# soundcard_v2_1.net
KiCad netlist of a schematic drawn in EAGLE
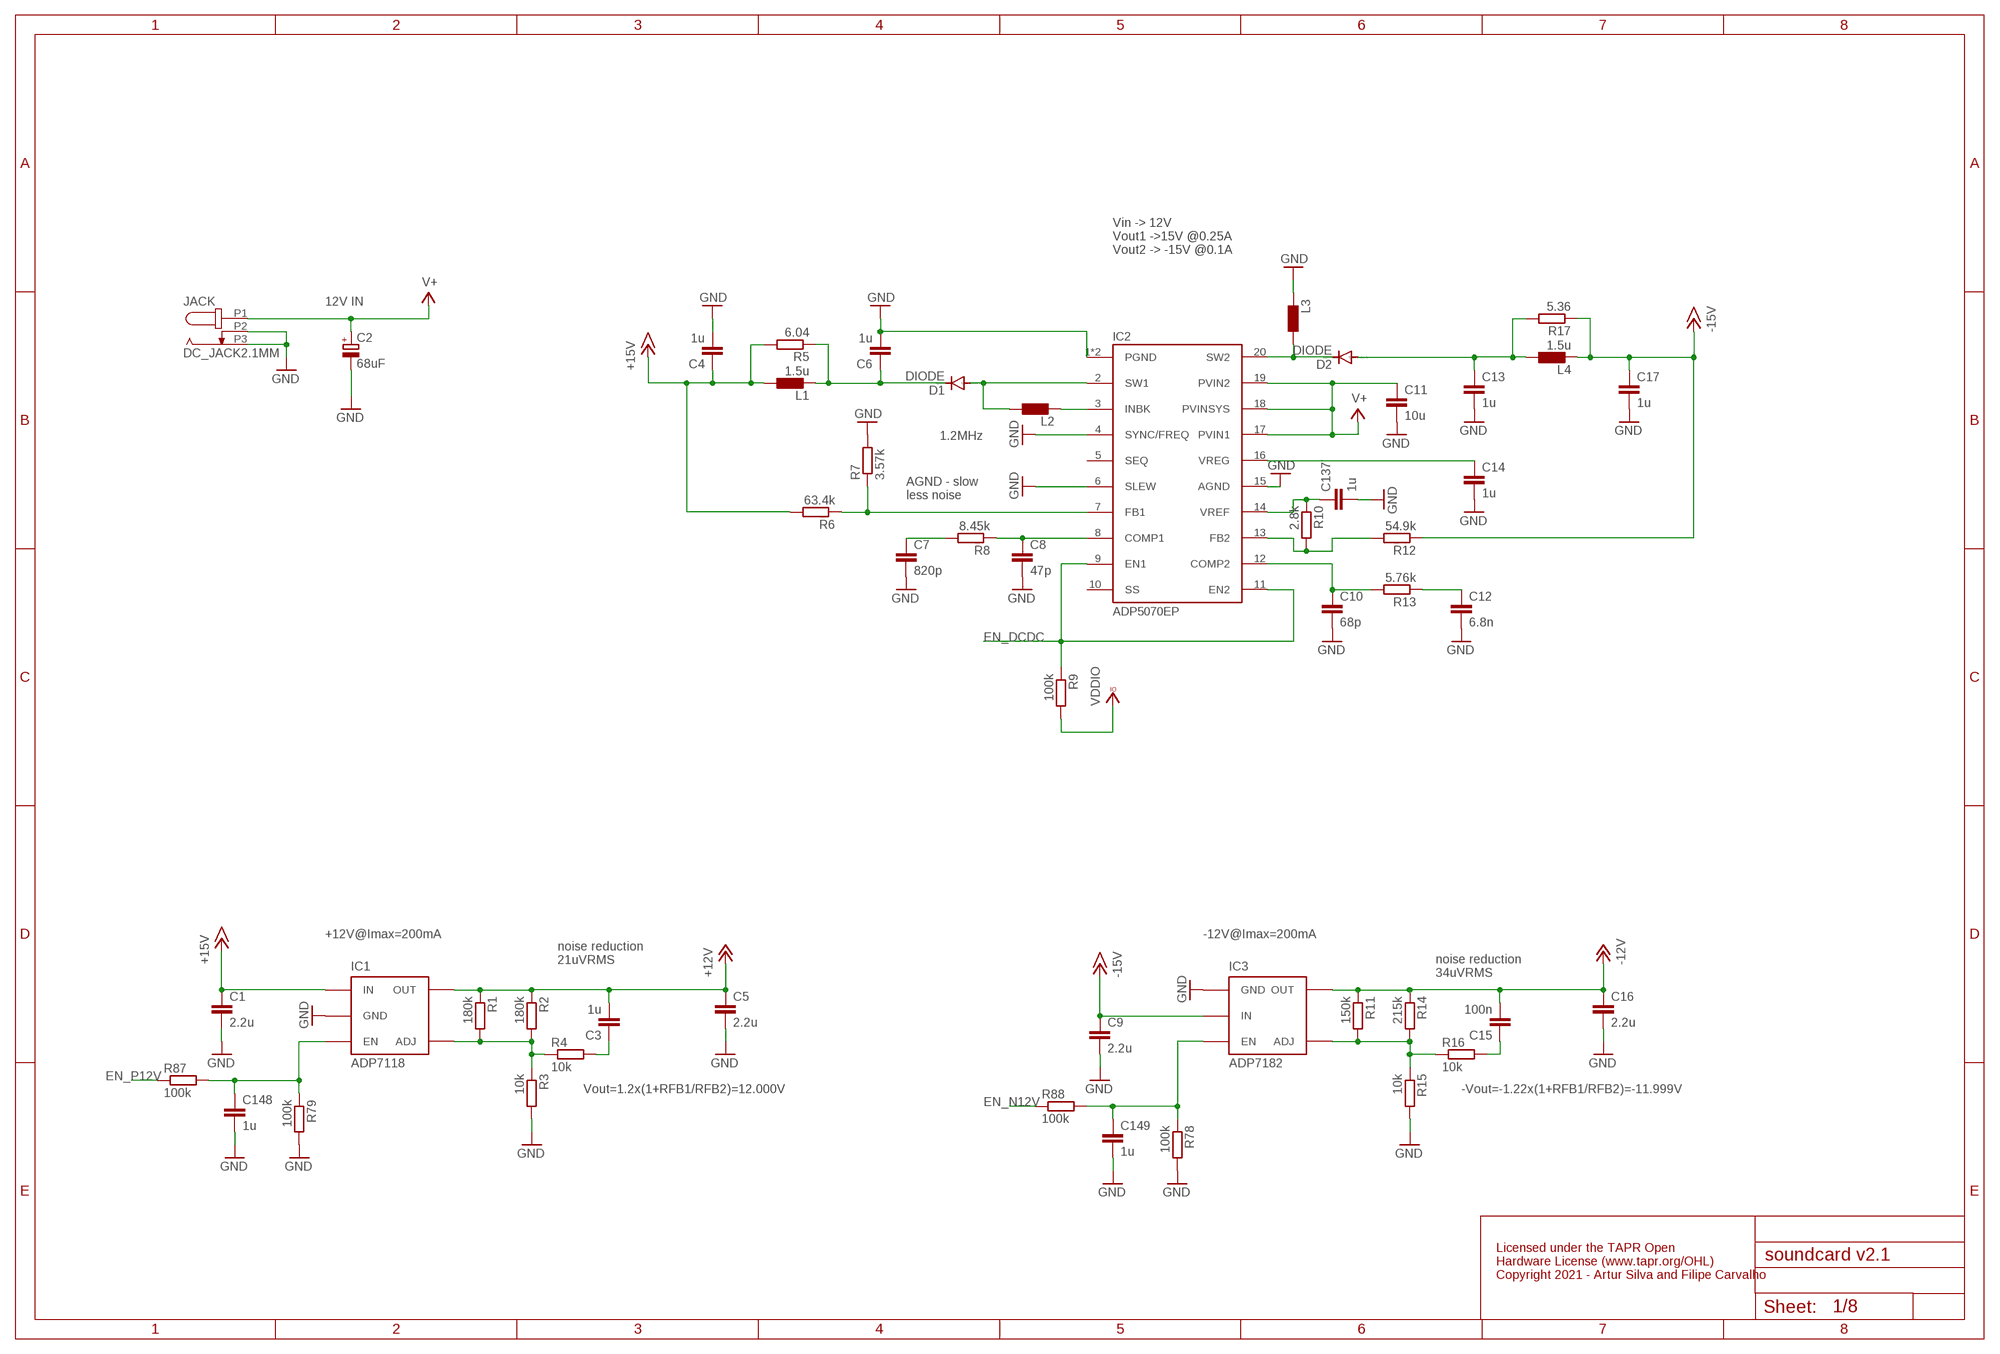
[diagram p0: schematic, sheet 1]
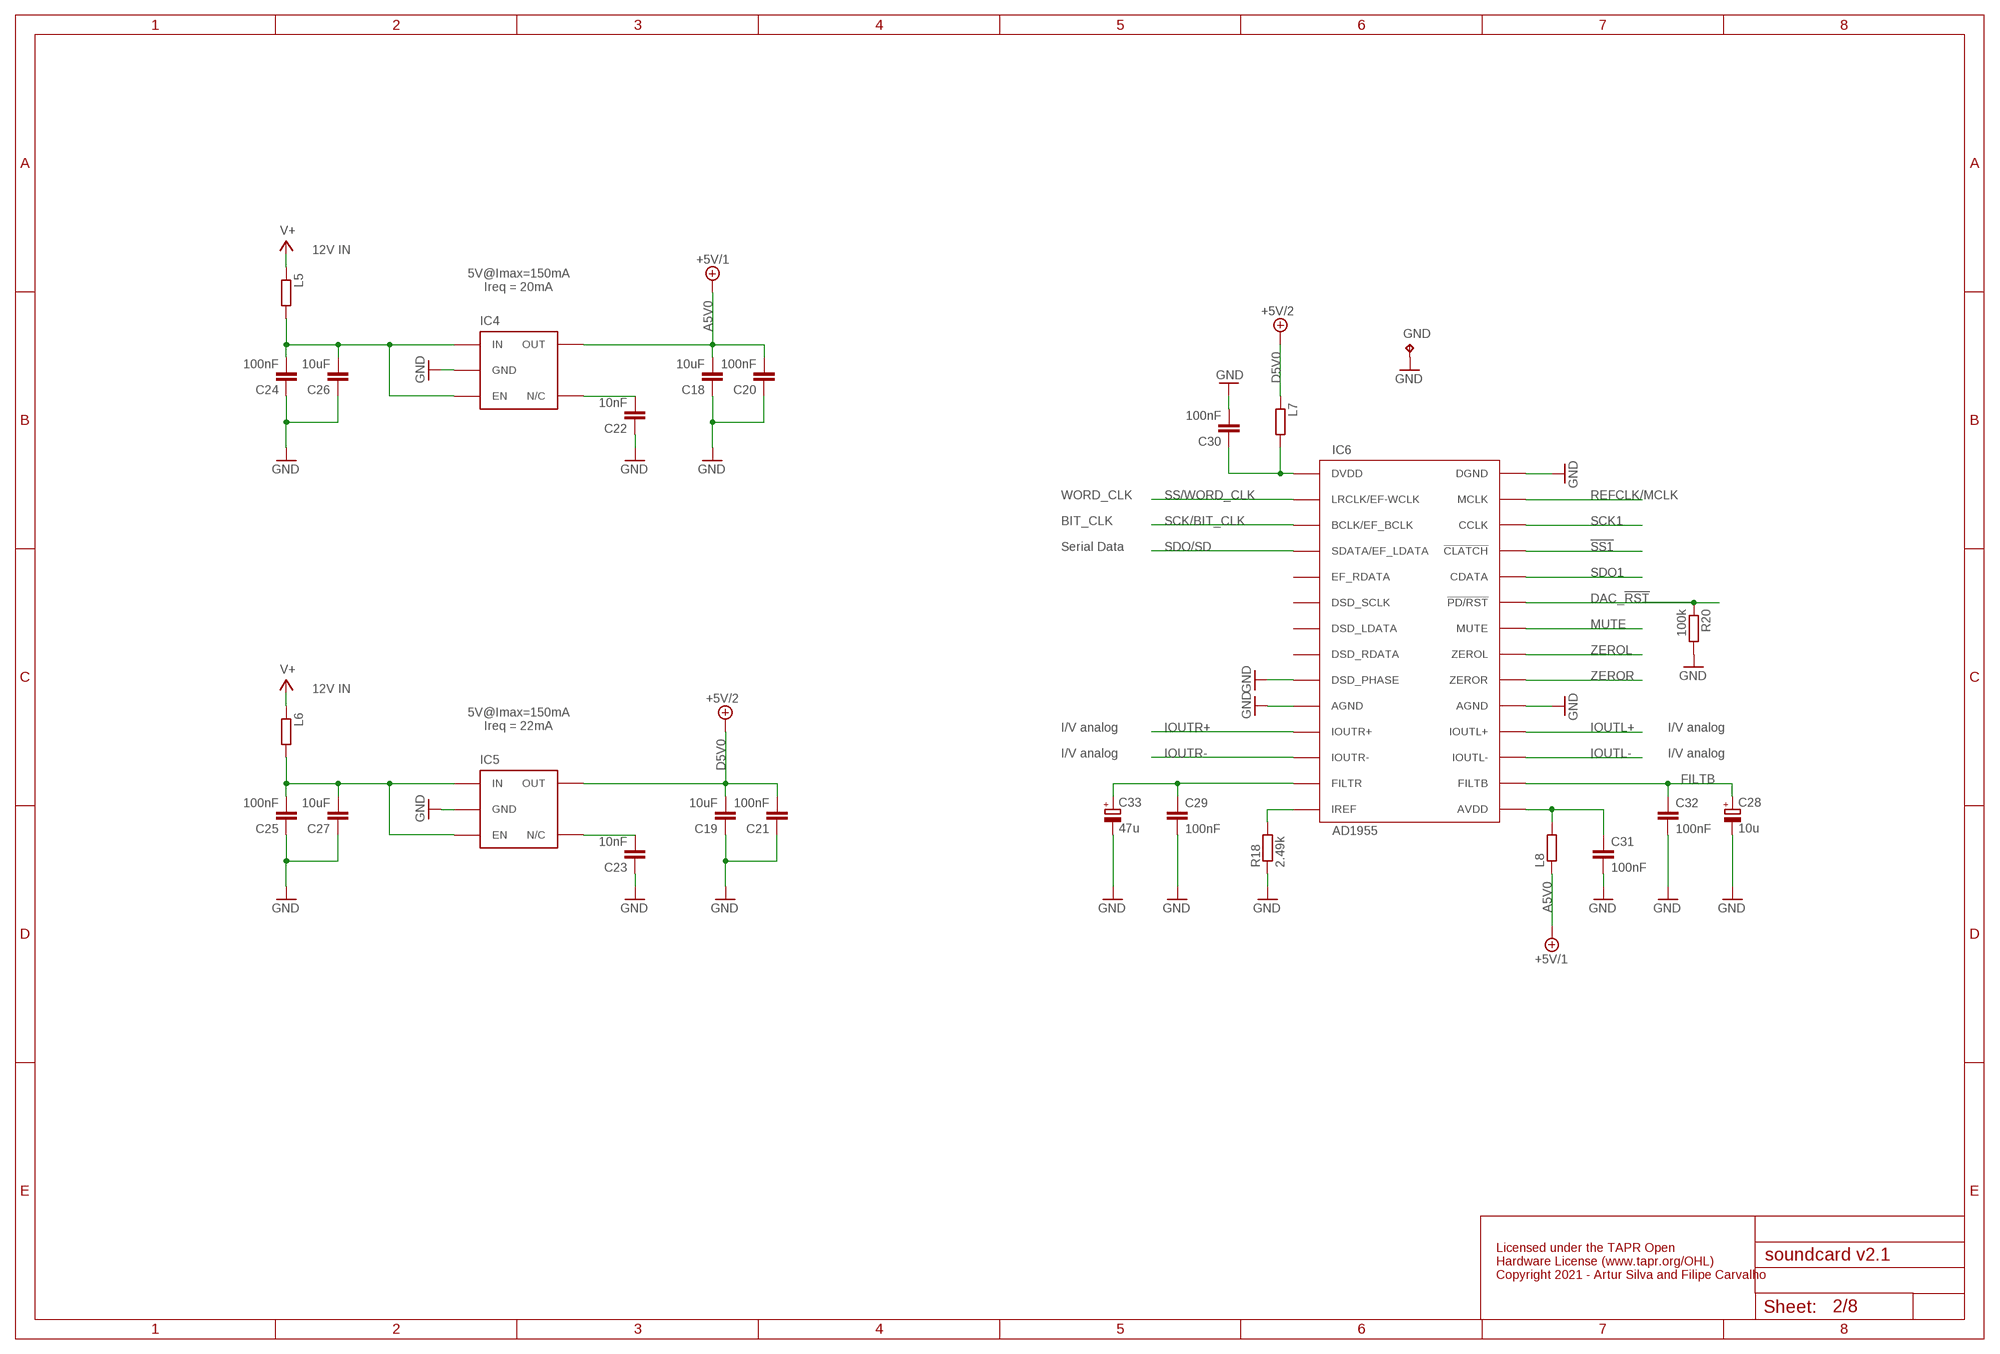
[diagram p1: schematic, sheet 2]
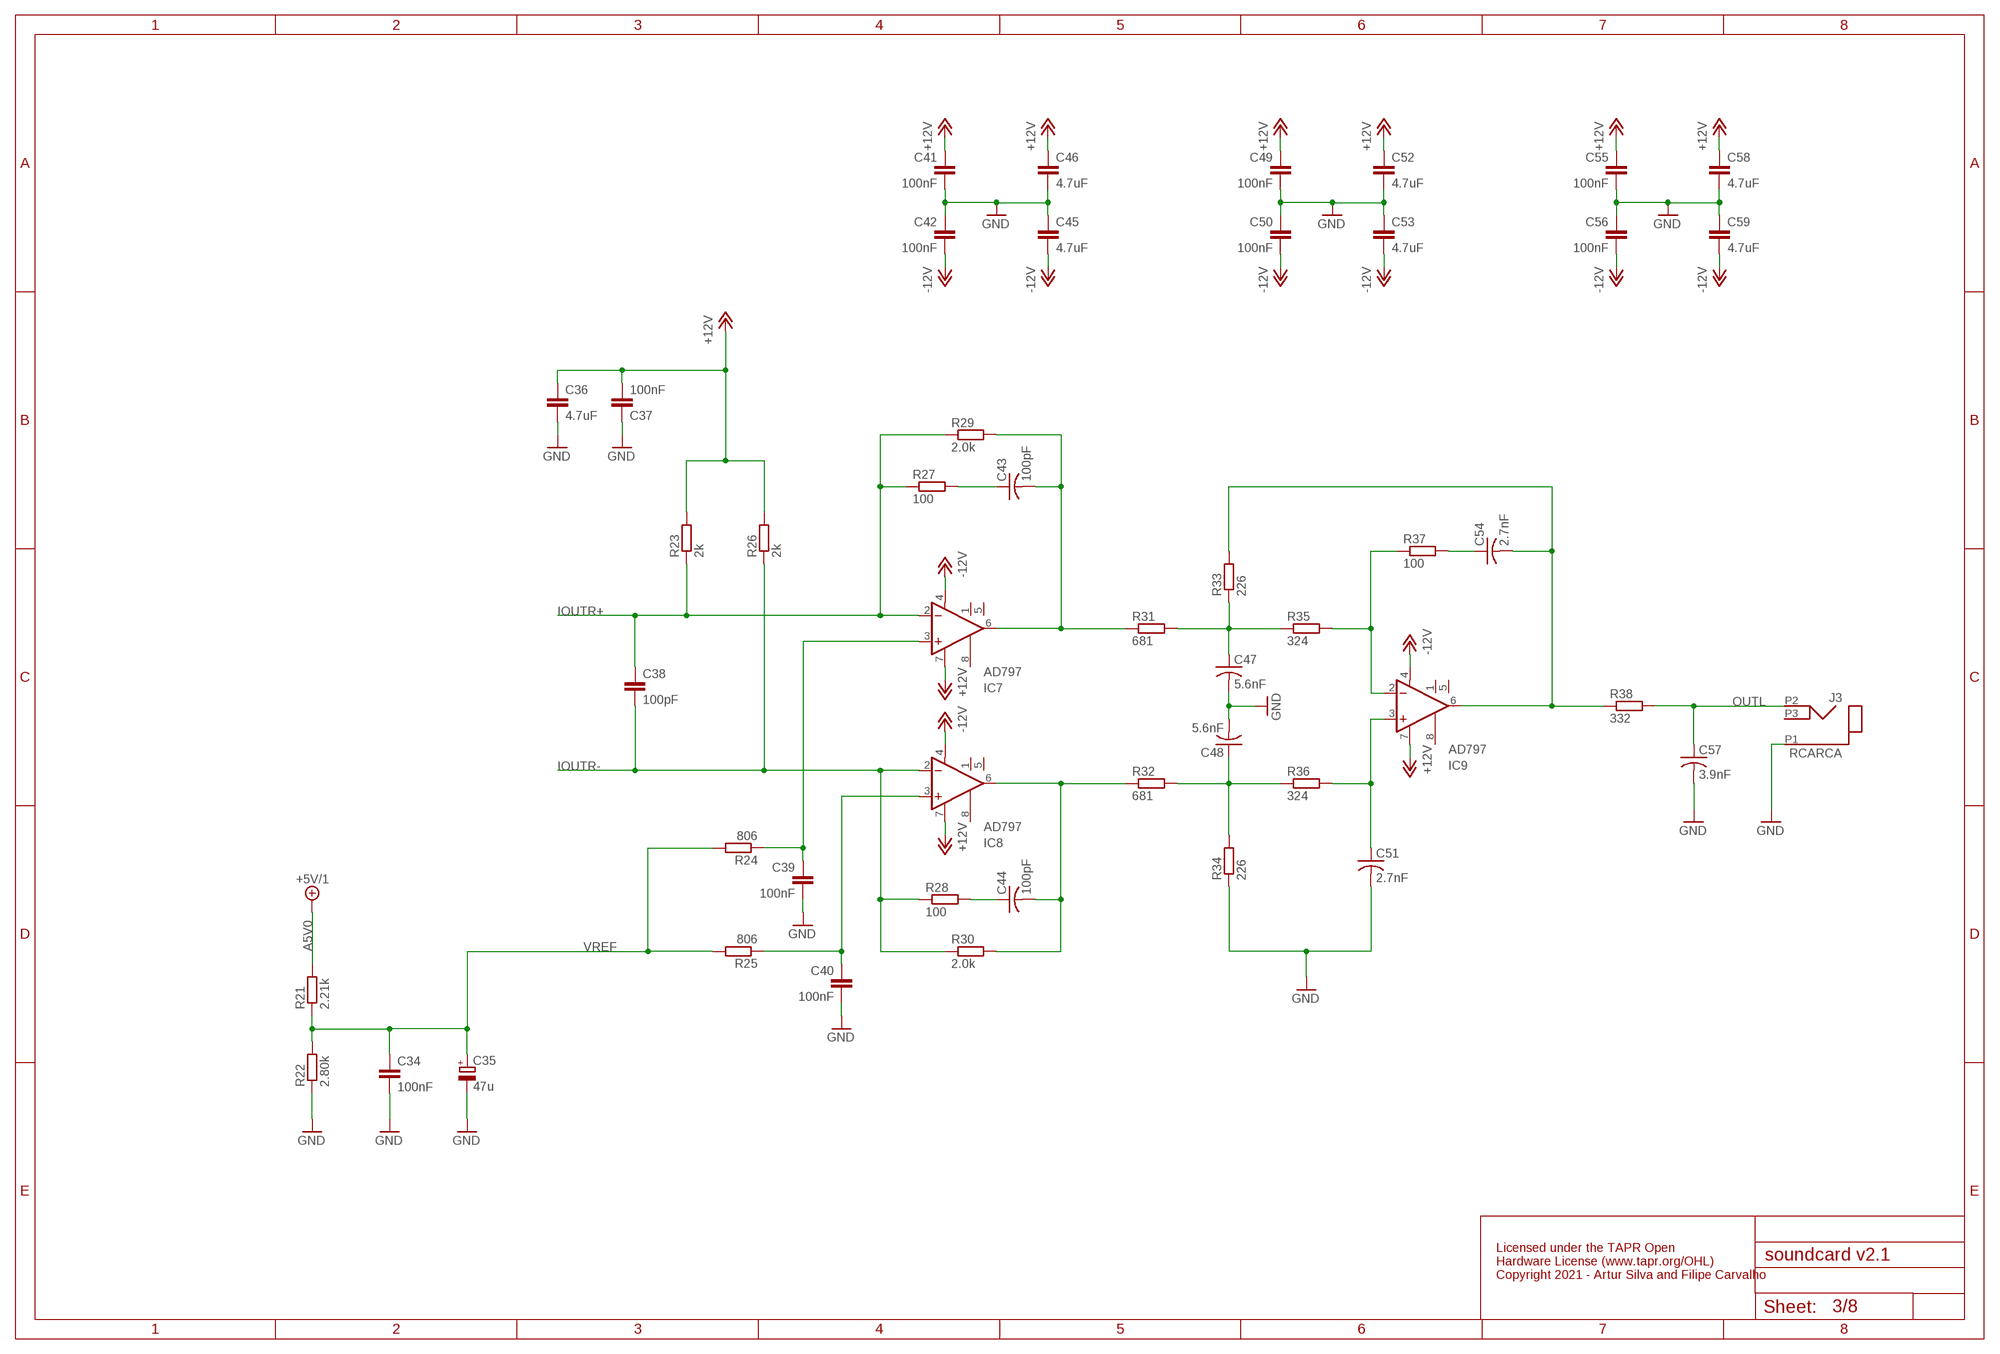
[diagram p2: schematic, sheet 3]
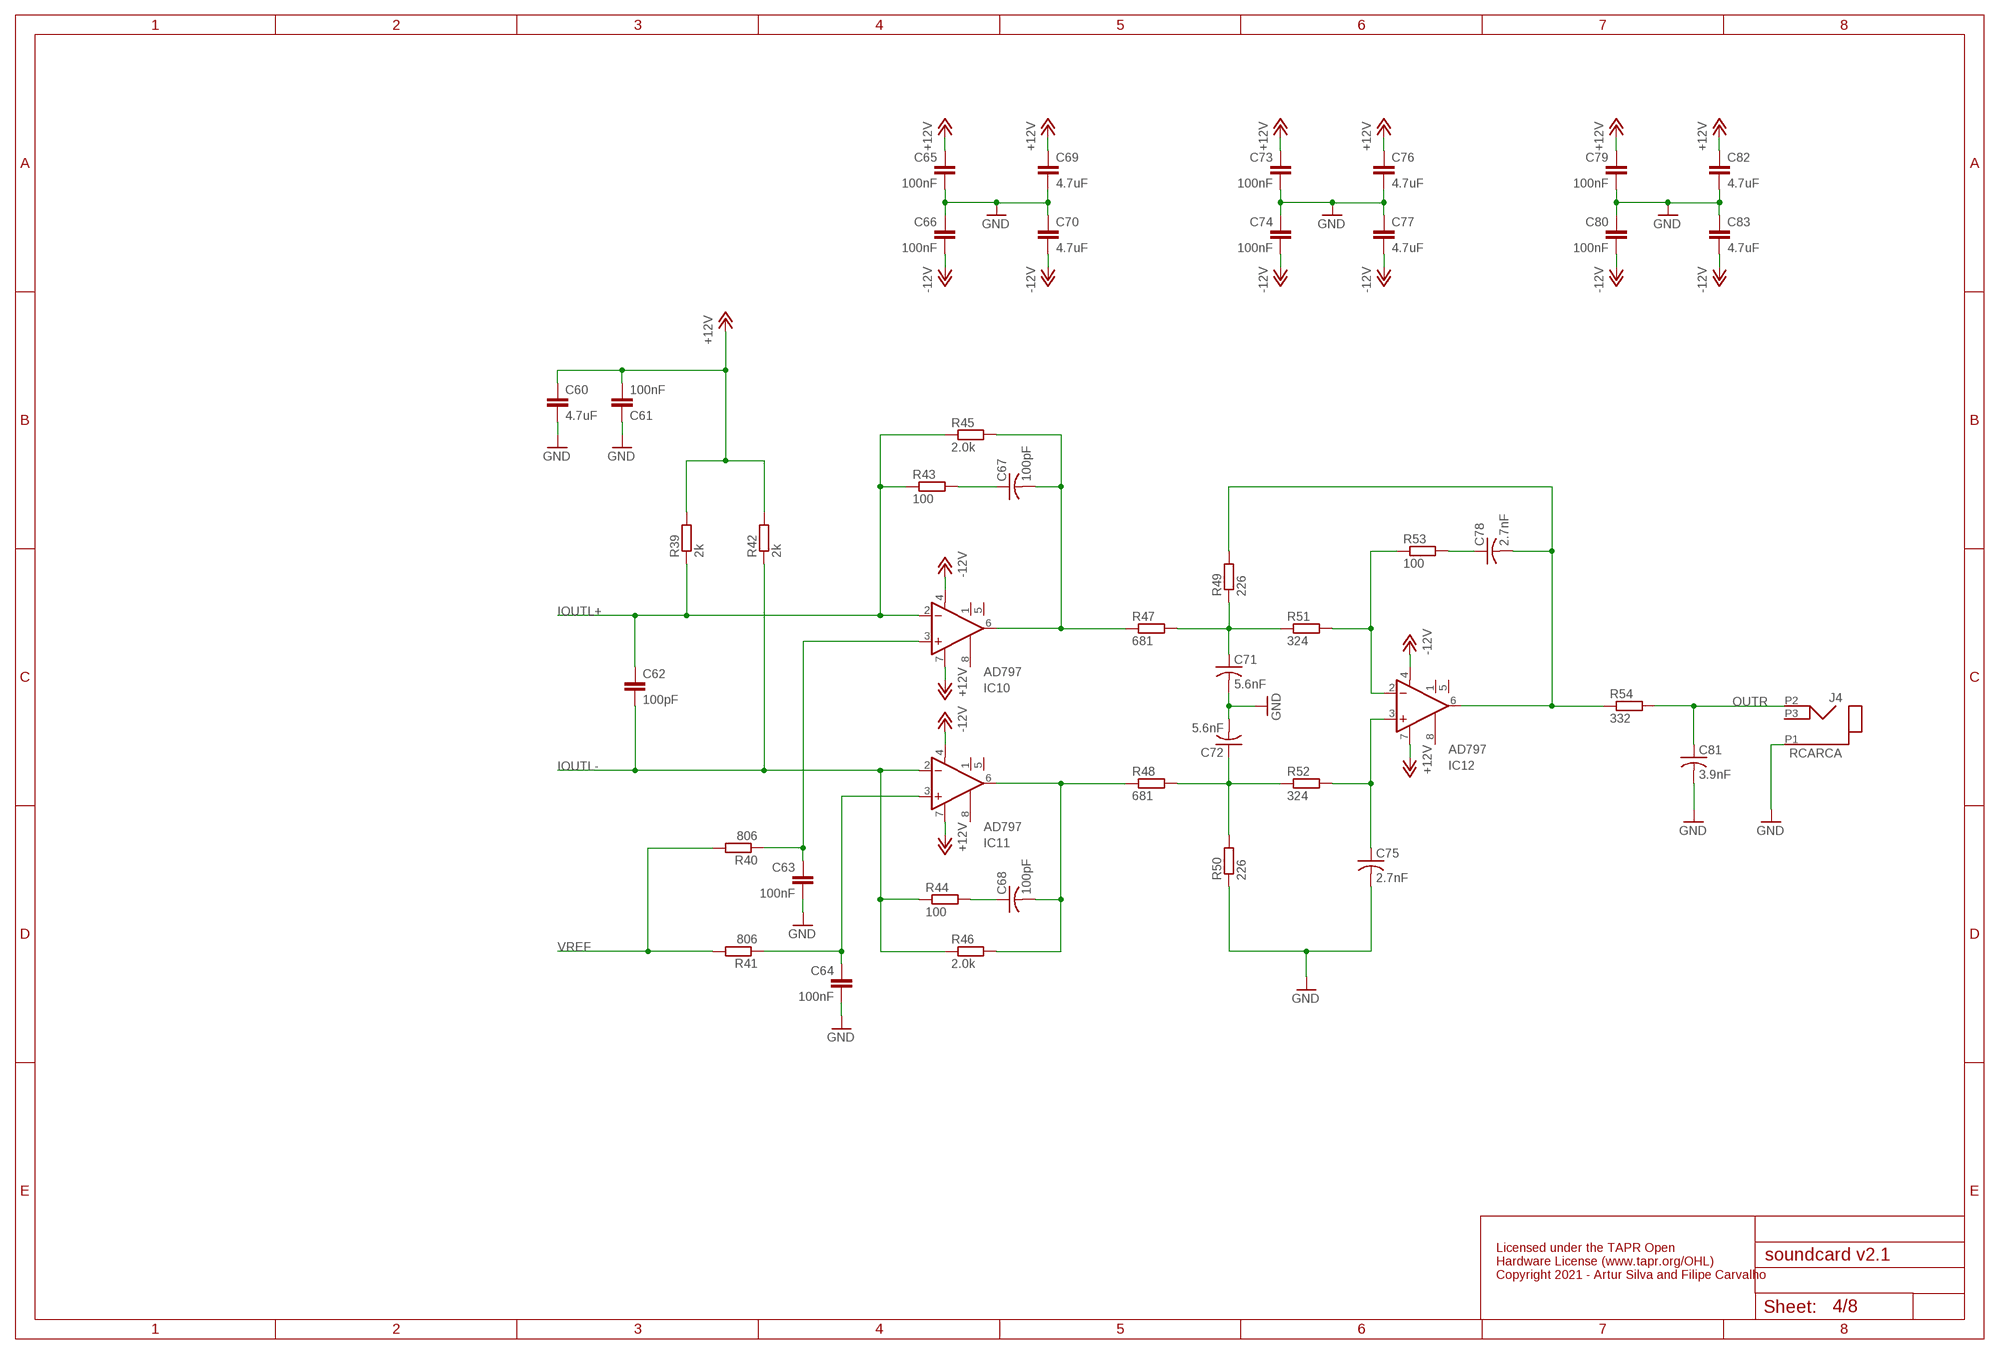
[diagram p3: schematic, sheet 4]
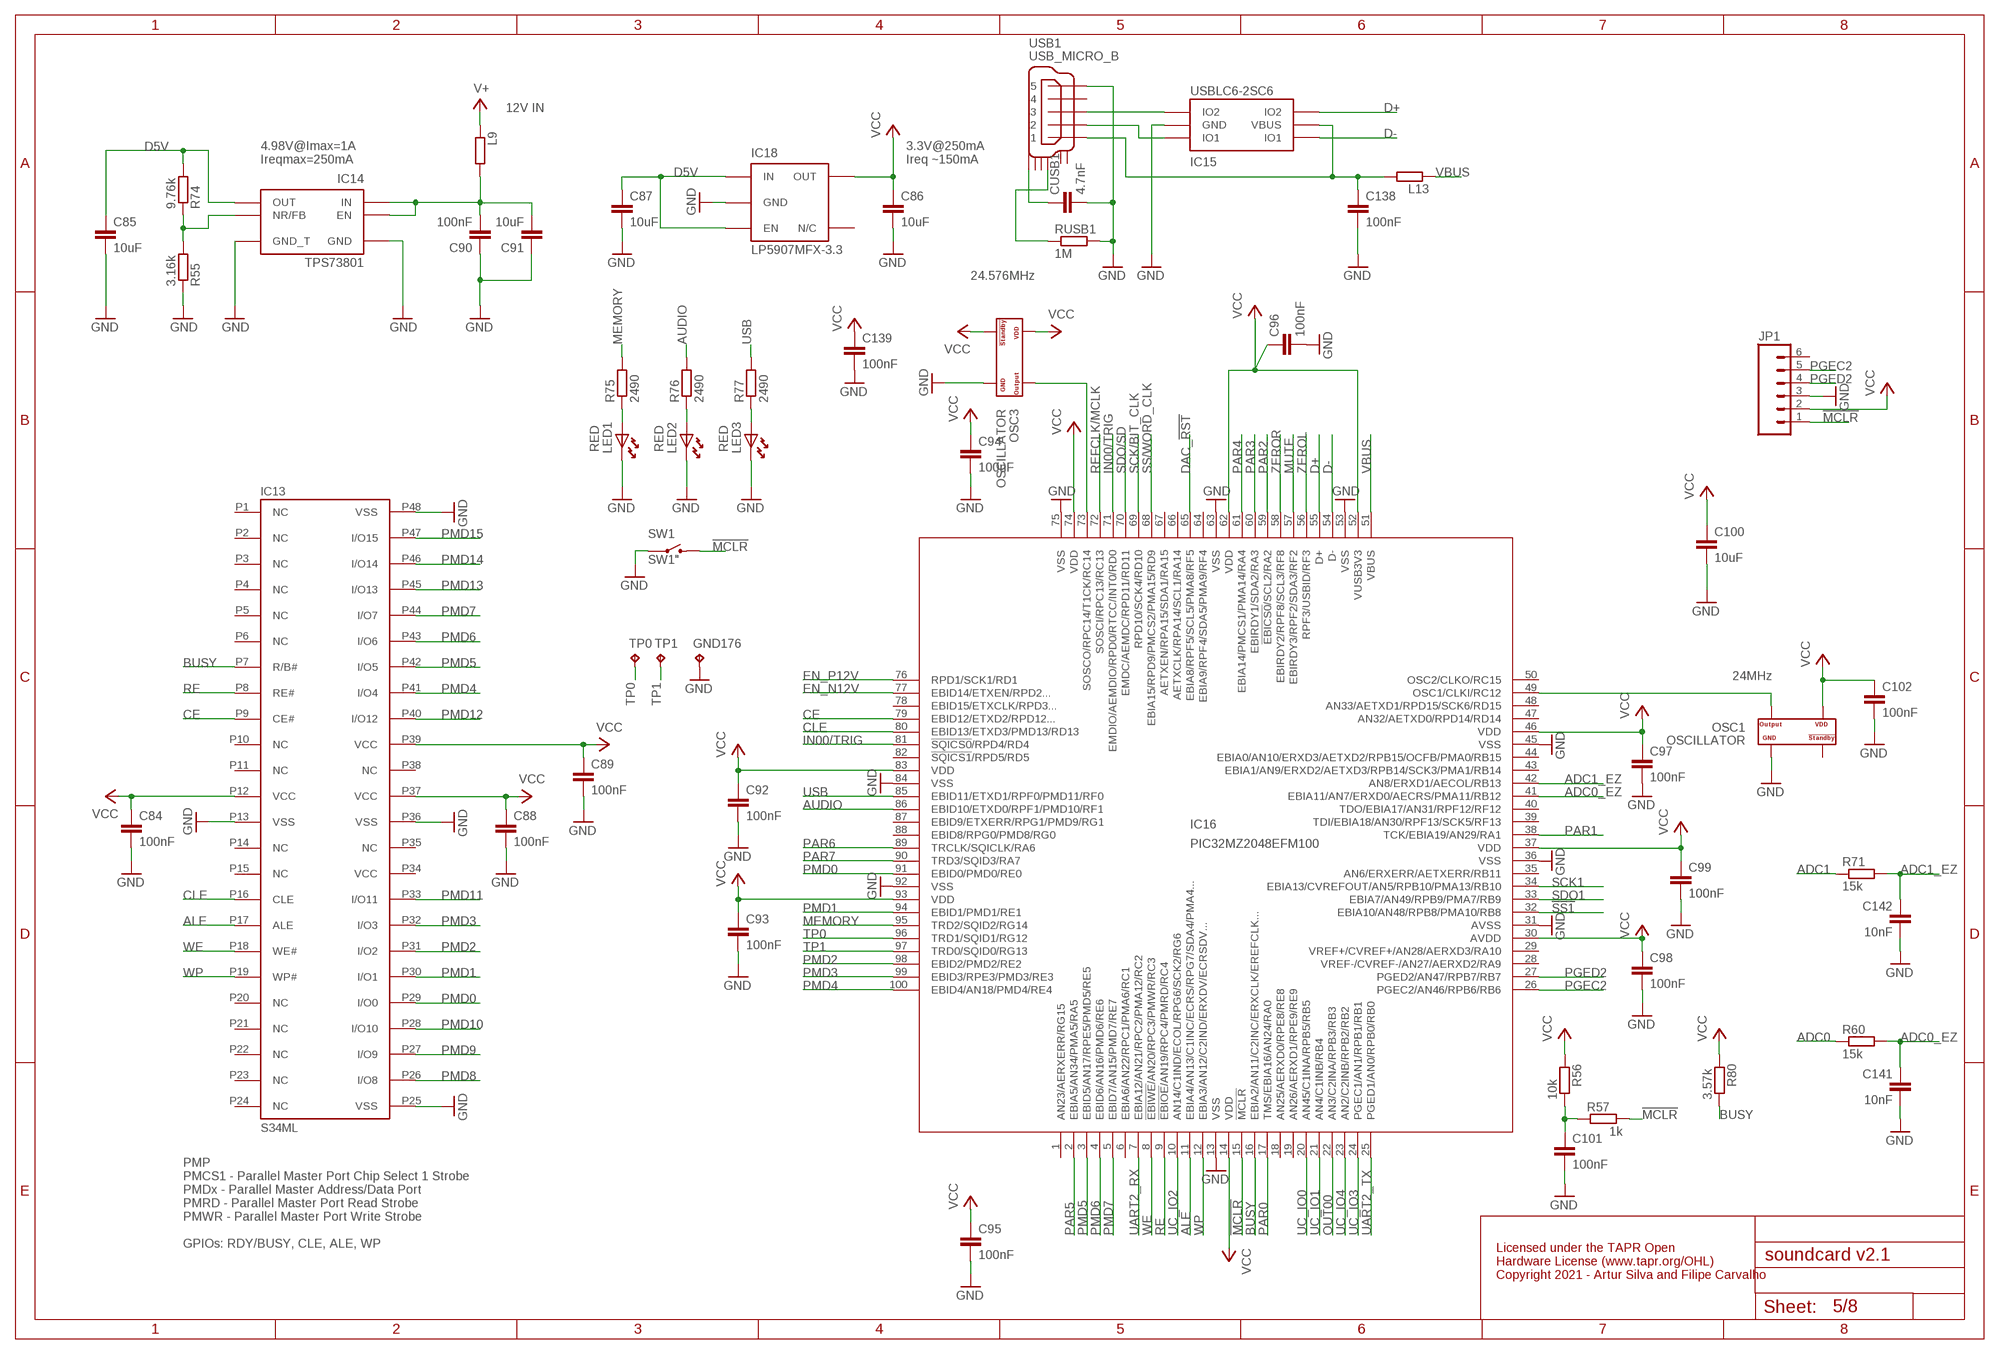
[diagram p4: schematic, sheet 5]
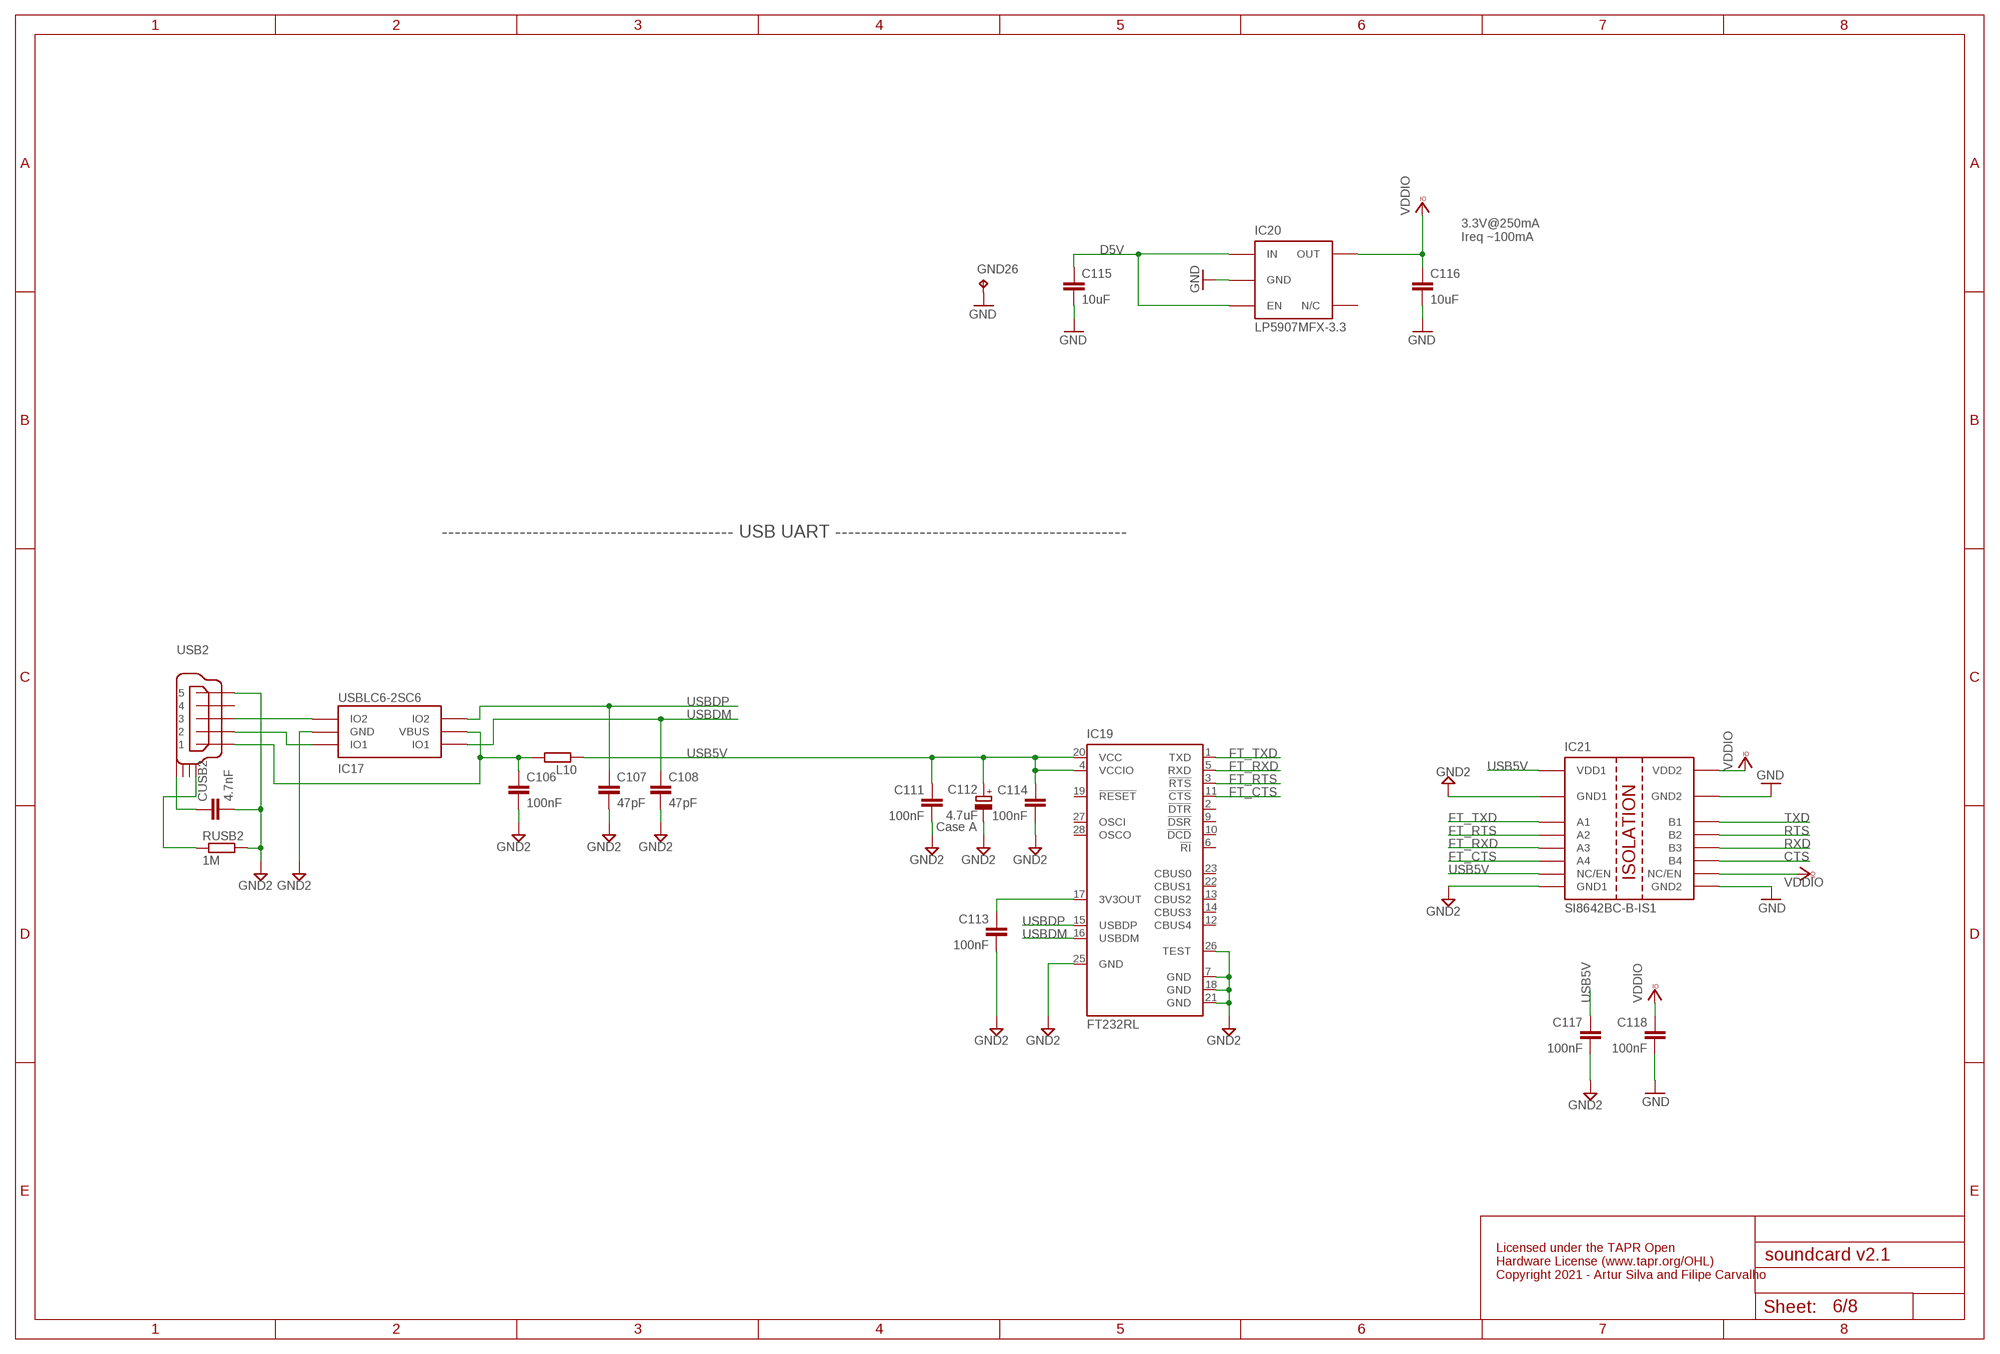
[diagram p5: schematic, sheet 6]
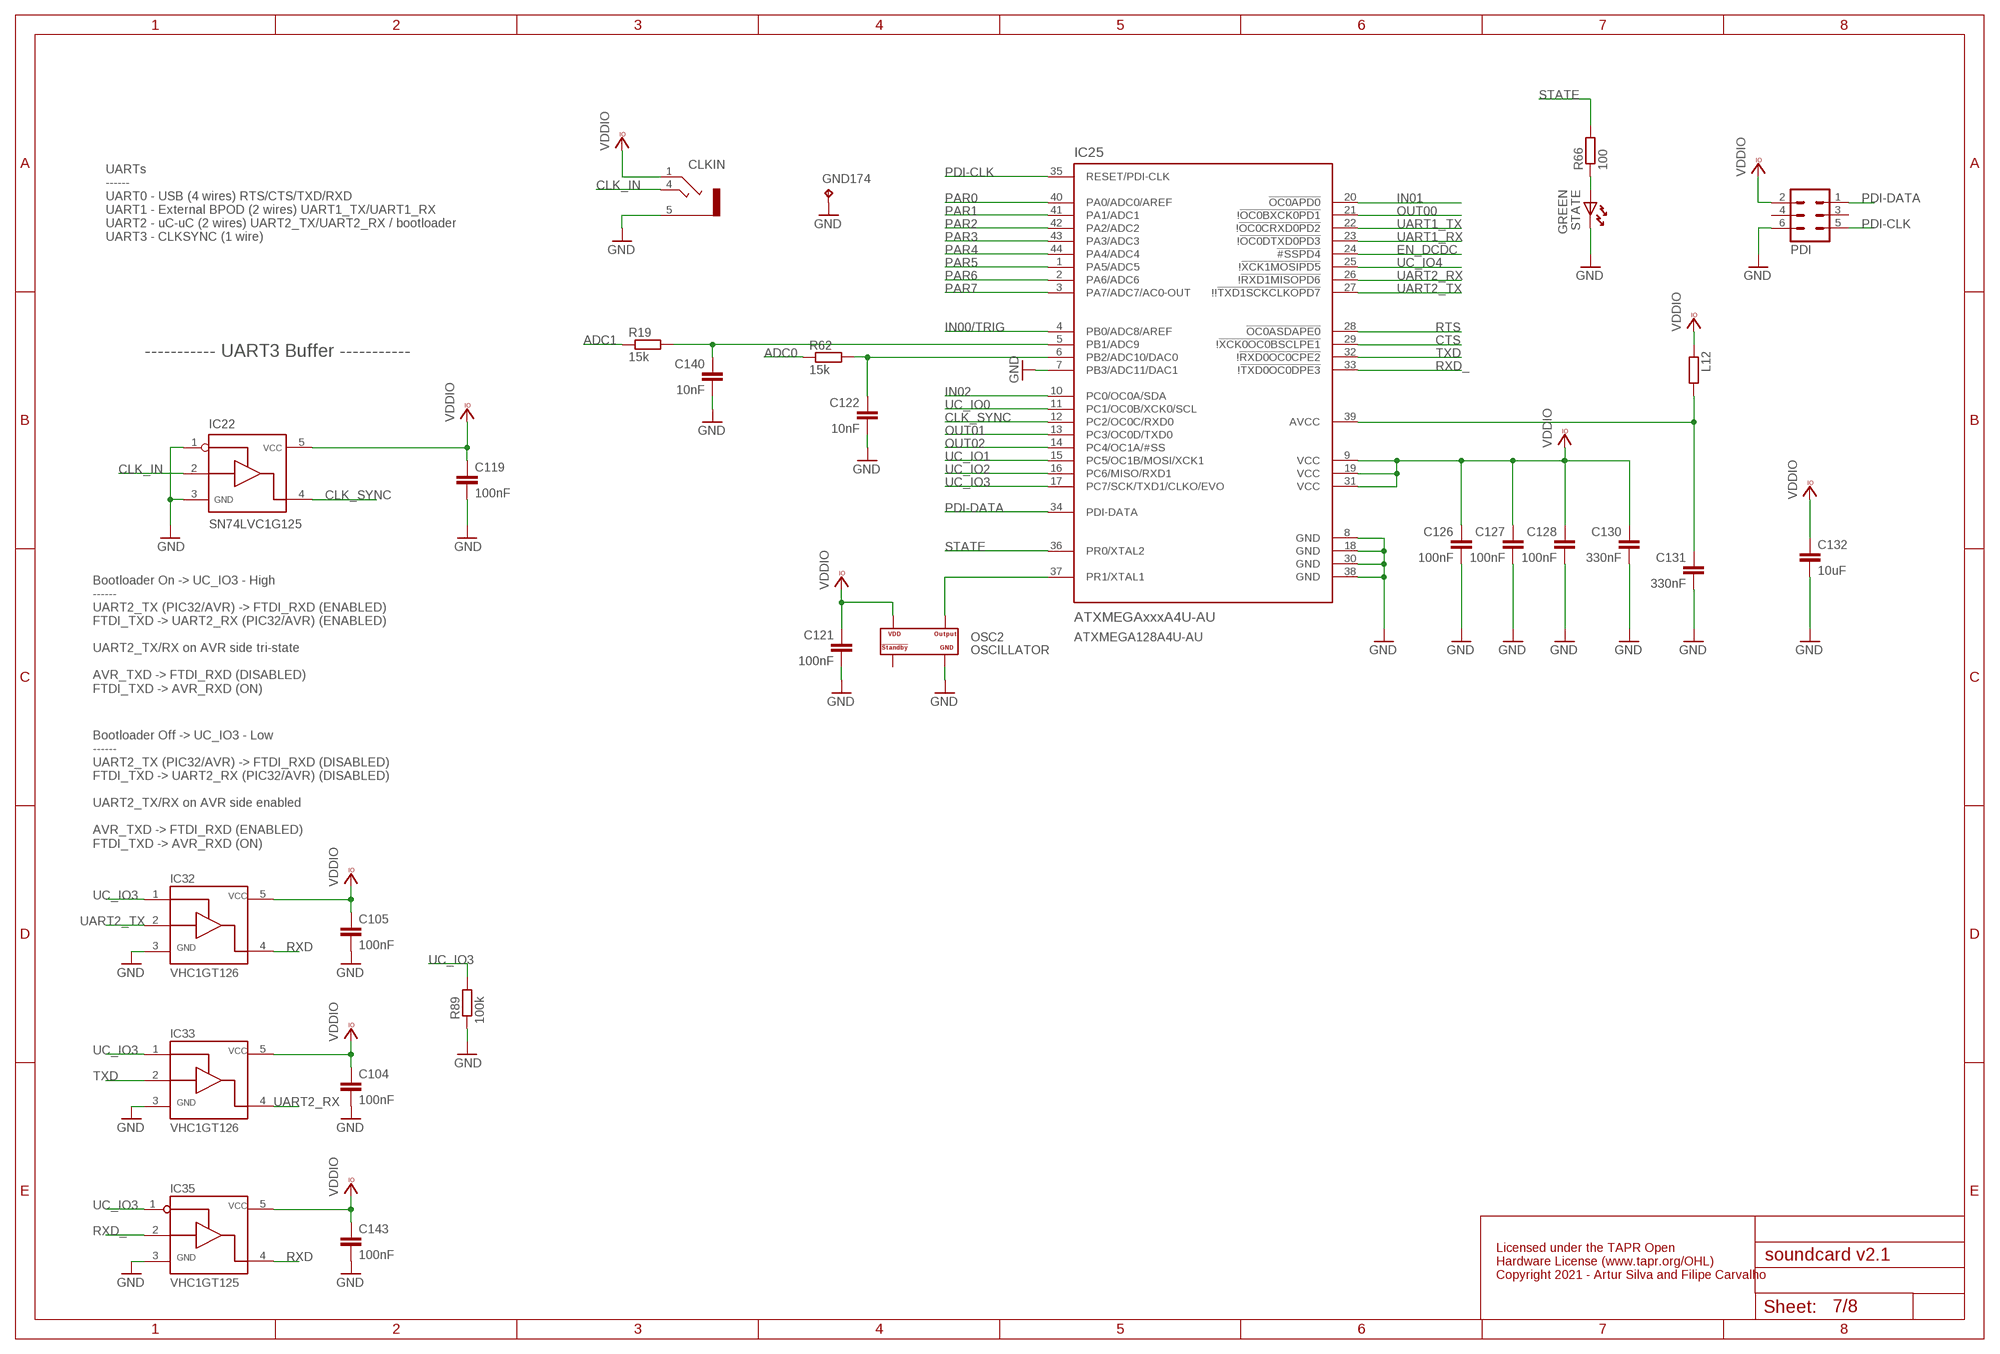
[diagram p6: schematic, sheet 7]
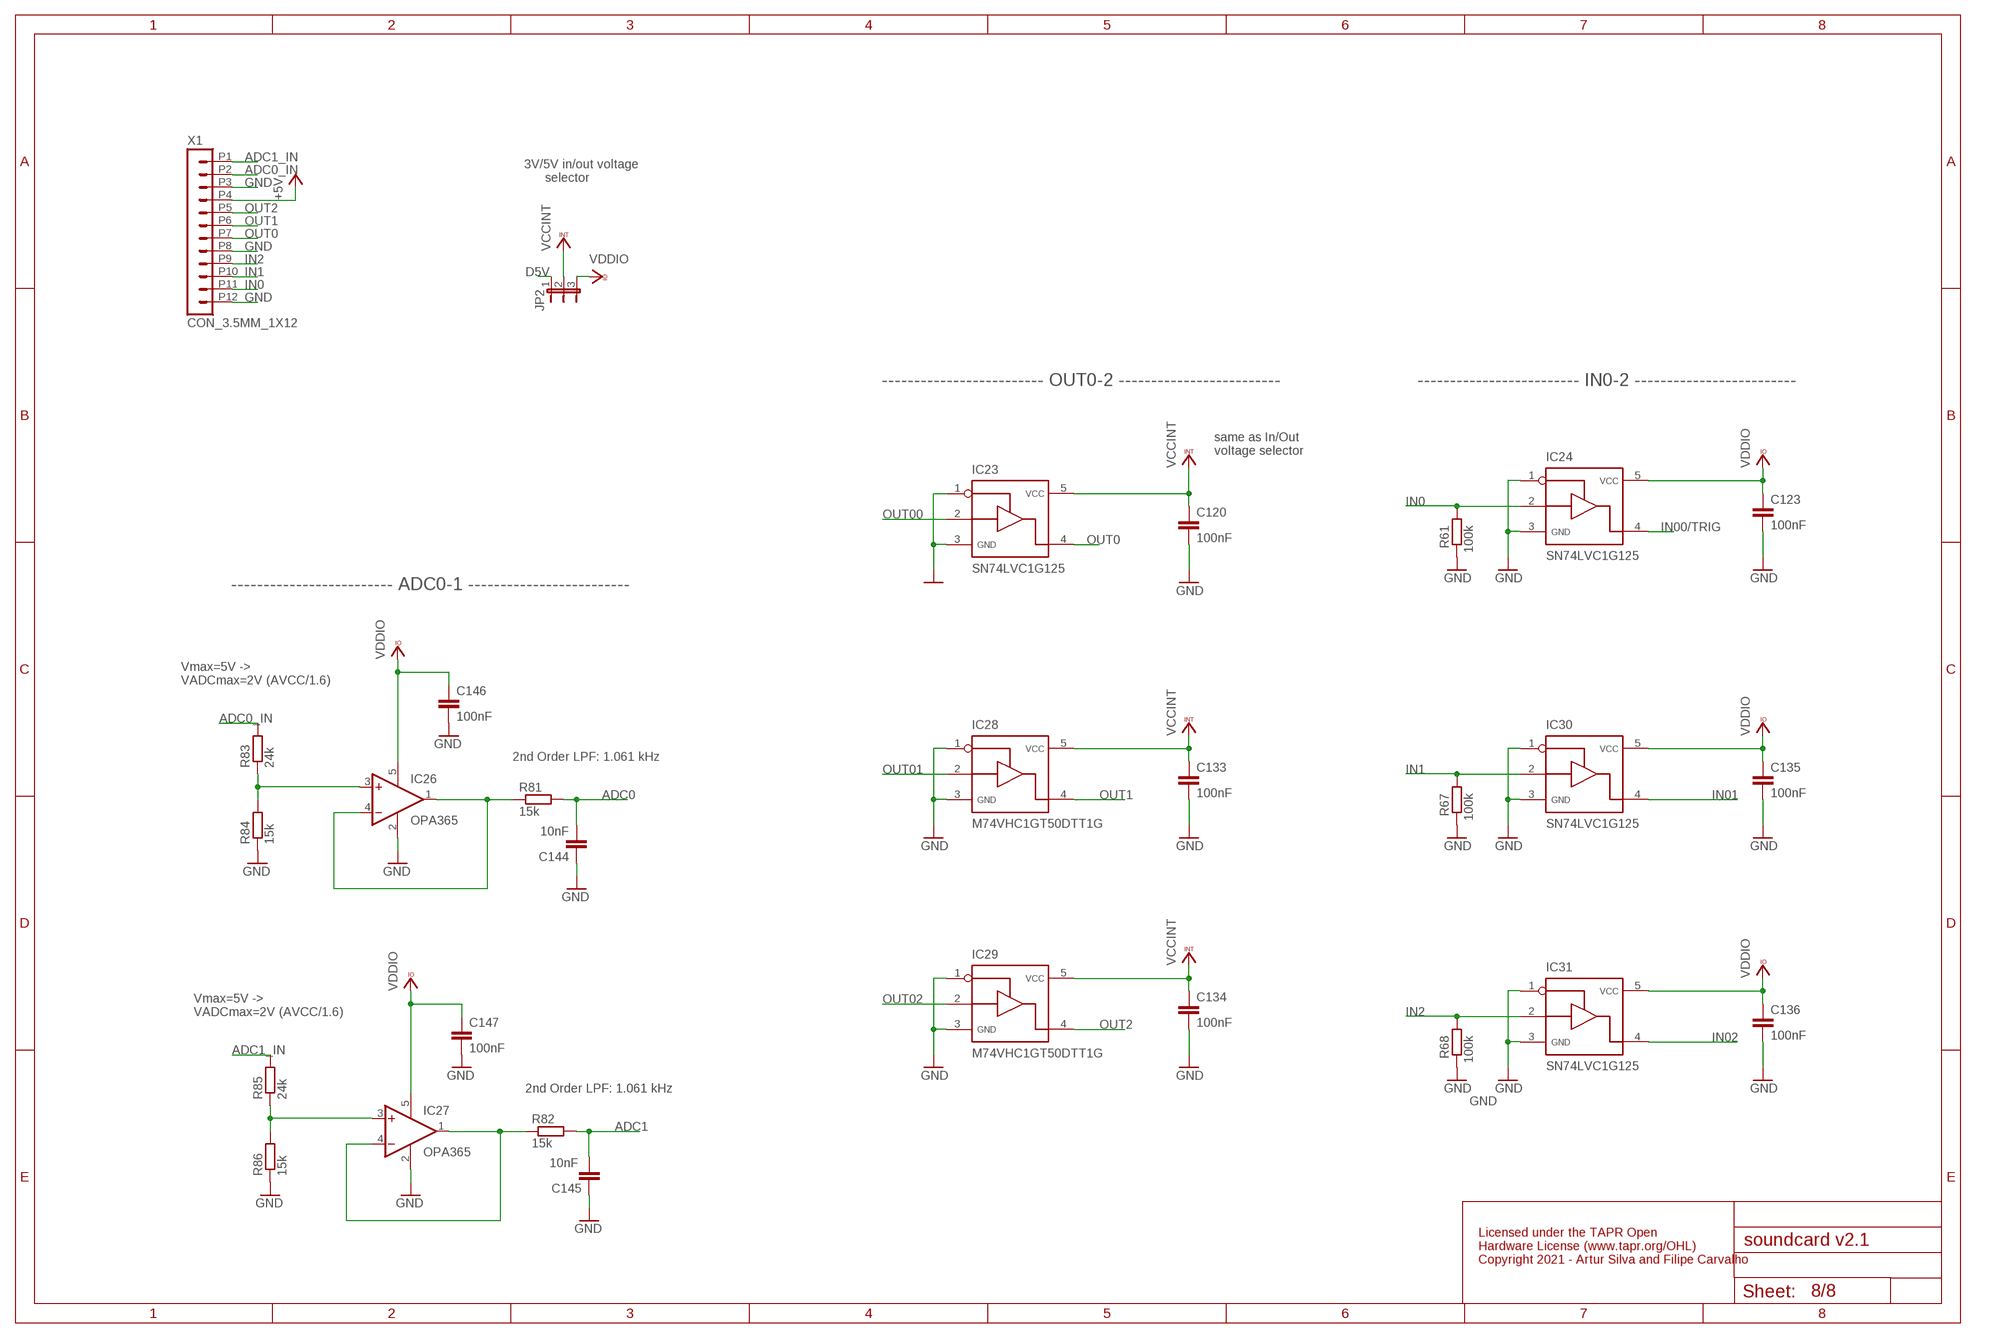
[diagram p7: schematic, sheet 8]

(export (version "E")
  (design (tool "Eeschema 10.0.6"))
  (components
    (comp (ref "C84")
      (value "100nF")
      (footprint "eagle-import:C0402")
      (libsource (lib "eagle-import") (part "rcl_334_C-EUC0402"))
    )
    (comp (ref "C85")
      (value "10uF")
      (footprint "eagle-import:C0603")
      (libsource (lib "eagle-import") (part "rcl_334_C-EUC0603"))
    )
    (comp (ref "C86")
      (value "10uF")
      (footprint "eagle-import:C0603")
      (libsource (lib "eagle-import") (part "rcl_334_C-EUC0603"))
    )
    (comp (ref "C87")
      (value "10uF")
      (footprint "eagle-import:C0603")
      (libsource (lib "eagle-import") (part "rcl_334_C-EUC0603"))
    )
    (comp (ref "C88")
      (value "100nF")
      (footprint "eagle-import:C0402")
      (libsource (lib "eagle-import") (part "rcl_334_C-EUC0402"))
    )
    (comp (ref "C89")
      (value "100nF")
      (footprint "eagle-import:C0402")
      (libsource (lib "eagle-import") (part "rcl_334_C-EUC0402"))
    )
    (comp (ref "C90")
      (value "100nF")
      (footprint "eagle-import:C0402")
      (libsource (lib "eagle-import") (part "rcl_334_C-EUC0402"))
    )
    (comp (ref "C91")
      (value "10uF")
      (footprint "eagle-import:C0603")
      (libsource (lib "eagle-import") (part "rcl_334_C-EUC0603"))
    )
    (comp (ref "C92")
      (value "100nF")
      (footprint "eagle-import:C0402")
      (libsource (lib "eagle-import") (part "rcl_334_C-EUC0402"))
    )
    (comp (ref "C93")
      (value "100nF")
      (footprint "eagle-import:C0402")
      (libsource (lib "eagle-import") (part "rcl_334_C-EUC0402"))
    )
    (comp (ref "C94")
      (value "100nF")
      (footprint "eagle-import:C0402")
      (libsource (lib "eagle-import") (part "rcl_334_C-EUC0402"))
    )
    (comp (ref "C95")
      (value "100nF")
      (footprint "eagle-import:C0402")
      (libsource (lib "eagle-import") (part "rcl_334_C-EUC0402"))
    )
    (comp (ref "C96")
      (value "100nF")
      (footprint "eagle-import:C0402")
      (libsource (lib "eagle-import") (part "rcl_334_C-EUC0402"))
    )
    (comp (ref "C97")
      (value "100nF")
      (footprint "eagle-import:C0402")
      (libsource (lib "eagle-import") (part "rcl_334_C-EUC0402"))
    )
    (comp (ref "C98")
      (value "100nF")
      (footprint "eagle-import:C0402")
      (libsource (lib "eagle-import") (part "rcl_334_C-EUC0402"))
    )
    (comp (ref "C99")
      (value "100nF")
      (footprint "eagle-import:C0402")
      (libsource (lib "eagle-import") (part "rcl_334_C-EUC0402"))
    )
    (comp (ref "C100")
      (value "10uF")
      (footprint "eagle-import:C0603")
      (libsource (lib "eagle-import") (part "rcl_334_C-EUC0603"))
    )
    (comp (ref "C101")
      (value "100nF")
      (footprint "eagle-import:C0402")
      (libsource (lib "eagle-import") (part "rcl_334_C-EUC0402"))
    )
    (comp (ref "C102")
      (value "100nF")
      (footprint "eagle-import:C0402")
      (libsource (lib "eagle-import") (part "rcl_334_C-EUC0402"))
    )
    (comp (ref "C138")
      (value "100nF")
      (footprint "eagle-import:C0402")
      (libsource (lib "eagle-import") (part "rcl_334_C-EUC0402"))
    )
    (comp (ref "C139")
      (value "100nF")
      (footprint "eagle-import:C0402")
      (libsource (lib "eagle-import") (part "rcl_334_C-EUC0402"))
    )
    (comp (ref "C141")
      (value "10nF")
      (footprint "eagle-import:C0402")
      (libsource (lib "eagle-import") (part "C-EUC0402"))
    )
    (comp (ref "C142")
      (value "10nF")
      (footprint "eagle-import:C0402")
      (libsource (lib "eagle-import") (part "C-EUC0402"))
    )
    (comp (ref "CUSB1")
      (value "4.7nF")
      (footprint "eagle-import:C0402")
      (libsource (lib "eagle-import") (part "rcl_334_C-EUC0402"))
    )
    (comp (ref "GND176")
      (value "TP")
      (footprint "eagle-import:TP_1")
      (libsource (lib "eagle-import") (part "TP"))
    )
    (comp (ref "IC13")
      (value "S34ML")
      (footprint "eagle-import:TSOP-48")
      (libsource (lib "eagle-import") (part "S34ML"))
    )
    (comp (ref "IC14")
      (value "TPS73801")
      (footprint "eagle-import:SOT223-6")
      (libsource (lib "eagle-import") (part "TPS73801"))
    )
    (comp (ref "IC15")
      (value "USBLC6-2SC6")
      (footprint "eagle-import:SOT23-6L")
      (libsource (lib "eagle-import") (part "USBLC6-2"))
    )
    (comp (ref "IC16")
      (value "PIC32MZ2048EFM100")
      (footprint "eagle-import:TQFP-100")
      (libsource (lib "eagle-import") (part "PIC32MZ2048EFM100"))
    )
    (comp (ref "IC18")
      (value "LP5907MFX-3.3")
      (footprint "eagle-import:TSOT23-5")
      (libsource (lib "eagle-import") (part "TLV700XX"))
    )
    (comp (ref "JP1")
      (value "M06NO_SILK")
      (footprint "eagle-import:1X06_NO_SILK")
      (libsource (lib "eagle-import") (part "M06NO_SILK"))
    )
    (comp (ref "L9")
      (value "600@100M")
      (footprint "eagle-import:R0805")
      (libsource (lib "eagle-import") (part "rcl_334_R-EU_R0805"))
    )
    (comp (ref "L13")
      (value "???")
      (footprint "eagle-import:R0805")
      (libsource (lib "eagle-import") (part "rcl_334_R-EU_R0805"))
    )
    (comp (ref "LED1")
      (value "RED")
      (footprint "eagle-import:LED_HAND")
      (libsource (lib "eagle-import") (part "LEDHAND"))
    )
    (comp (ref "LED2")
      (value "RED")
      (footprint "eagle-import:LED_HAND")
      (libsource (lib "eagle-import") (part "LEDHAND"))
    )
    (comp (ref "LED3")
      (value "RED")
      (footprint "eagle-import:LED_HAND")
      (libsource (lib "eagle-import") (part "LEDHAND"))
    )
    (comp (ref "OSC1")
      (value "OSCILLATOR")
      (footprint "eagle-import:OSCILLATOR_3.2X2.5")
      (libsource (lib "eagle-import") (part "OSCILLATOR"))
    )
    (comp (ref "OSC3")
      (value "OSCILLATOR")
      (footprint "eagle-import:OSCILLATOR_3.2X2.5")
      (libsource (lib "eagle-import") (part "OSCILLATOR"))
    )
    (comp (ref "R55")
      (value "3.16k")
      (footprint "eagle-import:R0402")
      (libsource (lib "eagle-import") (part "rcl_334_R-EU_R0402"))
    )
    (comp (ref "R56")
      (value "10k")
      (footprint "eagle-import:R0402")
      (libsource (lib "eagle-import") (part "rcl_334_R-EU_R0402"))
    )
    (comp (ref "R57")
      (value "1k")
      (footprint "eagle-import:R0402")
      (libsource (lib "eagle-import") (part "rcl_334_R-EU_R0402"))
    )
    (comp (ref "R60")
      (value "15k")
      (footprint "eagle-import:R0402")
      (libsource (lib "eagle-import") (part "R-EU_R0402"))
    )
    (comp (ref "R71")
      (value "15k")
      (footprint "eagle-import:R0402")
      (libsource (lib "eagle-import") (part "R-EU_R0402"))
    )
    (comp (ref "R74")
      (value "9.76k")
      (footprint "eagle-import:R0402")
      (libsource (lib "eagle-import") (part "rcl_334_R-EU_R0402"))
    )
    (comp (ref "R75")
      (value "2490")
      (footprint "eagle-import:R0402")
      (libsource (lib "eagle-import") (part "rcl_334_R-EU_R0402"))
    )
    (comp (ref "R76")
      (value "2490")
      (footprint "eagle-import:R0402")
      (libsource (lib "eagle-import") (part "rcl_334_R-EU_R0402"))
    )
    (comp (ref "R77")
      (value "2490")
      (footprint "eagle-import:R0402")
      (libsource (lib "eagle-import") (part "rcl_334_R-EU_R0402"))
    )
    (comp (ref "R80")
      (value "3.57k")
      (footprint "eagle-import:R0402")
      (libsource (lib "eagle-import") (part "rcl_334_R-EU_R0402"))
    )
    (comp (ref "RUSB1")
      (value "1M")
      (footprint "eagle-import:R0402")
      (libsource (lib "eagle-import") (part "rcl_334_R-EU_R0402"))
    )
    (comp (ref "SW1")
      (value "SW1\"")
      (footprint "eagle-import:SWITCH_KSS")
      (libsource (lib "eagle-import") (part "SW1{dblquote}"))
    )
    (comp (ref "TP0")
      (value "TP")
      (footprint "eagle-import:TP_1")
      (libsource (lib "eagle-import") (part "TP"))
    )
    (comp (ref "TP1")
      (value "TP")
      (footprint "eagle-import:TP_1")
      (libsource (lib "eagle-import") (part "TP"))
    )
    (comp (ref "USB1")
      (value "USB_MICRO_B")
      (footprint "eagle-import:ZX62D-B-5P8")
      (libsource (lib "eagle-import") (part "USB_MICRO_B"))
    )
    (comp (ref "C1")
      (value "2.2u")
      (footprint "eagle-import:C0603")
      (libsource (lib "eagle-import") (part "rcl_334_C-EUC0603"))
    )
    (comp (ref "C2")
      (value "68uF")
      (footprint "eagle-import:E2-5")
      (libsource (lib "eagle-import") (part "rcl_334_CPOL-EUE2-5"))
    )
    (comp (ref "C3")
      (value "1u")
      (footprint "eagle-import:C0402")
      (libsource (lib "eagle-import") (part "rcl_334_C-EUC0402"))
    )
    (comp (ref "C4")
      (value "1u")
      (footprint "eagle-import:C0603")
      (libsource (lib "eagle-import") (part "rcl_334_C-EUC0603"))
    )
    (comp (ref "C5")
      (value "2.2u")
      (footprint "eagle-import:C0603")
      (libsource (lib "eagle-import") (part "rcl_334_C-EUC0603"))
    )
    (comp (ref "C6")
      (value "1u")
      (footprint "eagle-import:C0603")
      (libsource (lib "eagle-import") (part "rcl_334_C-EUC0603"))
    )
    (comp (ref "C7")
      (value "820p")
      (footprint "eagle-import:C0402")
      (libsource (lib "eagle-import") (part "rcl_334_C-EUC0402"))
    )
    (comp (ref "C8")
      (value "47p")
      (footprint "eagle-import:C0402")
      (libsource (lib "eagle-import") (part "rcl_334_C-EUC0402"))
    )
    (comp (ref "C9")
      (value "2.2u")
      (footprint "eagle-import:C0603")
      (libsource (lib "eagle-import") (part "rcl_334_C-EUC0603"))
    )
    (comp (ref "C10")
      (value "68p")
      (footprint "eagle-import:C0402")
      (libsource (lib "eagle-import") (part "rcl_334_C-EUC0402"))
    )
    (comp (ref "C11")
      (value "10u")
      (footprint "eagle-import:C1206")
      (libsource (lib "eagle-import") (part "rcl_334_C-EUC1206"))
    )
    (comp (ref "C12")
      (value "6.8n")
      (footprint "eagle-import:C0402")
      (libsource (lib "eagle-import") (part "rcl_334_C-EUC0402"))
    )
    (comp (ref "C13")
      (value "1u")
      (footprint "eagle-import:C0603")
      (libsource (lib "eagle-import") (part "rcl_334_C-EUC0603"))
    )
    (comp (ref "C14")
      (value "1u")
      (footprint "eagle-import:C0402")
      (libsource (lib "eagle-import") (part "rcl_334_C-EUC0402"))
    )
    (comp (ref "C15")
      (value "100n")
      (footprint "eagle-import:C0402")
      (libsource (lib "eagle-import") (part "rcl_334_C-EUC0402"))
    )
    (comp (ref "C16")
      (value "2.2u")
      (footprint "eagle-import:C0603")
      (libsource (lib "eagle-import") (part "rcl_334_C-EUC0603"))
    )
    (comp (ref "C17")
      (value "1u")
      (footprint "eagle-import:C0603")
      (libsource (lib "eagle-import") (part "rcl_334_C-EUC0603"))
    )
    (comp (ref "C137")
      (value "1u")
      (footprint "eagle-import:C0402")
      (libsource (lib "eagle-import") (part "rcl_334_C-EUC0402"))
    )
    (comp (ref "C148")
      (value "1u")
      (footprint "eagle-import:C0603")
      (libsource (lib "eagle-import") (part "rcl_334_C-EUC0603"))
    )
    (comp (ref "C149")
      (value "1u")
      (footprint "eagle-import:C0603")
      (libsource (lib "eagle-import") (part "rcl_334_C-EUC0603"))
    )
    (comp (ref "D1")
      (value "DIODE")
      (footprint "eagle-import:SOD-323-DIODE")
      (libsource (lib "eagle-import") (part "DIODE"))
    )
    (comp (ref "D2")
      (value "DIODE")
      (footprint "eagle-import:SOD-323-DIODE")
      (libsource (lib "eagle-import") (part "DIODE"))
    )
    (comp (ref "IC1")
      (value "ADP7118")
      (footprint "eagle-import:TSOT23-5")
      (libsource (lib "eagle-import") (part "ADP7118"))
    )
    (comp (ref "IC2")
      (value "ADP5070EP")
      (footprint "eagle-import:TSSOP-EP-20")
      (libsource (lib "eagle-import") (part "ADP5070EP"))
    )
    (comp (ref "IC3")
      (value "ADP7182")
      (footprint "eagle-import:TSOT23-5")
      (libsource (lib "eagle-import") (part "ADP7182"))
    )
    (comp (ref "JACK")
      (value "DC_JACK2.1MM")
      (footprint "eagle-import:DC_POWER_INPUT_2.1MM")
      (libsource (lib "eagle-import") (part "DC_JACK2.1MM"))
    )
    (comp (ref "L1")
      (value "1.5u")
      (footprint "eagle-import:IND_LPS4012_V2")
      (libsource (lib "eagle-import") (part "INDLPS4012_L"))
    )
    (comp (ref "L2")
      (value "INDLPS6225_L")
      (footprint "eagle-import:IND_LPS6225_V2")
      (libsource (lib "eagle-import") (part "INDLPS6225_L"))
    )
    (comp (ref "L3")
      (value "INDLPS6225_L")
      (footprint "eagle-import:IND_LPS6225_V2")
      (libsource (lib "eagle-import") (part "INDLPS6225_L"))
    )
    (comp (ref "L4")
      (value "1.5u")
      (footprint "eagle-import:IND_LPS4012_V2")
      (libsource (lib "eagle-import") (part "INDLPS4012_L"))
    )
    (comp (ref "R1")
      (value "180k")
      (footprint "eagle-import:R0402")
      (libsource (lib "eagle-import") (part "rcl_334_R-EU_R0402"))
    )
    (comp (ref "R2")
      (value "180k")
      (footprint "eagle-import:R0402")
      (libsource (lib "eagle-import") (part "rcl_334_R-EU_R0402"))
    )
    (comp (ref "R3")
      (value "10k")
      (footprint "eagle-import:R0402")
      (libsource (lib "eagle-import") (part "rcl_334_R-EU_R0402"))
    )
    (comp (ref "R4")
      (value "10k")
      (footprint "eagle-import:R0402")
      (libsource (lib "eagle-import") (part "rcl_334_R-EU_R0402"))
    )
    (comp (ref "R5")
      (value "6.04")
      (footprint "eagle-import:R0402")
      (libsource (lib "eagle-import") (part "rcl_334_R-EU_R0402"))
    )
    (comp (ref "R6")
      (value "63.4k")
      (footprint "eagle-import:R0402")
      (libsource (lib "eagle-import") (part "rcl_334_R-EU_R0402"))
    )
    (comp (ref "R7")
      (value "3.57k")
      (footprint "eagle-import:R0402")
      (libsource (lib "eagle-import") (part "rcl_334_R-EU_R0402"))
    )
    (comp (ref "R8")
      (value "8.45k")
      (footprint "eagle-import:R0402")
      (libsource (lib "eagle-import") (part "rcl_334_R-EU_R0402"))
    )
    (comp (ref "R9")
      (value "100k")
      (footprint "eagle-import:R0402")
      (libsource (lib "eagle-import") (part "rcl_334_R-EU_R0402"))
    )
    (comp (ref "R10")
      (value "2.8k")
      (footprint "eagle-import:R0402")
      (libsource (lib "eagle-import") (part "rcl_334_R-EU_R0402"))
    )
    (comp (ref "R11")
      (value "150k")
      (footprint "eagle-import:R0402")
      (libsource (lib "eagle-import") (part "rcl_334_R-EU_R0402"))
    )
    (comp (ref "R12")
      (value "54.9k")
      (footprint "eagle-import:R0402")
      (libsource (lib "eagle-import") (part "rcl_334_R-EU_R0402"))
    )
    (comp (ref "R13")
      (value "5.76k")
      (footprint "eagle-import:R0402")
      (libsource (lib "eagle-import") (part "rcl_334_R-EU_R0402"))
    )
    (comp (ref "R14")
      (value "215k")
      (footprint "eagle-import:R0402")
      (libsource (lib "eagle-import") (part "rcl_334_R-EU_R0402"))
    )
    (comp (ref "R15")
      (value "10k")
      (footprint "eagle-import:R0402")
      (libsource (lib "eagle-import") (part "rcl_334_R-EU_R0402"))
    )
    (comp (ref "R16")
      (value "10k")
      (footprint "eagle-import:R0402")
      (libsource (lib "eagle-import") (part "rcl_334_R-EU_R0402"))
    )
    (comp (ref "R17")
      (value "5.36")
      (footprint "eagle-import:R0402")
      (libsource (lib "eagle-import") (part "rcl_334_R-EU_R0402"))
    )
    (comp (ref "R78")
      (value "100k")
      (footprint "eagle-import:R0402")
      (libsource (lib "eagle-import") (part "rcl_334_R-EU_R0402"))
    )
    (comp (ref "R79")
      (value "100k")
      (footprint "eagle-import:R0402")
      (libsource (lib "eagle-import") (part "rcl_334_R-EU_R0402"))
    )
    (comp (ref "R87")
      (value "100k")
      (footprint "eagle-import:R0402")
      (libsource (lib "eagle-import") (part "rcl_334_R-EU_R0402"))
    )
    (comp (ref "R88")
      (value "100k")
      (footprint "eagle-import:R0402")
      (libsource (lib "eagle-import") (part "rcl_334_R-EU_R0402"))
    )
    (comp (ref "C60")
      (value "4.7uF")
      (footprint "eagle-import:C0603")
      (libsource (lib "eagle-import") (part "rcl_334_C-EUC0603"))
    )
    (comp (ref "C61")
      (value "100nF")
      (footprint "eagle-import:C0402")
      (libsource (lib "eagle-import") (part "rcl_334_C-EUC0402"))
    )
    (comp (ref "C62")
      (value "100pF")
      (footprint "eagle-import:C0603")
      (libsource (lib "eagle-import") (part "rcl_334_C-EUC0603"))
    )
    (comp (ref "C63")
      (value "100nF")
      (footprint "eagle-import:C0402")
      (libsource (lib "eagle-import") (part "rcl_334_C-EUC0402"))
    )
    (comp (ref "C64")
      (value "100nF")
      (footprint "eagle-import:C0402")
      (libsource (lib "eagle-import") (part "rcl_334_C-EUC0402"))
    )
    (comp (ref "C65")
      (value "100nF")
      (footprint "eagle-import:C0402")
      (libsource (lib "eagle-import") (part "rcl_334_C-EUC0402"))
    )
    (comp (ref "C66")
      (value "100nF")
      (footprint "eagle-import:C0402")
      (libsource (lib "eagle-import") (part "rcl_334_C-EUC0402"))
    )
    (comp (ref "C67")
      (value "100pF")
      (footprint "eagle-import:C050-025X075")
      (libsource (lib "eagle-import") (part "C-US050-025X075"))
    )
    (comp (ref "C68")
      (value "100pF")
      (footprint "eagle-import:C050-025X075")
      (libsource (lib "eagle-import") (part "C-US050-025X075"))
    )
    (comp (ref "C69")
      (value "4.7uF")
      (footprint "eagle-import:C0603")
      (libsource (lib "eagle-import") (part "rcl_334_C-EUC0603"))
    )
    (comp (ref "C70")
      (value "4.7uF")
      (footprint "eagle-import:C0603")
      (libsource (lib "eagle-import") (part "rcl_334_C-EUC0603"))
    )
    (comp (ref "C71")
      (value "5.6nF")
      (footprint "eagle-import:C050-025X075")
      (libsource (lib "eagle-import") (part "C-US050-025X075"))
    )
    (comp (ref "C72")
      (value "5.6nF")
      (footprint "eagle-import:C050-025X075")
      (libsource (lib "eagle-import") (part "C-US050-025X075"))
    )
    (comp (ref "C73")
      (value "100nF")
      (footprint "eagle-import:C0402")
      (libsource (lib "eagle-import") (part "rcl_334_C-EUC0402"))
    )
    (comp (ref "C74")
      (value "100nF")
      (footprint "eagle-import:C0402")
      (libsource (lib "eagle-import") (part "rcl_334_C-EUC0402"))
    )
    (comp (ref "C75")
      (value "2.7nF")
      (footprint "eagle-import:C050-025X075")
      (libsource (lib "eagle-import") (part "C-US050-025X075"))
    )
    (comp (ref "C76")
      (value "4.7uF")
      (footprint "eagle-import:C0603")
      (libsource (lib "eagle-import") (part "rcl_334_C-EUC0603"))
    )
    (comp (ref "C77")
      (value "4.7uF")
      (footprint "eagle-import:C0603")
      (libsource (lib "eagle-import") (part "rcl_334_C-EUC0603"))
    )
    (comp (ref "C78")
      (value "2.7nF")
      (footprint "eagle-import:C050-025X075")
      (libsource (lib "eagle-import") (part "C-US050-025X075"))
    )
    (comp (ref "C79")
      (value "100nF")
      (footprint "eagle-import:C0402")
      (libsource (lib "eagle-import") (part "rcl_334_C-EUC0402"))
    )
    (comp (ref "C80")
      (value "100nF")
      (footprint "eagle-import:C0402")
      (libsource (lib "eagle-import") (part "rcl_334_C-EUC0402"))
    )
    (comp (ref "C81")
      (value "3.9nF")
      (footprint "eagle-import:C050-025X075")
      (libsource (lib "eagle-import") (part "C-US050-025X075"))
    )
    (comp (ref "C82")
      (value "4.7uF")
      (footprint "eagle-import:C0603")
      (libsource (lib "eagle-import") (part "rcl_334_C-EUC0603"))
    )
    (comp (ref "C83")
      (value "4.7uF")
      (footprint "eagle-import:C0603")
      (libsource (lib "eagle-import") (part "rcl_334_C-EUC0603"))
    )
    (comp (ref "IC10")
      (value "AD797")
      (footprint "eagle-import:SO08")
      (libsource (lib "eagle-import") (part "AD797"))
    )
    (comp (ref "IC11")
      (value "AD797")
      (footprint "eagle-import:SO08")
      (libsource (lib "eagle-import") (part "AD797"))
    )
    (comp (ref "IC12")
      (value "AD797")
      (footprint "eagle-import:SO08")
      (libsource (lib "eagle-import") (part "AD797"))
    )
    (comp (ref "J4")
      (value "RCARCA")
      (footprint "eagle-import:RCA")
      (libsource (lib "eagle-import") (part "RCARCA"))
    )
    (comp (ref "R39")
      (value "2k")
      (footprint "eagle-import:R0402")
      (libsource (lib "eagle-import") (part "rcl_334_R-EU_R0402"))
    )
    (comp (ref "R40")
      (value "806")
      (footprint "eagle-import:R0402")
      (libsource (lib "eagle-import") (part "rcl_334_R-EU_R0402"))
    )
    (comp (ref "R41")
      (value "806")
      (footprint "eagle-import:R0402")
      (libsource (lib "eagle-import") (part "rcl_334_R-EU_R0402"))
    )
    (comp (ref "R42")
      (value "2k")
      (footprint "eagle-import:R0402")
      (libsource (lib "eagle-import") (part "rcl_334_R-EU_R0402"))
    )
    (comp (ref "R43")
      (value "100")
      (footprint "eagle-import:R0402")
      (libsource (lib "eagle-import") (part "rcl_334_R-EU_R0402"))
    )
    (comp (ref "R44")
      (value "100")
      (footprint "eagle-import:R0402")
      (libsource (lib "eagle-import") (part "rcl_334_R-EU_R0402"))
    )
    (comp (ref "R45")
      (value "2.0k")
      (footprint "eagle-import:R0402")
      (libsource (lib "eagle-import") (part "rcl_334_R-EU_R0402"))
    )
    (comp (ref "R46")
      (value "2.0k")
      (footprint "eagle-import:R0402")
      (libsource (lib "eagle-import") (part "rcl_334_R-EU_R0402"))
    )
    (comp (ref "R47")
      (value "681")
      (footprint "eagle-import:R0402")
      (libsource (lib "eagle-import") (part "rcl_334_R-EU_R0402"))
    )
    (comp (ref "R48")
      (value "681")
      (footprint "eagle-import:R0402")
      (libsource (lib "eagle-import") (part "rcl_334_R-EU_R0402"))
    )
    (comp (ref "R49")
      (value "226")
      (footprint "eagle-import:R0402")
      (libsource (lib "eagle-import") (part "rcl_334_R-EU_R0402"))
    )
    (comp (ref "R50")
      (value "226")
      (footprint "eagle-import:R0402")
      (libsource (lib "eagle-import") (part "rcl_334_R-EU_R0402"))
    )
    (comp (ref "R51")
      (value "324")
      (footprint "eagle-import:R0402")
      (libsource (lib "eagle-import") (part "rcl_334_R-EU_R0402"))
    )
    (comp (ref "R52")
      (value "324")
      (footprint "eagle-import:R0402")
      (libsource (lib "eagle-import") (part "rcl_334_R-EU_R0402"))
    )
    (comp (ref "R53")
      (value "100")
      (footprint "eagle-import:R0402")
      (libsource (lib "eagle-import") (part "rcl_334_R-EU_R0402"))
    )
    (comp (ref "R54")
      (value "332")
      (footprint "eagle-import:R0402")
      (libsource (lib "eagle-import") (part "rcl_334_R-EU_R0402"))
    )
    (comp (ref "C104")
      (value "100nF")
      (footprint "eagle-import:C0402")
      (libsource (lib "eagle-import") (part "rcl_334_C-EUC0402"))
    )
    (comp (ref "C105")
      (value "100nF")
      (footprint "eagle-import:C0402")
      (libsource (lib "eagle-import") (part "rcl_334_C-EUC0402"))
    )
    (comp (ref "C119")
      (value "100nF")
      (footprint "eagle-import:C0402")
      (libsource (lib "eagle-import") (part "rcl_334_C-EUC0402"))
    )
    (comp (ref "C121")
      (value "100nF")
      (footprint "eagle-import:C0402")
      (libsource (lib "eagle-import") (part "rcl_334_C-EUC0402"))
    )
    (comp (ref "C122")
      (value "10nF")
      (footprint "eagle-import:C0402")
      (libsource (lib "eagle-import") (part "C-EUC0402"))
    )
    (comp (ref "C126")
      (value "100nF")
      (footprint "eagle-import:C0402")
      (libsource (lib "eagle-import") (part "rcl_334_C-EUC0402"))
    )
    (comp (ref "C127")
      (value "100nF")
      (footprint "eagle-import:C0402")
      (libsource (lib "eagle-import") (part "rcl_334_C-EUC0402"))
    )
    (comp (ref "C128")
      (value "100nF")
      (footprint "eagle-import:C0402")
      (libsource (lib "eagle-import") (part "rcl_334_C-EUC0402"))
    )
    (comp (ref "C130")
      (value "330nF")
      (footprint "eagle-import:C0402")
      (libsource (lib "eagle-import") (part "rcl_334_C-EUC0402"))
    )
    (comp (ref "C131")
      (value "330nF")
      (footprint "eagle-import:C0402")
      (libsource (lib "eagle-import") (part "rcl_334_C-EUC0402"))
    )
    (comp (ref "C132")
      (value "10uF")
      (footprint "eagle-import:C0603")
      (libsource (lib "eagle-import") (part "rcl_334_C-EUC0603"))
    )
    (comp (ref "C140")
      (value "10nF")
      (footprint "eagle-import:C0402")
      (libsource (lib "eagle-import") (part "C-EUC0402"))
    )
    (comp (ref "C143")
      (value "100nF")
      (footprint "eagle-import:C0402")
      (libsource (lib "eagle-import") (part "rcl_334_C-EUC0402"))
    )
    (comp (ref "CLKIN")
      (value "STEREO_JACK")
      (footprint "eagle-import:35RASMT2BHNTRX")
      (libsource (lib "eagle-import") (part "STEREO_JACK"))
    )
    (comp (ref "GND174")
      (value "TP")
      (footprint "eagle-import:TP_1")
      (libsource (lib "eagle-import") (part "TP"))
    )
    (comp (ref "IC22")
      (value "SN74LVC1G125")
      (footprint "eagle-import:SOT23-5")
      (libsource (lib "eagle-import") (part "SN74LVC1G125"))
    )
    (comp (ref "IC25")
      (value "ATXMEGAxxxA4U-AU")
      (footprint "eagle-import:QFP80P1200X1200X120-44N")
      (libsource (lib "eagle-import") (part "AT-XMEGA-XXA4-AU"))
    )
    (comp (ref "IC32")
      (value "VHC1GT126")
      (footprint "eagle-import:SC-70-5")
      (libsource (lib "eagle-import") (part "VHC1GT126"))
    )
    (comp (ref "IC33")
      (value "VHC1GT126")
      (footprint "eagle-import:SC-70-5")
      (libsource (lib "eagle-import") (part "VHC1GT126"))
    )
    (comp (ref "IC35")
      (value "VHC1GT125")
      (footprint "eagle-import:SC-70-5")
      (libsource (lib "eagle-import") (part "VHC1GT125"))
    )
    (comp (ref "L12")
      (value "???")
      (footprint "eagle-import:R0805")
      (libsource (lib "eagle-import") (part "rcl_334_R-EU_R0805"))
    )
    (comp (ref "OSC2")
      (value "OSCILLATOR")
      (footprint "eagle-import:OSCILLATOR_3.2X2.5")
      (libsource (lib "eagle-import") (part "OSCILLATOR"))
    )
    (comp (ref "PDI")
      (value "MA03-2")
      (footprint "eagle-import:MA03-2")
      (libsource (lib "eagle-import") (part "MA03-2"))
    )
    (comp (ref "R19")
      (value "15k")
      (footprint "eagle-import:R0402")
      (libsource (lib "eagle-import") (part "R-EU_R0402"))
    )
    (comp (ref "R62")
      (value "15k")
      (footprint "eagle-import:R0402")
      (libsource (lib "eagle-import") (part "R-EU_R0402"))
    )
    (comp (ref "R66")
      (value "100")
      (footprint "eagle-import:R0402")
      (libsource (lib "eagle-import") (part "rcl_334_R-EU_R0402"))
    )
    (comp (ref "R89")
      (value "100k")
      (footprint "eagle-import:R0402")
      (libsource (lib "eagle-import") (part "rcl_334_R-EU_R0402"))
    )
    (comp (ref "STATE")
      (value "GREEN")
      (footprint "eagle-import:LED_HAND")
      (libsource (lib "eagle-import") (part "LEDHAND"))
    )
    (comp (ref "C106")
      (value "100nF")
      (footprint "eagle-import:C0402")
      (libsource (lib "eagle-import") (part "rcl_334_C-EUC0402"))
    )
    (comp (ref "C107")
      (value "47pF")
      (footprint "eagle-import:C0402")
      (libsource (lib "eagle-import") (part "rcl_334_C-EUC0402"))
    )
    (comp (ref "C108")
      (value "47pF")
      (footprint "eagle-import:C0402")
      (libsource (lib "eagle-import") (part "rcl_334_C-EUC0402"))
    )
    (comp (ref "C111")
      (value "100nF")
      (footprint "eagle-import:C0402")
      (libsource (lib "eagle-import") (part "rcl_334_C-EUC0402"))
    )
    (comp (ref "C112")
      (value "4.7uF")
      (footprint "eagle-import:A_3216-18W")
      (libsource (lib "eagle-import") (part "CPOL-EUA/3216-18W"))
    )
    (comp (ref "C113")
      (value "100nF")
      (footprint "eagle-import:C0402")
      (libsource (lib "eagle-import") (part "rcl_334_C-EUC0402"))
    )
    (comp (ref "C114")
      (value "100nF")
      (footprint "eagle-import:C0402")
      (libsource (lib "eagle-import") (part "rcl_334_C-EUC0402"))
    )
    (comp (ref "C115")
      (value "10uF")
      (footprint "eagle-import:C0603")
      (libsource (lib "eagle-import") (part "rcl_334_C-EUC0603"))
    )
    (comp (ref "C116")
      (value "10uF")
      (footprint "eagle-import:C0603")
      (libsource (lib "eagle-import") (part "rcl_334_C-EUC0603"))
    )
    (comp (ref "C117")
      (value "100nF")
      (footprint "eagle-import:C0402")
      (libsource (lib "eagle-import") (part "rcl_334_C-EUC0402"))
    )
    (comp (ref "C118")
      (value "100nF")
      (footprint "eagle-import:C0402")
      (libsource (lib "eagle-import") (part "rcl_334_C-EUC0402"))
    )
    (comp (ref "CUSB2")
      (value "4.7nF")
      (footprint "eagle-import:C0402")
      (libsource (lib "eagle-import") (part "rcl_334_C-EUC0402"))
    )
    (comp (ref "GND26")
      (value "TP")
      (footprint "eagle-import:TP_1")
      (libsource (lib "eagle-import") (part "TP"))
    )
    (comp (ref "IC17")
      (value "USBLC6-2SC6")
      (footprint "eagle-import:SOT23-6L")
      (libsource (lib "eagle-import") (part "USBLC6-2"))
    )
    (comp (ref "IC19")
      (value "FT232RL")
      (footprint "eagle-import:SSOP28")
      (libsource (lib "eagle-import") (part "FT232RL"))
    )
    (comp (ref "IC20")
      (value "LP5907MFX-3.3")
      (footprint "eagle-import:TSOT23-5")
      (libsource (lib "eagle-import") (part "TLV700XX"))
    )
    (comp (ref "IC21")
      (value "SI8642BC-B-IS1")
      (footprint "eagle-import:NSOIC-16")
      (libsource (lib "eagle-import") (part "SI8645"))
    )
    (comp (ref "L10")
      (value "???")
      (footprint "eagle-import:R0805")
      (libsource (lib "eagle-import") (part "rcl_334_R-EU_R0805"))
    )
    (comp (ref "RUSB2")
      (value "1M")
      (footprint "eagle-import:R0402")
      (libsource (lib "eagle-import") (part "rcl_334_R-EU_R0402"))
    )
    (comp (ref "USB2")
      (value "USB_MINI_B")
      (footprint "eagle-import:240-0002-1")
      (libsource (lib "eagle-import") (part "USB_MINI_B"))
    )
    (comp (ref "C34")
      (value "100nF")
      (footprint "eagle-import:C0402")
      (libsource (lib "eagle-import") (part "rcl_334_C-EUC0402"))
    )
    (comp (ref "C35")
      (value "47u")
      (footprint "eagle-import:C_6032-28W")
      (libsource (lib "eagle-import") (part "CPOL-EUC/6032-28W"))
    )
    (comp (ref "C36")
      (value "4.7uF")
      (footprint "eagle-import:C0603")
      (libsource (lib "eagle-import") (part "rcl_334_C-EUC0603"))
    )
    (comp (ref "C37")
      (value "100nF")
      (footprint "eagle-import:C0402")
      (libsource (lib "eagle-import") (part "rcl_334_C-EUC0402"))
    )
    (comp (ref "C38")
      (value "100pF")
      (footprint "eagle-import:C0603")
      (libsource (lib "eagle-import") (part "rcl_334_C-EUC0603"))
    )
    (comp (ref "C39")
      (value "100nF")
      (footprint "eagle-import:C0402")
      (libsource (lib "eagle-import") (part "rcl_334_C-EUC0402"))
    )
    (comp (ref "C40")
      (value "100nF")
      (footprint "eagle-import:C0402")
      (libsource (lib "eagle-import") (part "rcl_334_C-EUC0402"))
    )
    (comp (ref "C41")
      (value "100nF")
      (footprint "eagle-import:C0402")
      (libsource (lib "eagle-import") (part "rcl_334_C-EUC0402"))
    )
    (comp (ref "C42")
      (value "100nF")
      (footprint "eagle-import:C0402")
      (libsource (lib "eagle-import") (part "rcl_334_C-EUC0402"))
    )
    (comp (ref "C43")
      (value "100pF")
      (footprint "eagle-import:C050-025X075")
      (libsource (lib "eagle-import") (part "C-US050-025X075"))
    )
    (comp (ref "C44")
      (value "100pF")
      (footprint "eagle-import:C050-025X075")
      (libsource (lib "eagle-import") (part "C-US050-025X075"))
    )
    (comp (ref "C45")
      (value "4.7uF")
      (footprint "eagle-import:C0603")
      (libsource (lib "eagle-import") (part "rcl_334_C-EUC0603"))
    )
    (comp (ref "C46")
      (value "4.7uF")
      (footprint "eagle-import:C0603")
      (libsource (lib "eagle-import") (part "rcl_334_C-EUC0603"))
    )
    (comp (ref "C47")
      (value "5.6nF")
      (footprint "eagle-import:C050-025X075")
      (libsource (lib "eagle-import") (part "C-US050-025X075"))
    )
    (comp (ref "C48")
      (value "5.6nF")
      (footprint "eagle-import:C050-025X075")
      (libsource (lib "eagle-import") (part "C-US050-025X075"))
    )
    (comp (ref "C49")
      (value "100nF")
      (footprint "eagle-import:C0402")
      (libsource (lib "eagle-import") (part "rcl_334_C-EUC0402"))
    )
    (comp (ref "C50")
      (value "100nF")
      (footprint "eagle-import:C0402")
      (libsource (lib "eagle-import") (part "rcl_334_C-EUC0402"))
    )
    (comp (ref "C51")
      (value "2.7nF")
      (footprint "eagle-import:C050-025X075")
      (libsource (lib "eagle-import") (part "C-US050-025X075"))
    )
    (comp (ref "C52")
      (value "4.7uF")
      (footprint "eagle-import:C0603")
      (libsource (lib "eagle-import") (part "rcl_334_C-EUC0603"))
    )
    (comp (ref "C53")
      (value "4.7uF")
      (footprint "eagle-import:C0603")
      (libsource (lib "eagle-import") (part "rcl_334_C-EUC0603"))
    )
    (comp (ref "C54")
      (value "2.7nF")
      (footprint "eagle-import:C050-025X075")
      (libsource (lib "eagle-import") (part "C-US050-025X075"))
    )
    (comp (ref "C55")
      (value "100nF")
      (footprint "eagle-import:C0402")
      (libsource (lib "eagle-import") (part "rcl_334_C-EUC0402"))
    )
    (comp (ref "C56")
      (value "100nF")
      (footprint "eagle-import:C0402")
      (libsource (lib "eagle-import") (part "rcl_334_C-EUC0402"))
    )
    (comp (ref "C57")
      (value "3.9nF")
      (footprint "eagle-import:C050-025X075")
      (libsource (lib "eagle-import") (part "C-US050-025X075"))
    )
    (comp (ref "C58")
      (value "4.7uF")
      (footprint "eagle-import:C0603")
      (libsource (lib "eagle-import") (part "rcl_334_C-EUC0603"))
    )
    (comp (ref "C59")
      (value "4.7uF")
      (footprint "eagle-import:C0603")
      (libsource (lib "eagle-import") (part "rcl_334_C-EUC0603"))
    )
    (comp (ref "IC7")
      (value "AD797")
      (footprint "eagle-import:SO08")
      (libsource (lib "eagle-import") (part "AD797"))
    )
    (comp (ref "IC8")
      (value "AD797")
      (footprint "eagle-import:SO08")
      (libsource (lib "eagle-import") (part "AD797"))
    )
    (comp (ref "IC9")
      (value "AD797")
      (footprint "eagle-import:SO08")
      (libsource (lib "eagle-import") (part "AD797"))
    )
    (comp (ref "J3")
      (value "RCARCA")
      (footprint "eagle-import:RCA")
      (libsource (lib "eagle-import") (part "RCARCA"))
    )
    (comp (ref "R21")
      (value "2.21k")
      (footprint "eagle-import:R0402")
      (libsource (lib "eagle-import") (part "rcl_334_R-EU_R0402"))
    )
    (comp (ref "R22")
      (value "2.80k")
      (footprint "eagle-import:R0402")
      (libsource (lib "eagle-import") (part "rcl_334_R-EU_R0402"))
    )
    (comp (ref "R23")
      (value "2k")
      (footprint "eagle-import:R0402")
      (libsource (lib "eagle-import") (part "rcl_334_R-EU_R0402"))
    )
    (comp (ref "R24")
      (value "806")
      (footprint "eagle-import:R0402")
      (libsource (lib "eagle-import") (part "rcl_334_R-EU_R0402"))
    )
    (comp (ref "R25")
      (value "806")
      (footprint "eagle-import:R0402")
      (libsource (lib "eagle-import") (part "rcl_334_R-EU_R0402"))
    )
    (comp (ref "R26")
      (value "2k")
      (footprint "eagle-import:R0402")
      (libsource (lib "eagle-import") (part "rcl_334_R-EU_R0402"))
    )
    (comp (ref "R27")
      (value "100")
      (footprint "eagle-import:R0402")
      (libsource (lib "eagle-import") (part "rcl_334_R-EU_R0402"))
    )
    (comp (ref "R28")
      (value "100")
      (footprint "eagle-import:R0402")
      (libsource (lib "eagle-import") (part "rcl_334_R-EU_R0402"))
    )
    (comp (ref "R29")
      (value "2.0k")
      (footprint "eagle-import:R0402")
      (libsource (lib "eagle-import") (part "rcl_334_R-EU_R0402"))
    )
    (comp (ref "R30")
      (value "2.0k")
      (footprint "eagle-import:R0402")
      (libsource (lib "eagle-import") (part "rcl_334_R-EU_R0402"))
    )
    (comp (ref "R31")
      (value "681")
      (footprint "eagle-import:R0402")
      (libsource (lib "eagle-import") (part "rcl_334_R-EU_R0402"))
    )
    (comp (ref "R32")
      (value "681")
      (footprint "eagle-import:R0402")
      (libsource (lib "eagle-import") (part "rcl_334_R-EU_R0402"))
    )
    (comp (ref "R33")
      (value "226")
      (footprint "eagle-import:R0402")
      (libsource (lib "eagle-import") (part "rcl_334_R-EU_R0402"))
    )
    (comp (ref "R34")
      (value "226")
      (footprint "eagle-import:R0402")
      (libsource (lib "eagle-import") (part "rcl_334_R-EU_R0402"))
    )
    (comp (ref "R35")
      (value "324")
      (footprint "eagle-import:R0402")
      (libsource (lib "eagle-import") (part "rcl_334_R-EU_R0402"))
    )
    (comp (ref "R36")
      (value "324")
      (footprint "eagle-import:R0402")
      (libsource (lib "eagle-import") (part "rcl_334_R-EU_R0402"))
    )
    (comp (ref "R37")
      (value "100")
      (footprint "eagle-import:R0402")
      (libsource (lib "eagle-import") (part "rcl_334_R-EU_R0402"))
    )
    (comp (ref "R38")
      (value "332")
      (footprint "eagle-import:R0402")
      (libsource (lib "eagle-import") (part "rcl_334_R-EU_R0402"))
    )
    (comp (ref "C120")
      (value "100nF")
      (footprint "eagle-import:C0402")
      (libsource (lib "eagle-import") (part "rcl_334_C-EUC0402"))
    )
    (comp (ref "C123")
      (value "100nF")
      (footprint "eagle-import:C0402")
      (libsource (lib "eagle-import") (part "rcl_334_C-EUC0402"))
    )
    (comp (ref "C133")
      (value "100nF")
      (footprint "eagle-import:C0402")
      (libsource (lib "eagle-import") (part "rcl_334_C-EUC0402"))
    )
    (comp (ref "C134")
      (value "100nF")
      (footprint "eagle-import:C0402")
      (libsource (lib "eagle-import") (part "rcl_334_C-EUC0402"))
    )
    (comp (ref "C135")
      (value "100nF")
      (footprint "eagle-import:C0402")
      (libsource (lib "eagle-import") (part "rcl_334_C-EUC0402"))
    )
    (comp (ref "C136")
      (value "100nF")
      (footprint "eagle-import:C0402")
      (libsource (lib "eagle-import") (part "rcl_334_C-EUC0402"))
    )
    (comp (ref "C144")
      (value "10nF")
      (footprint "eagle-import:C0402")
      (libsource (lib "eagle-import") (part "C-EUC0402"))
    )
    (comp (ref "C145")
      (value "10nF")
      (footprint "eagle-import:C0402")
      (libsource (lib "eagle-import") (part "C-EUC0402"))
    )
    (comp (ref "C146")
      (value "100nF")
      (footprint "eagle-import:C0402")
      (libsource (lib "eagle-import") (part "C-EUC0402"))
    )
    (comp (ref "C147")
      (value "100nF")
      (footprint "eagle-import:C0402")
      (libsource (lib "eagle-import") (part "C-EUC0402"))
    )
    (comp (ref "IC23")
      (value "SN74LVC1G125")
      (footprint "eagle-import:SOT23-5")
      (libsource (lib "eagle-import") (part "SN74LVC1G125"))
    )
    (comp (ref "IC24")
      (value "SN74LVC1G125")
      (footprint "eagle-import:SOT23-5")
      (libsource (lib "eagle-import") (part "SN74LVC1G125"))
    )
    (comp (ref "IC26")
      (value "OPA365")
      (footprint "eagle-import:SOT23-5")
      (libsource (lib "eagle-import") (part "OPA365"))
    )
    (comp (ref "IC27")
      (value "OPA365")
      (footprint "eagle-import:SOT23-5")
      (libsource (lib "eagle-import") (part "OPA365"))
    )
    (comp (ref "IC28")
      (value "M74VHC1GT50DTT1G")
      (footprint "eagle-import:SOT23-5")
      (libsource (lib "eagle-import") (part "SN74LVC1G125"))
    )
    (comp (ref "IC29")
      (value "M74VHC1GT50DTT1G")
      (footprint "eagle-import:SOT23-5")
      (libsource (lib "eagle-import") (part "SN74LVC1G125"))
    )
    (comp (ref "IC30")
      (value "SN74LVC1G125")
      (footprint "eagle-import:SOT23-5")
      (libsource (lib "eagle-import") (part "SN74LVC1G125"))
    )
    (comp (ref "IC31")
      (value "SN74LVC1G125")
      (footprint "eagle-import:SOT23-5")
      (libsource (lib "eagle-import") (part "SN74LVC1G125"))
    )
    (comp (ref "JP2")
      (value "JP2E")
      (footprint "eagle-import:JP2")
      (libsource (lib "eagle-import") (part "JP2E"))
    )
    (comp (ref "R61")
      (value "100k")
      (footprint "eagle-import:R0402")
      (libsource (lib "eagle-import") (part "rcl_334_R-EU_R0402"))
    )
    (comp (ref "R67")
      (value "100k")
      (footprint "eagle-import:R0402")
      (libsource (lib "eagle-import") (part "rcl_334_R-EU_R0402"))
    )
    (comp (ref "R68")
      (value "100k")
      (footprint "eagle-import:R0402")
      (libsource (lib "eagle-import") (part "rcl_334_R-EU_R0402"))
    )
    (comp (ref "R81")
      (value "15k")
      (footprint "eagle-import:R0402")
      (libsource (lib "eagle-import") (part "R-EU_R0402"))
    )
    (comp (ref "R82")
      (value "15k")
      (footprint "eagle-import:R0402")
      (libsource (lib "eagle-import") (part "R-EU_R0402"))
    )
    (comp (ref "R83")
      (value "24k")
      (footprint "eagle-import:R0402")
      (libsource (lib "eagle-import") (part "R-EU_R0402"))
    )
    (comp (ref "R84")
      (value "15k")
      (footprint "eagle-import:R0402")
      (libsource (lib "eagle-import") (part "R-EU_R0402"))
    )
    (comp (ref "R85")
      (value "24k")
      (footprint "eagle-import:R0402")
      (libsource (lib "eagle-import") (part "R-EU_R0402"))
    )
    (comp (ref "R86")
      (value "15k")
      (footprint "eagle-import:R0402")
      (libsource (lib "eagle-import") (part "R-EU_R0402"))
    )
    (comp (ref "X1")
      (value "CON_3.5MM_1X12")
      (footprint "eagle-import:CON_3.5MM_1X12")
      (libsource (lib "eagle-import") (part "CON_3.5MM_1X12"))
    )
    (comp (ref "C18")
      (value "10uF")
      (footprint "eagle-import:C0603")
      (libsource (lib "eagle-import") (part "rcl_334_C-EUC0603"))
    )
    (comp (ref "C19")
      (value "10uF")
      (footprint "eagle-import:C0603")
      (libsource (lib "eagle-import") (part "rcl_334_C-EUC0603"))
    )
    (comp (ref "C20")
      (value "100nF")
      (footprint "eagle-import:C0402")
      (libsource (lib "eagle-import") (part "rcl_334_C-EUC0402"))
    )
    (comp (ref "C21")
      (value "100nF")
      (footprint "eagle-import:C0402")
      (libsource (lib "eagle-import") (part "rcl_334_C-EUC0402"))
    )
    (comp (ref "C22")
      (value "10nF")
      (footprint "eagle-import:C0402")
      (libsource (lib "eagle-import") (part "rcl_334_C-EUC0402"))
    )
    (comp (ref "C23")
      (value "10nF")
      (footprint "eagle-import:C0402")
      (libsource (lib "eagle-import") (part "rcl_334_C-EUC0402"))
    )
    (comp (ref "C24")
      (value "100nF")
      (footprint "eagle-import:C0402")
      (libsource (lib "eagle-import") (part "rcl_334_C-EUC0402"))
    )
    (comp (ref "C25")
      (value "100nF")
      (footprint "eagle-import:C0402")
      (libsource (lib "eagle-import") (part "rcl_334_C-EUC0402"))
    )
    (comp (ref "C26")
      (value "10uF")
      (footprint "eagle-import:C0603")
      (libsource (lib "eagle-import") (part "rcl_334_C-EUC0603"))
    )
    (comp (ref "C27")
      (value "10uF")
      (footprint "eagle-import:C0603")
      (libsource (lib "eagle-import") (part "rcl_334_C-EUC0603"))
    )
    (comp (ref "C28")
      (value "10u")
      (footprint "eagle-import:B_3528-21W")
      (libsource (lib "eagle-import") (part "CPOL-EUB/3528-21W"))
    )
    (comp (ref "C29")
      (value "100nF")
      (footprint "eagle-import:C0402")
      (libsource (lib "eagle-import") (part "rcl_334_C-EUC0402"))
    )
    (comp (ref "C30")
      (value "100nF")
      (footprint "eagle-import:C0402")
      (libsource (lib "eagle-import") (part "rcl_334_C-EUC0402"))
    )
    (comp (ref "C31")
      (value "100nF")
      (footprint "eagle-import:C0402")
      (libsource (lib "eagle-import") (part "rcl_334_C-EUC0402"))
    )
    (comp (ref "C32")
      (value "100nF")
      (footprint "eagle-import:C0402")
      (libsource (lib "eagle-import") (part "rcl_334_C-EUC0402"))
    )
    (comp (ref "C33")
      (value "47u")
      (footprint "eagle-import:C_6032-28W")
      (libsource (lib "eagle-import") (part "CPOL-EUC/6032-28W"))
    )
    (comp (ref "GND")
      (value "TP")
      (footprint "eagle-import:TP_1")
      (libsource (lib "eagle-import") (part "TP"))
    )
    (comp (ref "IC4")
      (value "LP5907MFX-3.3")
      (footprint "eagle-import:TSOT23-5")
      (libsource (lib "eagle-import") (part "TLV700XX"))
    )
    (comp (ref "IC5")
      (value "LP5907MFX-3.3")
      (footprint "eagle-import:TSOT23-5")
      (libsource (lib "eagle-import") (part "TLV700XX"))
    )
    (comp (ref "IC6")
      (value "AD1955")
      (footprint "eagle-import:SSOP28")
      (libsource (lib "eagle-import") (part "AD1955"))
    )
    (comp (ref "L5")
      (value "600@100M")
      (footprint "eagle-import:R0805")
      (libsource (lib "eagle-import") (part "rcl_334_R-EU_R0805"))
    )
    (comp (ref "L6")
      (value "600@100M")
      (footprint "eagle-import:R0805")
      (libsource (lib "eagle-import") (part "rcl_334_R-EU_R0805"))
    )
    (comp (ref "L7")
      (value "600@100M")
      (footprint "eagle-import:R0805")
      (libsource (lib "eagle-import") (part "rcl_334_R-EU_R0805"))
    )
    (comp (ref "L8")
      (value "600@100M")
      (footprint "eagle-import:R0805")
      (libsource (lib "eagle-import") (part "rcl_334_R-EU_R0805"))
    )
    (comp (ref "R18")
      (value "2.49k")
      (footprint "eagle-import:R0402")
      (libsource (lib "eagle-import") (part "rcl_334_R-EU_R0402"))
    )
    (comp (ref "R20")
      (value "100k")
      (footprint "eagle-import:R0402")
      (libsource (lib "eagle-import") (part "rcl_334_R-EU_R0402"))
    )
  )
  (nets
    (net (code "1") (name "+5V") (class "Default")
      (node (ref "X1") (pin "P4") (pinfunction "4_P4") (pintype "passive"))
    )
    (net (code "2") (name "+12V") (class "Default")
      (node (ref "C3") (pin "2") (pinfunction "2_2") (pintype "passive"))
      (node (ref "C36") (pin "1") (pinfunction "1_1") (pintype "passive"))
      (node (ref "C37") (pin "2") (pinfunction "2_2") (pintype "passive"))
      (node (ref "C41") (pin "1") (pinfunction "1_1") (pintype "passive"))
      (node (ref "C46") (pin "1") (pinfunction "1_1") (pintype "passive"))
      (node (ref "C49") (pin "1") (pinfunction "1_1") (pintype "passive"))
      (node (ref "C5") (pin "1") (pinfunction "1_1") (pintype "passive"))
      (node (ref "C52") (pin "1") (pinfunction "1_1") (pintype "passive"))
      (node (ref "C55") (pin "1") (pinfunction "1_1") (pintype "passive"))
      (node (ref "C58") (pin "1") (pinfunction "1_1") (pintype "passive"))
      (node (ref "C60") (pin "1") (pinfunction "1_1") (pintype "passive"))
      (node (ref "C61") (pin "2") (pinfunction "2_2") (pintype "passive"))
      (node (ref "C65") (pin "1") (pinfunction "1_1") (pintype "passive"))
      (node (ref "C69") (pin "1") (pinfunction "1_1") (pintype "passive"))
      (node (ref "C73") (pin "1") (pinfunction "1_1") (pintype "passive"))
      (node (ref "C76") (pin "1") (pinfunction "1_1") (pintype "passive"))
      (node (ref "C79") (pin "1") (pinfunction "1_1") (pintype "passive"))
      (node (ref "C82") (pin "1") (pinfunction "1_1") (pintype "passive"))
      (node (ref "IC1") (pin "5") (pinfunction "OUT_5") (pintype "bidirectional"))
      (node (ref "IC10") (pin "7") (pinfunction "V+_7") (pintype "power_in"))
      (node (ref "IC11") (pin "7") (pinfunction "V+_7") (pintype "power_in"))
      (node (ref "IC12") (pin "7") (pinfunction "V+_7") (pintype "power_in"))
      (node (ref "IC7") (pin "7") (pinfunction "V+_7") (pintype "power_in"))
      (node (ref "IC8") (pin "7") (pinfunction "V+_7") (pintype "power_in"))
      (node (ref "IC9") (pin "7") (pinfunction "V+_7") (pintype "power_in"))
      (node (ref "R1") (pin "1") (pinfunction "1_1") (pintype "passive"))
      (node (ref "R2") (pin "1") (pinfunction "1_1") (pintype "passive"))
      (node (ref "R23") (pin "2") (pinfunction "2_2") (pintype "passive"))
      (node (ref "R26") (pin "2") (pinfunction "2_2") (pintype "passive"))
      (node (ref "R39") (pin "2") (pinfunction "2_2") (pintype "passive"))
      (node (ref "R42") (pin "2") (pinfunction "2_2") (pintype "passive"))
    )
    (net (code "3") (name "+15V") (class "Default")
      (node (ref "C1") (pin "1") (pinfunction "1_1") (pintype "passive"))
      (node (ref "C4") (pin "1") (pinfunction "1_1") (pintype "passive"))
      (node (ref "IC1") (pin "1") (pinfunction "IN_1") (pintype "bidirectional"))
      (node (ref "L1") (pin "1") (pinfunction "1_1") (pintype "passive"))
      (node (ref "R5") (pin "2") (pinfunction "2_2") (pintype "passive"))
      (node (ref "R6") (pin "2") (pinfunction "2_2") (pintype "passive"))
    )
    (net (code "4") (name "-12V") (class "Default")
      (node (ref "C15") (pin "2") (pinfunction "2_2") (pintype "passive"))
      (node (ref "C16") (pin "1") (pinfunction "1_1") (pintype "passive"))
      (node (ref "C42") (pin "2") (pinfunction "2_2") (pintype "passive"))
      (node (ref "C45") (pin "2") (pinfunction "2_2") (pintype "passive"))
      (node (ref "C50") (pin "2") (pinfunction "2_2") (pintype "passive"))
      (node (ref "C53") (pin "2") (pinfunction "2_2") (pintype "passive"))
      (node (ref "C56") (pin "2") (pinfunction "2_2") (pintype "passive"))
      (node (ref "C59") (pin "2") (pinfunction "2_2") (pintype "passive"))
      (node (ref "C66") (pin "2") (pinfunction "2_2") (pintype "passive"))
      (node (ref "C70") (pin "2") (pinfunction "2_2") (pintype "passive"))
      (node (ref "C74") (pin "2") (pinfunction "2_2") (pintype "passive"))
      (node (ref "C77") (pin "2") (pinfunction "2_2") (pintype "passive"))
      (node (ref "C80") (pin "2") (pinfunction "2_2") (pintype "passive"))
      (node (ref "C83") (pin "2") (pinfunction "2_2") (pintype "passive"))
      (node (ref "IC10") (pin "4") (pinfunction "V-_4") (pintype "power_in"))
      (node (ref "IC11") (pin "4") (pinfunction "V-_4") (pintype "power_in"))
      (node (ref "IC12") (pin "4") (pinfunction "V-_4") (pintype "power_in"))
      (node (ref "IC3") (pin "5") (pinfunction "OUT_5") (pintype "bidirectional"))
      (node (ref "IC7") (pin "4") (pinfunction "V-_4") (pintype "power_in"))
      (node (ref "IC8") (pin "4") (pinfunction "V-_4") (pintype "power_in"))
      (node (ref "IC9") (pin "4") (pinfunction "V-_4") (pintype "power_in"))
      (node (ref "R11") (pin "1") (pinfunction "1_1") (pintype "passive"))
      (node (ref "R14") (pin "1") (pinfunction "1_1") (pintype "passive"))
    )
    (net (code "5") (name "-15V") (class "Default")
      (node (ref "C17") (pin "1") (pinfunction "1_1") (pintype "passive"))
      (node (ref "C9") (pin "1") (pinfunction "1_1") (pintype "passive"))
      (node (ref "IC3") (pin "2") (pinfunction "IN_2") (pintype "bidirectional"))
      (node (ref "L4") (pin "2") (pinfunction "2_2") (pintype "passive"))
      (node (ref "R12") (pin "1") (pinfunction "1_1") (pintype "passive"))
      (node (ref "R17") (pin "1") (pinfunction "1_1") (pintype "passive"))
    )
    (net (code "6") (name "A5V0") (class "Default")
      (node (ref "C18") (pin "2") (pinfunction "2_2") (pintype "passive"))
      (node (ref "C20") (pin "2") (pinfunction "2_2") (pintype "passive"))
      (node (ref "IC4") (pin "5") (pinfunction "OUT_5") (pintype "bidirectional"))
      (node (ref "L8") (pin "1") (pinfunction "1_1") (pintype "passive"))
      (node (ref "R21") (pin "2") (pinfunction "2_2") (pintype "passive"))
    )
    (net (code "7") (name "ADC0") (class "Default")
      (node (ref "C144") (pin "2") (pinfunction "2_2") (pintype "passive"))
      (node (ref "R60") (pin "1") (pinfunction "1_1") (pintype "passive"))
      (node (ref "R62") (pin "1") (pinfunction "1_1") (pintype "passive"))
      (node (ref "R81") (pin "2") (pinfunction "2_2") (pintype "passive"))
    )
    (net (code "8") (name "ADC0_EZ") (class "Default")
      (node (ref "C141") (pin "1") (pinfunction "1_1") (pintype "passive"))
      (node (ref "IC16") (pin "41") (pinfunction "EBIA11/AN7/ERXD0/AECRS/PMA11/RB12_41") (pintype "bidirectional"))
      (node (ref "R60") (pin "2") (pinfunction "2_2") (pintype "passive"))
    )
    (net (code "9") (name "ADC0_IN") (class "Default")
      (node (ref "R83") (pin "2") (pinfunction "2_2") (pintype "passive"))
      (node (ref "X1") (pin "P2") (pinfunction "2_P2") (pintype "passive"))
    )
    (net (code "10") (name "ADC1") (class "Default")
      (node (ref "C145") (pin "2") (pinfunction "2_2") (pintype "passive"))
      (node (ref "R19") (pin "1") (pinfunction "1_1") (pintype "passive"))
      (node (ref "R71") (pin "1") (pinfunction "1_1") (pintype "passive"))
      (node (ref "R82") (pin "2") (pinfunction "2_2") (pintype "passive"))
    )
    (net (code "11") (name "ADC1_EZ") (class "Default")
      (node (ref "C142") (pin "1") (pinfunction "1_1") (pintype "passive"))
      (node (ref "IC16") (pin "42") (pinfunction "AN8/ERXD1/AECOL/RB13_42") (pintype "bidirectional"))
      (node (ref "R71") (pin "2") (pinfunction "2_2") (pintype "passive"))
    )
    (net (code "12") (name "ADC1_IN") (class "Default")
      (node (ref "R85") (pin "2") (pinfunction "2_2") (pintype "passive"))
      (node (ref "X1") (pin "P1") (pinfunction "1_P1") (pintype "passive"))
    )
    (net (code "13") (name "ALE") (class "Default")
      (node (ref "IC13") (pin "P17") (pinfunction "ALE_P17") (pintype "bidirectional"))
      (node (ref "IC16") (pin "11") (pinfunction "EBIA4/AN13/C1INC/ECRS/RPG7/SDA4/PMA4..._11") (pintype "bidirectional"))
    )
    (net (code "14") (name "AUDIO") (class "Default")
      (node (ref "IC16") (pin "86") (pinfunction "EBID10/ETXD0/RPF1/PMD10/RF1_86") (pintype "bidirectional"))
      (node (ref "R76") (pin "2") (pinfunction "2_2") (pintype "passive"))
    )
    (net (code "15") (name "BUSY") (class "Default")
      (node (ref "IC13") (pin "P7") (pinfunction "R/B#_P7") (pintype "bidirectional"))
      (node (ref "IC16") (pin "16") (pinfunction "EBIA2/AN11/C2INC/ERXCLK/EREFCLK..._16") (pintype "bidirectional"))
      (node (ref "R80") (pin "1") (pinfunction "1_1") (pintype "passive"))
    )
    (net (code "16") (name "CE") (class "Default")
      (node (ref "IC13") (pin "P9") (pinfunction "CE#_P9") (pintype "bidirectional"))
      (node (ref "IC16") (pin "79") (pinfunction "EBID12/ETXD2/RPD12..._79") (pintype "bidirectional"))
    )
    (net (code "17") (name "CLE") (class "Default")
      (node (ref "IC13") (pin "P16") (pinfunction "CLE_P16") (pintype "bidirectional"))
      (node (ref "IC16") (pin "80") (pinfunction "EBID13/ETXD3/PMD13/RD13_80") (pintype "bidirectional"))
    )
    (net (code "18") (name "CLK_IN") (class "Default")
      (node (ref "CLKIN") (pin "4") (pinfunction "4_4") (pintype "passive"))
      (node (ref "IC22") (pin "2") (pinfunction "P$2_2") (pintype "bidirectional"))
    )
    (net (code "19") (name "CLK_SYNC") (class "Default")
      (node (ref "IC22") (pin "4") (pinfunction "P$4_4") (pintype "bidirectional"))
      (node (ref "IC25") (pin "12") (pinfunction "PC2/OC0C/RXD0_12") (pintype "bidirectional"))
    )
    (net (code "20") (name "CTS") (class "Default")
      (node (ref "IC21") (pin "11") (pinfunction "B4_11") (pintype "bidirectional"))
      (node (ref "IC25") (pin "29") (pinfunction "~XCK0OC0BSCLPE1_29") (pintype "bidirectional"))
    )
    (net (code "21") (name "D+") (class "Default")
      (node (ref "IC15") (pin "P$4") (pinfunction "IO2_P$4") (pintype "bidirectional"))
      (node (ref "IC16") (pin "55") (pinfunction "D+_55") (pintype "bidirectional"))
    )
    (net (code "22") (name "D-") (class "Default")
      (node (ref "IC15") (pin "P$6") (pinfunction "IO1_P$6") (pintype "bidirectional"))
      (node (ref "IC16") (pin "54") (pinfunction "D-_54") (pintype "bidirectional"))
    )
    (net (code "23") (name "D5V") (class "Default")
      (node (ref "C115") (pin "1") (pinfunction "1_1") (pintype "passive"))
      (node (ref "C85") (pin "1") (pinfunction "1_1") (pintype "passive"))
      (node (ref "C87") (pin "1") (pinfunction "1_1") (pintype "passive"))
      (node (ref "IC14") (pin "P$2") (pinfunction "OUT_P$2") (pintype "bidirectional"))
      (node (ref "IC18") (pin "1") (pinfunction "IN_1") (pintype "bidirectional"))
      (node (ref "IC18") (pin "3") (pinfunction "EN_3") (pintype "bidirectional"))
      (node (ref "IC20") (pin "1") (pinfunction "IN_1") (pintype "bidirectional"))
      (node (ref "IC20") (pin "3") (pinfunction "EN_3") (pintype "bidirectional"))
      (node (ref "JP2") (pin "1") (pinfunction "1_1") (pintype "passive"))
      (node (ref "R74") (pin "2") (pinfunction "2_2") (pintype "passive"))
    )
    (net (code "24") (name "D5V0") (class "Default")
      (node (ref "C19") (pin "2") (pinfunction "2_2") (pintype "passive"))
      (node (ref "C21") (pin "2") (pinfunction "2_2") (pintype "passive"))
      (node (ref "IC5") (pin "5") (pinfunction "OUT_5") (pintype "bidirectional"))
      (node (ref "L7") (pin "1") (pinfunction "1_1") (pintype "passive"))
    )
    (net (code "25") (name "DAC_~{RST}") (class "Default")
      (node (ref "IC16") (pin "65") (pinfunction "EBIA8/RPF5/SCL5/PMA8/RF5_65") (pintype "bidirectional"))
      (node (ref "IC6") (pin "P23") (pinfunction "~{PD/RST}_P23") (pintype "bidirectional"))
      (node (ref "R20") (pin "1") (pinfunction "1_1") (pintype "passive"))
    )
    (net (code "26") (name "EN_DCDC") (class "Default")
      (node (ref "IC2") (pin "11") (pinfunction "EN2_11") (pintype "bidirectional"))
      (node (ref "IC2") (pin "9") (pinfunction "EN1_9") (pintype "bidirectional"))
      (node (ref "IC25") (pin "24") (pinfunction "~{#SSPD4}_24") (pintype "bidirectional"))
      (node (ref "R9") (pin "1") (pinfunction "1_1") (pintype "passive"))
    )
    (net (code "27") (name "EN_N12V") (class "Default")
      (node (ref "IC16") (pin "77") (pinfunction "EBID14/ETXEN/RPD2..._77") (pintype "bidirectional"))
      (node (ref "R88") (pin "1") (pinfunction "1_1") (pintype "passive"))
    )
    (net (code "28") (name "EN_P12V") (class "Default")
      (node (ref "IC16") (pin "76") (pinfunction "RPD1/SCK1/RD1_76") (pintype "bidirectional"))
      (node (ref "R87") (pin "1") (pinfunction "1_1") (pintype "passive"))
    )
    (net (code "29") (name "FILTB") (class "Default")
      (node (ref "C28") (pin "+") (pinfunction "+_+") (pintype "passive"))
      (node (ref "C32") (pin "1") (pinfunction "1_1") (pintype "passive"))
      (node (ref "IC6") (pin "P16") (pinfunction "FILTB_P16") (pintype "bidirectional"))
    )
    (net (code "30") (name "FT_CTS") (class "Default")
      (node (ref "IC19") (pin "11") (pinfunction "~{CTS}_11") (pintype "input"))
      (node (ref "IC21") (pin "6") (pinfunction "A4_6") (pintype "bidirectional"))
    )
    (net (code "31") (name "FT_RTS") (class "Default")
      (node (ref "IC19") (pin "3") (pinfunction "~{RTS}_3") (pintype "output"))
      (node (ref "IC21") (pin "4") (pinfunction "A2_4") (pintype "bidirectional"))
    )
    (net (code "32") (name "FT_RXD") (class "Default")
      (node (ref "IC19") (pin "5") (pinfunction "RXD_5") (pintype "input"))
      (node (ref "IC21") (pin "5") (pinfunction "A3_5") (pintype "bidirectional"))
    )
    (net (code "33") (name "FT_TXD") (class "Default")
      (node (ref "IC19") (pin "1") (pinfunction "TXD_1") (pintype "output"))
      (node (ref "IC21") (pin "3") (pinfunction "A1_3") (pintype "bidirectional"))
    )
    (net (code "34") (name "GND") (class "Default")
      (node (ref "C1") (pin "2") (pinfunction "2_2") (pintype "passive"))
      (node (ref "C10") (pin "2") (pinfunction "2_2") (pintype "passive"))
      (node (ref "C100") (pin "2") (pinfunction "2_2") (pintype "passive"))
      (node (ref "C101") (pin "2") (pinfunction "2_2") (pintype "passive"))
      (node (ref "C102") (pin "2") (pinfunction "2_2") (pintype "passive"))
      (node (ref "C104") (pin "2") (pinfunction "2_2") (pintype "passive"))
      (node (ref "C105") (pin "2") (pinfunction "2_2") (pintype "passive"))
      (node (ref "C11") (pin "2") (pinfunction "2_2") (pintype "passive"))
      (node (ref "C115") (pin "2") (pinfunction "2_2") (pintype "passive"))
      (node (ref "C116") (pin "2") (pinfunction "2_2") (pintype "passive"))
      (node (ref "C118") (pin "2") (pinfunction "2_2") (pintype "passive"))
      (node (ref "C119") (pin "2") (pinfunction "2_2") (pintype "passive"))
      (node (ref "C12") (pin "2") (pinfunction "2_2") (pintype "passive"))
      (node (ref "C120") (pin "2") (pinfunction "2_2") (pintype "passive"))
      (node (ref "C121") (pin "2") (pinfunction "2_2") (pintype "passive"))
      (node (ref "C122") (pin "2") (pinfunction "2_2") (pintype "passive"))
      (node (ref "C123") (pin "2") (pinfunction "2_2") (pintype "passive"))
      (node (ref "C126") (pin "2") (pinfunction "2_2") (pintype "passive"))
      (node (ref "C127") (pin "2") (pinfunction "2_2") (pintype "passive"))
      (node (ref "C128") (pin "2") (pinfunction "2_2") (pintype "passive"))
      (node (ref "C13") (pin "2") (pinfunction "2_2") (pintype "passive"))
      (node (ref "C130") (pin "2") (pinfunction "2_2") (pintype "passive"))
      (node (ref "C131") (pin "2") (pinfunction "2_2") (pintype "passive"))
      (node (ref "C132") (pin "2") (pinfunction "2_2") (pintype "passive"))
      (node (ref "C133") (pin "2") (pinfunction "2_2") (pintype "passive"))
      (node (ref "C134") (pin "2") (pinfunction "2_2") (pintype "passive"))
      (node (ref "C135") (pin "2") (pinfunction "2_2") (pintype "passive"))
      (node (ref "C136") (pin "2") (pinfunction "2_2") (pintype "passive"))
      (node (ref "C137") (pin "2") (pinfunction "2_2") (pintype "passive"))
      (node (ref "C138") (pin "2") (pinfunction "2_2") (pintype "passive"))
      (node (ref "C139") (pin "2") (pinfunction "2_2") (pintype "passive"))
      (node (ref "C14") (pin "2") (pinfunction "2_2") (pintype "passive"))
      (node (ref "C140") (pin "2") (pinfunction "2_2") (pintype "passive"))
      (node (ref "C141") (pin "2") (pinfunction "2_2") (pintype "passive"))
      (node (ref "C142") (pin "2") (pinfunction "2_2") (pintype "passive"))
      (node (ref "C143") (pin "2") (pinfunction "2_2") (pintype "passive"))
      (node (ref "C144") (pin "1") (pinfunction "1_1") (pintype "passive"))
      (node (ref "C145") (pin "1") (pinfunction "1_1") (pintype "passive"))
      (node (ref "C146") (pin "2") (pinfunction "2_2") (pintype "passive"))
      (node (ref "C147") (pin "2") (pinfunction "2_2") (pintype "passive"))
      (node (ref "C148") (pin "2") (pinfunction "2_2") (pintype "passive"))
      (node (ref "C149") (pin "2") (pinfunction "2_2") (pintype "passive"))
      (node (ref "C16") (pin "2") (pinfunction "2_2") (pintype "passive"))
      (node (ref "C17") (pin "2") (pinfunction "2_2") (pintype "passive"))
      (node (ref "C18") (pin "1") (pinfunction "1_1") (pintype "passive"))
      (node (ref "C19") (pin "1") (pinfunction "1_1") (pintype "passive"))
      (node (ref "C2") (pin "-") (pinfunction "-_-") (pintype "passive"))
      (node (ref "C20") (pin "1") (pinfunction "1_1") (pintype "passive"))
      (node (ref "C21") (pin "1") (pinfunction "1_1") (pintype "passive"))
      (node (ref "C22") (pin "1") (pinfunction "1_1") (pintype "passive"))
      (node (ref "C23") (pin "1") (pinfunction "1_1") (pintype "passive"))
      (node (ref "C24") (pin "1") (pinfunction "1_1") (pintype "passive"))
      (node (ref "C25") (pin "1") (pinfunction "1_1") (pintype "passive"))
      (node (ref "C26") (pin "1") (pinfunction "1_1") (pintype "passive"))
      (node (ref "C27") (pin "1") (pinfunction "1_1") (pintype "passive"))
      (node (ref "C28") (pin "-") (pinfunction "-_-") (pintype "passive"))
      (node (ref "C29") (pin "2") (pinfunction "2_2") (pintype "passive"))
      (node (ref "C30") (pin "2") (pinfunction "2_2") (pintype "passive"))
      (node (ref "C31") (pin "2") (pinfunction "2_2") (pintype "passive"))
      (node (ref "C32") (pin "2") (pinfunction "2_2") (pintype "passive"))
      (node (ref "C33") (pin "-") (pinfunction "-_-") (pintype "passive"))
      (node (ref "C34") (pin "2") (pinfunction "2_2") (pintype "passive"))
      (node (ref "C35") (pin "-") (pinfunction "-_-") (pintype "passive"))
      (node (ref "C36") (pin "2") (pinfunction "2_2") (pintype "passive"))
      (node (ref "C37") (pin "1") (pinfunction "1_1") (pintype "passive"))
      (node (ref "C39") (pin "2") (pinfunction "2_2") (pintype "passive"))
      (node (ref "C4") (pin "2") (pinfunction "2_2") (pintype "passive"))
      (node (ref "C40") (pin "2") (pinfunction "2_2") (pintype "passive"))
      (node (ref "C41") (pin "2") (pinfunction "2_2") (pintype "passive"))
      (node (ref "C42") (pin "1") (pinfunction "1_1") (pintype "passive"))
      (node (ref "C45") (pin "1") (pinfunction "1_1") (pintype "passive"))
      (node (ref "C46") (pin "2") (pinfunction "2_2") (pintype "passive"))
      (node (ref "C47") (pin "2") (pinfunction "2_2") (pintype "passive"))
      (node (ref "C48") (pin "2") (pinfunction "2_2") (pintype "passive"))
      (node (ref "C49") (pin "2") (pinfunction "2_2") (pintype "passive"))
      (node (ref "C5") (pin "2") (pinfunction "2_2") (pintype "passive"))
      (node (ref "C50") (pin "1") (pinfunction "1_1") (pintype "passive"))
      (node (ref "C51") (pin "2") (pinfunction "2_2") (pintype "passive"))
      (node (ref "C52") (pin "2") (pinfunction "2_2") (pintype "passive"))
      (node (ref "C53") (pin "1") (pinfunction "1_1") (pintype "passive"))
      (node (ref "C55") (pin "2") (pinfunction "2_2") (pintype "passive"))
      (node (ref "C56") (pin "1") (pinfunction "1_1") (pintype "passive"))
      (node (ref "C57") (pin "2") (pinfunction "2_2") (pintype "passive"))
      (node (ref "C58") (pin "2") (pinfunction "2_2") (pintype "passive"))
      (node (ref "C59") (pin "1") (pinfunction "1_1") (pintype "passive"))
      (node (ref "C6") (pin "2") (pinfunction "2_2") (pintype "passive"))
      (node (ref "C60") (pin "2") (pinfunction "2_2") (pintype "passive"))
      (node (ref "C61") (pin "1") (pinfunction "1_1") (pintype "passive"))
      (node (ref "C63") (pin "2") (pinfunction "2_2") (pintype "passive"))
      (node (ref "C64") (pin "2") (pinfunction "2_2") (pintype "passive"))
      (node (ref "C65") (pin "2") (pinfunction "2_2") (pintype "passive"))
      (node (ref "C66") (pin "1") (pinfunction "1_1") (pintype "passive"))
      (node (ref "C69") (pin "2") (pinfunction "2_2") (pintype "passive"))
      (node (ref "C7") (pin "2") (pinfunction "2_2") (pintype "passive"))
      (node (ref "C70") (pin "1") (pinfunction "1_1") (pintype "passive"))
      (node (ref "C71") (pin "2") (pinfunction "2_2") (pintype "passive"))
      (node (ref "C72") (pin "2") (pinfunction "2_2") (pintype "passive"))
      (node (ref "C73") (pin "2") (pinfunction "2_2") (pintype "passive"))
      (node (ref "C74") (pin "1") (pinfunction "1_1") (pintype "passive"))
      (node (ref "C75") (pin "2") (pinfunction "2_2") (pintype "passive"))
      (node (ref "C76") (pin "2") (pinfunction "2_2") (pintype "passive"))
      (node (ref "C77") (pin "1") (pinfunction "1_1") (pintype "passive"))
      (node (ref "C79") (pin "2") (pinfunction "2_2") (pintype "passive"))
      (node (ref "C8") (pin "2") (pinfunction "2_2") (pintype "passive"))
      (node (ref "C80") (pin "1") (pinfunction "1_1") (pintype "passive"))
      (node (ref "C81") (pin "2") (pinfunction "2_2") (pintype "passive"))
      (node (ref "C82") (pin "2") (pinfunction "2_2") (pintype "passive"))
      (node (ref "C83") (pin "1") (pinfunction "1_1") (pintype "passive"))
      (node (ref "C84") (pin "2") (pinfunction "2_2") (pintype "passive"))
      (node (ref "C85") (pin "2") (pinfunction "2_2") (pintype "passive"))
      (node (ref "C86") (pin "2") (pinfunction "2_2") (pintype "passive"))
      (node (ref "C87") (pin "2") (pinfunction "2_2") (pintype "passive"))
      (node (ref "C88") (pin "2") (pinfunction "2_2") (pintype "passive"))
      (node (ref "C89") (pin "2") (pinfunction "2_2") (pintype "passive"))
      (node (ref "C9") (pin "2") (pinfunction "2_2") (pintype "passive"))
      (node (ref "C90") (pin "1") (pinfunction "1_1") (pintype "passive"))
      (node (ref "C91") (pin "1") (pinfunction "1_1") (pintype "passive"))
      (node (ref "C92") (pin "2") (pinfunction "2_2") (pintype "passive"))
      (node (ref "C93") (pin "2") (pinfunction "2_2") (pintype "passive"))
      (node (ref "C94") (pin "2") (pinfunction "2_2") (pintype "passive"))
      (node (ref "C95") (pin "2") (pinfunction "2_2") (pintype "passive"))
      (node (ref "C96") (pin "2") (pinfunction "2_2") (pintype "passive"))
      (node (ref "C97") (pin "2") (pinfunction "2_2") (pintype "passive"))
      (node (ref "C98") (pin "2") (pinfunction "2_2") (pintype "passive"))
      (node (ref "C99") (pin "2") (pinfunction "2_2") (pintype "passive"))
      (node (ref "CLKIN") (pin "5") (pinfunction "5_5") (pintype "passive"))
      (node (ref "CUSB1") (pin "2") (pinfunction "2_2") (pintype "passive"))
      (node (ref "GND") (pin "TP") (pinfunction "TP_TP") (pintype "input"))
      (node (ref "GND174") (pin "TP") (pinfunction "TP_TP") (pintype "input"))
      (node (ref "GND176") (pin "TP") (pinfunction "TP_TP") (pintype "input"))
      (node (ref "GND26") (pin "TP") (pinfunction "TP_TP") (pintype "input"))
      (node (ref "IC1") (pin "2") (pinfunction "GND_2") (pintype "bidirectional"))
      (node (ref "IC13") (pin "P13") (pinfunction "VSS_P13") (pintype "bidirectional"))
      (node (ref "IC13") (pin "P25") (pinfunction "VSS_P25") (pintype "bidirectional"))
      (node (ref "IC13") (pin "P36") (pinfunction "VSS_P36") (pintype "bidirectional"))
      (node (ref "IC13") (pin "P48") (pinfunction "VSS_P48") (pintype "bidirectional"))
      (node (ref "IC14") (pin "P$3") (pinfunction "GND_P$3") (pintype "bidirectional"))
      (node (ref "IC14") (pin "P$6") (pinfunction "GND_T_P$6") (pintype "bidirectional"))
      (node (ref "IC15") (pin "P$2") (pinfunction "GND_P$2") (pintype "bidirectional"))
      (node (ref "IC16") (pin "13") (pinfunction "VSS_13") (pintype "input"))
      (node (ref "IC16") (pin "31") (pinfunction "AVSS_31") (pintype "bidirectional"))
      (node (ref "IC16") (pin "36") (pinfunction "VSS_36") (pintype "bidirectional"))
      (node (ref "IC16") (pin "45") (pinfunction "VSS_45") (pintype "bidirectional"))
      (node (ref "IC16") (pin "53") (pinfunction "VSS_53") (pintype "bidirectional"))
      (node (ref "IC16") (pin "63") (pinfunction "VSS_63") (pintype "bidirectional"))
      (node (ref "IC16") (pin "75") (pinfunction "VSS_75") (pintype "bidirectional"))
      (node (ref "IC16") (pin "84") (pinfunction "VSS_84") (pintype "bidirectional"))
      (node (ref "IC16") (pin "92") (pinfunction "VSS_92") (pintype "input"))
      (node (ref "IC18") (pin "2") (pinfunction "GND_2") (pintype "bidirectional"))
      (node (ref "IC2") (pin "1") (pinfunction "PGND_1") (pintype "bidirectional"))
      (node (ref "IC2") (pin "15") (pinfunction "AGND_15") (pintype "bidirectional"))
      (node (ref "IC2") (pin "4") (pinfunction "SYNC/FREQ_4") (pintype "bidirectional"))
      (node (ref "IC2") (pin "6") (pinfunction "SLEW_6") (pintype "bidirectional"))
      (node (ref "IC2") (pin "EPAD") (pinfunction "PGND_EPAD") (pintype "bidirectional"))
      (node (ref "IC20") (pin "2") (pinfunction "GND_2") (pintype "bidirectional"))
      (node (ref "IC21") (pin "15") (pinfunction "GND2_15") (pintype "bidirectional"))
      (node (ref "IC21") (pin "9") (pinfunction "GND2_9") (pintype "bidirectional"))
      (node (ref "IC22") (pin "1") (pinfunction "P$1_1") (pintype "bidirectional"))
      (node (ref "IC22") (pin "3") (pinfunction "P$3_3") (pintype "bidirectional"))
      (node (ref "IC23") (pin "1") (pinfunction "P$1_1") (pintype "bidirectional"))
      (node (ref "IC23") (pin "3") (pinfunction "P$3_3") (pintype "bidirectional"))
      (node (ref "IC24") (pin "1") (pinfunction "P$1_1") (pintype "bidirectional"))
      (node (ref "IC24") (pin "3") (pinfunction "P$3_3") (pintype "bidirectional"))
      (node (ref "IC25") (pin "18") (pinfunction "GND_18") (pintype "power_in"))
      (node (ref "IC25") (pin "30") (pinfunction "GND_30") (pintype "power_in"))
      (node (ref "IC25") (pin "38") (pinfunction "GND_38") (pintype "power_in"))
      (node (ref "IC25") (pin "7") (pinfunction "PB3/ADC11/DAC1_7") (pintype "bidirectional"))
      (node (ref "IC25") (pin "8") (pinfunction "GND_8") (pintype "power_in"))
      (node (ref "IC26") (pin "2") (pinfunction "V-_2") (pintype "power_in"))
      (node (ref "IC27") (pin "2") (pinfunction "V-_2") (pintype "power_in"))
      (node (ref "IC28") (pin "1") (pinfunction "P$1_1") (pintype "bidirectional"))
      (node (ref "IC28") (pin "3") (pinfunction "P$3_3") (pintype "bidirectional"))
      (node (ref "IC29") (pin "1") (pinfunction "P$1_1") (pintype "bidirectional"))
      (node (ref "IC29") (pin "3") (pinfunction "P$3_3") (pintype "bidirectional"))
      (node (ref "IC3") (pin "1") (pinfunction "GND_1") (pintype "bidirectional"))
      (node (ref "IC30") (pin "1") (pinfunction "P$1_1") (pintype "bidirectional"))
      (node (ref "IC30") (pin "3") (pinfunction "P$3_3") (pintype "bidirectional"))
      (node (ref "IC31") (pin "1") (pinfunction "P$1_1") (pintype "bidirectional"))
      (node (ref "IC31") (pin "3") (pinfunction "P$3_3") (pintype "bidirectional"))
      (node (ref "IC32") (pin "3") (pinfunction "GND_3") (pintype "bidirectional"))
      (node (ref "IC33") (pin "3") (pinfunction "GND_3") (pintype "bidirectional"))
      (node (ref "IC35") (pin "3") (pinfunction "GND_3") (pintype "bidirectional"))
      (node (ref "IC4") (pin "2") (pinfunction "GND_2") (pintype "bidirectional"))
      (node (ref "IC5") (pin "2") (pinfunction "GND_2") (pintype "bidirectional"))
      (node (ref "IC6") (pin "P10") (pinfunction "AGND_P10") (pintype "bidirectional"))
      (node (ref "IC6") (pin "P19") (pinfunction "AGND_P19") (pintype "bidirectional"))
      (node (ref "IC6") (pin "P28") (pinfunction "DGND_P28") (pintype "bidirectional"))
      (node (ref "IC6") (pin "P9") (pinfunction "DSD_PHASE_P9") (pintype "bidirectional"))
      (node (ref "J3") (pin "P1") (pinfunction "1_P1") (pintype "passive"))
      (node (ref "J4") (pin "P1") (pinfunction "1_P1") (pintype "passive"))
      (node (ref "JACK") (pin "P2") (pinfunction "2_P2") (pintype "passive"))
      (node (ref "JACK") (pin "P3") (pinfunction "3_P3") (pintype "passive"))
      (node (ref "JP1") (pin "3") (pinfunction "3_3") (pintype "passive"))
      (node (ref "L3") (pin "2") (pinfunction "2_2") (pintype "passive"))
      (node (ref "LED1") (pin "K") (pinfunction "K_K") (pintype "bidirectional"))
      (node (ref "LED2") (pin "K") (pinfunction "K_K") (pintype "bidirectional"))
      (node (ref "LED3") (pin "K") (pinfunction "K_K") (pintype "bidirectional"))
      (node (ref "OSC1") (pin "P$2") (pinfunction "GND_P$2") (pintype "passive"))
      (node (ref "OSC2") (pin "P$2") (pinfunction "GND_P$2") (pintype "passive"))
      (node (ref "OSC3") (pin "P$2") (pinfunction "GND_P$2") (pintype "passive"))
      (node (ref "PDI") (pin "6") (pinfunction "6_6") (pintype "passive"))
      (node (ref "R15") (pin "2") (pinfunction "2_2") (pintype "passive"))
      (node (ref "R18") (pin "1") (pinfunction "1_1") (pintype "passive"))
      (node (ref "R20") (pin "2") (pinfunction "2_2") (pintype "passive"))
      (node (ref "R22") (pin "1") (pinfunction "1_1") (pintype "passive"))
      (node (ref "R3") (pin "2") (pinfunction "2_2") (pintype "passive"))
      (node (ref "R34") (pin "1") (pinfunction "1_1") (pintype "passive"))
      (node (ref "R50") (pin "1") (pinfunction "1_1") (pintype "passive"))
      (node (ref "R55") (pin "1") (pinfunction "1_1") (pintype "passive"))
      (node (ref "R61") (pin "2") (pinfunction "2_2") (pintype "passive"))
      (node (ref "R67") (pin "2") (pinfunction "2_2") (pintype "passive"))
      (node (ref "R68") (pin "2") (pinfunction "2_2") (pintype "passive"))
      (node (ref "R7") (pin "2") (pinfunction "2_2") (pintype "passive"))
      (node (ref "R78") (pin "2") (pinfunction "2_2") (pintype "passive"))
      (node (ref "R79") (pin "2") (pinfunction "2_2") (pintype "passive"))
      (node (ref "R84") (pin "1") (pinfunction "1_1") (pintype "passive"))
      (node (ref "R86") (pin "1") (pinfunction "1_1") (pintype "passive"))
      (node (ref "R89") (pin "2") (pinfunction "2_2") (pintype "passive"))
      (node (ref "RUSB1") (pin "2") (pinfunction "2_2") (pintype "passive"))
      (node (ref "STATE") (pin "K") (pinfunction "K_K") (pintype "bidirectional"))
      (node (ref "SW1") (pin "P") (pinfunction "P_P") (pintype "passive"))
      (node (ref "USB1") (pin "P$5") (pinfunction "5_P$5") (pintype "bidirectional"))
      (node (ref "X1") (pin "P12") (pinfunction "12_P12") (pintype "passive"))
      (node (ref "X1") (pin "P3") (pinfunction "3_P3") (pintype "passive"))
      (node (ref "X1") (pin "P8") (pinfunction "8_P8") (pintype "passive"))
    )
    (net (code "35") (name "GND2") (class "Default")
      (node (ref "C106") (pin "2") (pinfunction "2_2") (pintype "passive"))
      (node (ref "C107") (pin "2") (pinfunction "2_2") (pintype "passive"))
      (node (ref "C108") (pin "2") (pinfunction "2_2") (pintype "passive"))
      (node (ref "C111") (pin "2") (pinfunction "2_2") (pintype "passive"))
      (node (ref "C112") (pin "-") (pinfunction "-_-") (pintype "passive"))
      (node (ref "C113") (pin "2") (pinfunction "2_2") (pintype "passive"))
      (node (ref "C114") (pin "2") (pinfunction "2_2") (pintype "passive"))
      (node (ref "C117") (pin "2") (pinfunction "2_2") (pintype "passive"))
      (node (ref "CUSB2") (pin "2") (pinfunction "2_2") (pintype "passive"))
      (node (ref "IC17") (pin "P$2") (pinfunction "GND_P$2") (pintype "bidirectional"))
      (node (ref "IC19") (pin "18") (pinfunction "GND_18") (pintype "power_in"))
      (node (ref "IC19") (pin "21") (pinfunction "GND_21") (pintype "power_in"))
      (node (ref "IC19") (pin "25") (pinfunction "GND_25") (pintype "power_in"))
      (node (ref "IC19") (pin "26") (pinfunction "TEST_26") (pintype "input"))
      (node (ref "IC19") (pin "7") (pinfunction "GND_7") (pintype "power_in"))
      (node (ref "IC21") (pin "2") (pinfunction "GND1_2") (pintype "bidirectional"))
      (node (ref "IC21") (pin "8") (pinfunction "GND1_8") (pintype "bidirectional"))
      (node (ref "RUSB2") (pin "2") (pinfunction "2_2") (pintype "passive"))
      (node (ref "USB2") (pin "P$5") (pinfunction "5_P$5") (pintype "bidirectional"))
    )
    (net (code "36") (name "IN0") (class "Default")
      (node (ref "IC24") (pin "2") (pinfunction "P$2_2") (pintype "bidirectional"))
      (node (ref "R61") (pin "1") (pinfunction "1_1") (pintype "passive"))
      (node (ref "X1") (pin "P11") (pinfunction "11_P11") (pintype "passive"))
    )
    (net (code "37") (name "IN00{slash}TRIG") (class "Default")
      (node (ref "IC16") (pin "71") (pinfunction "EMDIO/AEMDIO/RPD0/RTCC/INT0/RD0_71") (pintype "bidirectional"))
      (node (ref "IC16") (pin "81") (pinfunction "~{SQICS0}/RPD4/RD4_81") (pintype "bidirectional"))
      (node (ref "IC24") (pin "4") (pinfunction "P$4_4") (pintype "bidirectional"))
      (node (ref "IC25") (pin "4") (pinfunction "PB0/ADC8/AREF_4") (pintype "bidirectional"))
    )
    (net (code "38") (name "IN1") (class "Default")
      (node (ref "IC30") (pin "2") (pinfunction "P$2_2") (pintype "bidirectional"))
      (node (ref "R67") (pin "1") (pinfunction "1_1") (pintype "passive"))
      (node (ref "X1") (pin "P10") (pinfunction "10_P10") (pintype "passive"))
    )
    (net (code "39") (name "IN01") (class "Default")
      (node (ref "IC25") (pin "20") (pinfunction "~{OC0APD0}_20") (pintype "bidirectional"))
      (node (ref "IC30") (pin "4") (pinfunction "P$4_4") (pintype "bidirectional"))
    )
    (net (code "40") (name "IN2") (class "Default")
      (node (ref "IC31") (pin "2") (pinfunction "P$2_2") (pintype "bidirectional"))
      (node (ref "R68") (pin "1") (pinfunction "1_1") (pintype "passive"))
      (node (ref "X1") (pin "P9") (pinfunction "9_P9") (pintype "passive"))
    )
    (net (code "41") (name "IN02") (class "Default")
      (node (ref "IC25") (pin "10") (pinfunction "PC0/OC0A/SDA_10") (pintype "bidirectional"))
      (node (ref "IC31") (pin "4") (pinfunction "P$4_4") (pintype "bidirectional"))
    )
    (net (code "42") (name "IOUTL+") (class "Default")
      (node (ref "C62") (pin "1") (pinfunction "1_1") (pintype "passive"))
      (node (ref "IC10") (pin "2") (pinfunction "-IN_2") (pintype "input"))
      (node (ref "IC6") (pin "P18") (pinfunction "IOUTL+_P18") (pintype "bidirectional"))
      (node (ref "R39") (pin "1") (pinfunction "1_1") (pintype "passive"))
      (node (ref "R43") (pin "1") (pinfunction "1_1") (pintype "passive"))
      (node (ref "R45") (pin "1") (pinfunction "1_1") (pintype "passive"))
    )
    (net (code "43") (name "IOUTL-") (class "Default")
      (node (ref "C62") (pin "2") (pinfunction "2_2") (pintype "passive"))
      (node (ref "IC11") (pin "2") (pinfunction "-IN_2") (pintype "input"))
      (node (ref "IC6") (pin "P17") (pinfunction "IOUTL-_P17") (pintype "bidirectional"))
      (node (ref "R42") (pin "1") (pinfunction "1_1") (pintype "passive"))
      (node (ref "R44") (pin "1") (pinfunction "1_1") (pintype "passive"))
      (node (ref "R46") (pin "1") (pinfunction "1_1") (pintype "passive"))
    )
    (net (code "44") (name "IOUTR+") (class "Default")
      (node (ref "C38") (pin "1") (pinfunction "1_1") (pintype "passive"))
      (node (ref "IC6") (pin "P11") (pinfunction "IOUTR+_P11") (pintype "bidirectional"))
      (node (ref "IC7") (pin "2") (pinfunction "-IN_2") (pintype "input"))
      (node (ref "R23") (pin "1") (pinfunction "1_1") (pintype "passive"))
      (node (ref "R27") (pin "1") (pinfunction "1_1") (pintype "passive"))
      (node (ref "R29") (pin "1") (pinfunction "1_1") (pintype "passive"))
    )
    (net (code "45") (name "IOUTR-") (class "Default")
      (node (ref "C38") (pin "2") (pinfunction "2_2") (pintype "passive"))
      (node (ref "IC6") (pin "P12") (pinfunction "IOUTR-_P12") (pintype "bidirectional"))
      (node (ref "IC8") (pin "2") (pinfunction "-IN_2") (pintype "input"))
      (node (ref "R26") (pin "1") (pinfunction "1_1") (pintype "passive"))
      (node (ref "R28") (pin "1") (pinfunction "1_1") (pintype "passive"))
      (node (ref "R30") (pin "1") (pinfunction "1_1") (pintype "passive"))
    )
    (net (code "46") (name "MEMORY") (class "Default")
      (node (ref "IC16") (pin "95") (pinfunction "TRD2/SQID2/RG14_95") (pintype "bidirectional"))
      (node (ref "R75") (pin "2") (pinfunction "2_2") (pintype "passive"))
    )
    (net (code "47") (name "MUTE") (class "Default")
      (node (ref "IC16") (pin "57") (pinfunction "EBIRDY3/RPF2/SDA3/RF2_57") (pintype "bidirectional"))
      (node (ref "IC6") (pin "P22") (pinfunction "MUTE_P22") (pintype "bidirectional"))
    )
    (net (code "48") (name "Net-(C3-Pad1)") (class "Default")
      (node (ref "C3") (pin "1") (pinfunction "1_1") (pintype "passive"))
      (node (ref "R4") (pin "2") (pinfunction "2_2") (pintype "passive"))
    )
    (net (code "49") (name "Net-(C6-Pad1)") (class "Default")
      (node (ref "C6") (pin "1") (pinfunction "1_1") (pintype "passive"))
      (node (ref "D1") (pin "C") (pinfunction "C_C") (pintype "passive"))
      (node (ref "L1") (pin "2") (pinfunction "2_2") (pintype "passive"))
      (node (ref "R5") (pin "1") (pinfunction "1_1") (pintype "passive"))
    )
    (net (code "50") (name "Net-(C7-Pad1)") (class "Default")
      (node (ref "C7") (pin "1") (pinfunction "1_1") (pintype "passive"))
      (node (ref "R8") (pin "2") (pinfunction "2_2") (pintype "passive"))
    )
    (net (code "51") (name "Net-(C12-Pad1)") (class "Default")
      (node (ref "C12") (pin "1") (pinfunction "1_1") (pintype "passive"))
      (node (ref "R13") (pin "1") (pinfunction "1_1") (pintype "passive"))
    )
    (net (code "52") (name "Net-(C13-Pad1)") (class "Default")
      (node (ref "C13") (pin "1") (pinfunction "1_1") (pintype "passive"))
      (node (ref "D2") (pin "A") (pinfunction "A_A") (pintype "passive"))
      (node (ref "L4") (pin "1") (pinfunction "1_1") (pintype "passive"))
      (node (ref "R17") (pin "2") (pinfunction "2_2") (pintype "passive"))
    )
    (net (code "53") (name "Net-(C15-Pad1)") (class "Default")
      (node (ref "C15") (pin "1") (pinfunction "1_1") (pintype "passive"))
      (node (ref "R16") (pin "2") (pinfunction "2_2") (pintype "passive"))
    )
    (net (code "54") (name "Net-(C43-Pad1)") (class "Default")
      (node (ref "C43") (pin "1") (pinfunction "1_1") (pintype "passive"))
      (node (ref "R27") (pin "2") (pinfunction "2_2") (pintype "passive"))
    )
    (net (code "55") (name "Net-(C44-Pad1)") (class "Default")
      (node (ref "C44") (pin "1") (pinfunction "1_1") (pintype "passive"))
      (node (ref "R28") (pin "2") (pinfunction "2_2") (pintype "passive"))
    )
    (net (code "56") (name "Net-(C47-Pad1)") (class "Default")
      (node (ref "C47") (pin "1") (pinfunction "1_1") (pintype "passive"))
      (node (ref "R31") (pin "2") (pinfunction "2_2") (pintype "passive"))
      (node (ref "R33") (pin "1") (pinfunction "1_1") (pintype "passive"))
      (node (ref "R35") (pin "1") (pinfunction "1_1") (pintype "passive"))
    )
    (net (code "57") (name "Net-(C48-Pad1)") (class "Default")
      (node (ref "C48") (pin "1") (pinfunction "1_1") (pintype "passive"))
      (node (ref "R32") (pin "2") (pinfunction "2_2") (pintype "passive"))
      (node (ref "R34") (pin "2") (pinfunction "2_2") (pintype "passive"))
      (node (ref "R36") (pin "1") (pinfunction "1_1") (pintype "passive"))
    )
    (net (code "58") (name "Net-(C54-Pad1)") (class "Default")
      (node (ref "C54") (pin "1") (pinfunction "1_1") (pintype "passive"))
      (node (ref "R37") (pin "2") (pinfunction "2_2") (pintype "passive"))
    )
    (net (code "59") (name "Net-(C67-Pad1)") (class "Default")
      (node (ref "C67") (pin "1") (pinfunction "1_1") (pintype "passive"))
      (node (ref "R43") (pin "2") (pinfunction "2_2") (pintype "passive"))
    )
    (net (code "60") (name "Net-(C68-Pad1)") (class "Default")
      (node (ref "C68") (pin "1") (pinfunction "1_1") (pintype "passive"))
      (node (ref "R44") (pin "2") (pinfunction "2_2") (pintype "passive"))
    )
    (net (code "61") (name "Net-(C71-Pad1)") (class "Default")
      (node (ref "C71") (pin "1") (pinfunction "1_1") (pintype "passive"))
      (node (ref "R47") (pin "2") (pinfunction "2_2") (pintype "passive"))
      (node (ref "R49") (pin "1") (pinfunction "1_1") (pintype "passive"))
      (node (ref "R51") (pin "1") (pinfunction "1_1") (pintype "passive"))
    )
    (net (code "62") (name "Net-(C72-Pad1)") (class "Default")
      (node (ref "C72") (pin "1") (pinfunction "1_1") (pintype "passive"))
      (node (ref "R48") (pin "2") (pinfunction "2_2") (pintype "passive"))
      (node (ref "R50") (pin "2") (pinfunction "2_2") (pintype "passive"))
      (node (ref "R52") (pin "1") (pinfunction "1_1") (pintype "passive"))
    )
    (net (code "63") (name "Net-(C78-Pad1)") (class "Default")
      (node (ref "C78") (pin "1") (pinfunction "1_1") (pintype "passive"))
      (node (ref "R53") (pin "2") (pinfunction "2_2") (pintype "passive"))
    )
    (net (code "64") (name "Net-(C101-Pad1)") (class "Default")
      (node (ref "C101") (pin "1") (pinfunction "1_1") (pintype "passive"))
      (node (ref "R56") (pin "1") (pinfunction "1_1") (pintype "passive"))
      (node (ref "R57") (pin "2") (pinfunction "2_2") (pintype "passive"))
    )
    (net (code "65") (name "Net-(IC1-ADJ)") (class "Default")
      (node (ref "IC1") (pin "4") (pinfunction "ADJ_4") (pintype "bidirectional"))
      (node (ref "R1") (pin "2") (pinfunction "2_2") (pintype "passive"))
      (node (ref "R2") (pin "2") (pinfunction "2_2") (pintype "passive"))
      (node (ref "R3") (pin "1") (pinfunction "1_1") (pintype "passive"))
      (node (ref "R4") (pin "1") (pinfunction "1_1") (pintype "passive"))
    )
    (net (code "66") (name "Net-(IC1-EN)") (class "Default")
      (node (ref "C148") (pin "1") (pinfunction "1_1") (pintype "passive"))
      (node (ref "IC1") (pin "3") (pinfunction "EN_3") (pintype "bidirectional"))
      (node (ref "R79") (pin "1") (pinfunction "1_1") (pintype "passive"))
      (node (ref "R87") (pin "2") (pinfunction "2_2") (pintype "passive"))
    )
    (net (code "67") (name "Net-(IC2-COMP1)") (class "Default")
      (node (ref "C8") (pin "1") (pinfunction "1_1") (pintype "passive"))
      (node (ref "IC2") (pin "8") (pinfunction "COMP1_8") (pintype "bidirectional"))
      (node (ref "R8") (pin "1") (pinfunction "1_1") (pintype "passive"))
    )
    (net (code "68") (name "Net-(IC2-COMP2)") (class "Default")
      (node (ref "C10") (pin "1") (pinfunction "1_1") (pintype "passive"))
      (node (ref "IC2") (pin "12") (pinfunction "COMP2_12") (pintype "bidirectional"))
      (node (ref "R13") (pin "2") (pinfunction "2_2") (pintype "passive"))
    )
    (net (code "69") (name "Net-(IC2-FB1)") (class "Default")
      (node (ref "IC2") (pin "7") (pinfunction "FB1_7") (pintype "bidirectional"))
      (node (ref "R6") (pin "1") (pinfunction "1_1") (pintype "passive"))
      (node (ref "R7") (pin "1") (pinfunction "1_1") (pintype "passive"))
    )
    (net (code "70") (name "Net-(IC2-FB2)") (class "Default")
      (node (ref "IC2") (pin "13") (pinfunction "FB2_13") (pintype "bidirectional"))
      (node (ref "R10") (pin "2") (pinfunction "2_2") (pintype "passive"))
      (node (ref "R12") (pin "2") (pinfunction "2_2") (pintype "passive"))
    )
    (net (code "71") (name "Net-(IC2-INBK)") (class "Default")
      (node (ref "IC2") (pin "3") (pinfunction "INBK_3") (pintype "bidirectional"))
      (node (ref "L2") (pin "2") (pinfunction "2_2") (pintype "passive"))
    )
    (net (code "72") (name "Net-(IC2-SW1)") (class "Default")
      (node (ref "D1") (pin "A") (pinfunction "A_A") (pintype "passive"))
      (node (ref "IC2") (pin "2") (pinfunction "SW1_2") (pintype "bidirectional"))
      (node (ref "L2") (pin "1") (pinfunction "1_1") (pintype "passive"))
    )
    (net (code "73") (name "Net-(IC2-SW2)") (class "Default")
      (node (ref "D2") (pin "C") (pinfunction "C_C") (pintype "passive"))
      (node (ref "IC2") (pin "20") (pinfunction "SW2_20") (pintype "bidirectional"))
      (node (ref "L3") (pin "1") (pinfunction "1_1") (pintype "passive"))
    )
    (net (code "74") (name "Net-(IC2-VREF)") (class "Default")
      (node (ref "C137") (pin "1") (pinfunction "1_1") (pintype "passive"))
      (node (ref "IC2") (pin "14") (pinfunction "VREF_14") (pintype "bidirectional"))
      (node (ref "R10") (pin "1") (pinfunction "1_1") (pintype "passive"))
    )
    (net (code "75") (name "Net-(IC2-VREG)") (class "Default")
      (node (ref "C14") (pin "1") (pinfunction "1_1") (pintype "passive"))
      (node (ref "IC2") (pin "16") (pinfunction "VREG_16") (pintype "bidirectional"))
    )
    (net (code "76") (name "Net-(IC3-ADJ)") (class "Default")
      (node (ref "IC3") (pin "4") (pinfunction "ADJ_4") (pintype "bidirectional"))
      (node (ref "R11") (pin "2") (pinfunction "2_2") (pintype "passive"))
      (node (ref "R14") (pin "2") (pinfunction "2_2") (pintype "passive"))
      (node (ref "R15") (pin "1") (pinfunction "1_1") (pintype "passive"))
      (node (ref "R16") (pin "1") (pinfunction "1_1") (pintype "passive"))
    )
    (net (code "77") (name "Net-(IC3-EN)") (class "Default")
      (node (ref "C149") (pin "1") (pinfunction "1_1") (pintype "passive"))
      (node (ref "IC3") (pin "3") (pinfunction "EN_3") (pintype "bidirectional"))
      (node (ref "R78") (pin "1") (pinfunction "1_1") (pintype "passive"))
      (node (ref "R88") (pin "2") (pinfunction "2_2") (pintype "passive"))
    )
    (net (code "78") (name "Net-(IC4-EN)") (class "Default")
      (node (ref "C24") (pin "2") (pinfunction "2_2") (pintype "passive"))
      (node (ref "C26") (pin "2") (pinfunction "2_2") (pintype "passive"))
      (node (ref "IC4") (pin "1") (pinfunction "IN_1") (pintype "bidirectional"))
      (node (ref "IC4") (pin "3") (pinfunction "EN_3") (pintype "bidirectional"))
      (node (ref "L5") (pin "2") (pinfunction "2_2") (pintype "passive"))
    )
    (net (code "79") (name "Net-(IC4-N{slash}C)") (class "Default")
      (node (ref "C22") (pin "2") (pinfunction "2_2") (pintype "passive"))
      (node (ref "IC4") (pin "4") (pinfunction "N/C_4") (pintype "bidirectional"))
    )
    (net (code "80") (name "Net-(IC5-EN)") (class "Default")
      (node (ref "C25") (pin "2") (pinfunction "2_2") (pintype "passive"))
      (node (ref "C27") (pin "2") (pinfunction "2_2") (pintype "passive"))
      (node (ref "IC5") (pin "1") (pinfunction "IN_1") (pintype "bidirectional"))
      (node (ref "IC5") (pin "3") (pinfunction "EN_3") (pintype "bidirectional"))
      (node (ref "L6") (pin "2") (pinfunction "2_2") (pintype "passive"))
    )
    (net (code "81") (name "Net-(IC5-N{slash}C)") (class "Default")
      (node (ref "C23") (pin "2") (pinfunction "2_2") (pintype "passive"))
      (node (ref "IC5") (pin "4") (pinfunction "N/C_4") (pintype "bidirectional"))
    )
    (net (code "82") (name "Net-(IC6-AVDD)") (class "Default")
      (node (ref "C31") (pin "1") (pinfunction "1_1") (pintype "passive"))
      (node (ref "IC6") (pin "P15") (pinfunction "AVDD_P15") (pintype "bidirectional"))
      (node (ref "L8") (pin "2") (pinfunction "2_2") (pintype "passive"))
    )
    (net (code "83") (name "Net-(IC6-DVDD)") (class "Default")
      (node (ref "C30") (pin "1") (pinfunction "1_1") (pintype "passive"))
      (node (ref "IC6") (pin "P1") (pinfunction "DVDD_P1") (pintype "bidirectional"))
      (node (ref "L7") (pin "2") (pinfunction "2_2") (pintype "passive"))
    )
    (net (code "84") (name "Net-(IC6-FILTR)") (class "Default")
      (node (ref "C29") (pin "1") (pinfunction "1_1") (pintype "passive"))
      (node (ref "C33") (pin "+") (pinfunction "+_+") (pintype "passive"))
      (node (ref "IC6") (pin "P13") (pinfunction "FILTR_P13") (pintype "bidirectional"))
    )
    (net (code "85") (name "Net-(IC6-IREF)") (class "Default")
      (node (ref "IC6") (pin "P14") (pinfunction "IREF_P14") (pintype "bidirectional"))
      (node (ref "R18") (pin "2") (pinfunction "2_2") (pintype "passive"))
    )
    (net (code "86") (name "Net-(IC7-+IN)") (class "Default")
      (node (ref "C39") (pin "1") (pinfunction "1_1") (pintype "passive"))
      (node (ref "IC7") (pin "3") (pinfunction "+IN_3") (pintype "input"))
      (node (ref "R24") (pin "1") (pinfunction "1_1") (pintype "passive"))
    )
    (net (code "87") (name "Net-(IC7-OUT)") (class "Default")
      (node (ref "C43") (pin "2") (pinfunction "2_2") (pintype "passive"))
      (node (ref "IC7") (pin "6") (pinfunction "OUT_6") (pintype "output"))
      (node (ref "R29") (pin "2") (pinfunction "2_2") (pintype "passive"))
      (node (ref "R31") (pin "1") (pinfunction "1_1") (pintype "passive"))
    )
    (net (code "88") (name "Net-(IC8-+IN)") (class "Default")
      (node (ref "C40") (pin "1") (pinfunction "1_1") (pintype "passive"))
      (node (ref "IC8") (pin "3") (pinfunction "+IN_3") (pintype "input"))
      (node (ref "R25") (pin "1") (pinfunction "1_1") (pintype "passive"))
    )
    (net (code "89") (name "Net-(IC8-OUT)") (class "Default")
      (node (ref "C44") (pin "2") (pinfunction "2_2") (pintype "passive"))
      (node (ref "IC8") (pin "6") (pinfunction "OUT_6") (pintype "output"))
      (node (ref "R30") (pin "2") (pinfunction "2_2") (pintype "passive"))
      (node (ref "R32") (pin "1") (pinfunction "1_1") (pintype "passive"))
    )
    (net (code "90") (name "Net-(IC9-+IN)") (class "Default")
      (node (ref "C51") (pin "1") (pinfunction "1_1") (pintype "passive"))
      (node (ref "IC9") (pin "3") (pinfunction "+IN_3") (pintype "input"))
      (node (ref "R36") (pin "2") (pinfunction "2_2") (pintype "passive"))
    )
    (net (code "91") (name "Net-(IC9--IN)") (class "Default")
      (node (ref "IC9") (pin "2") (pinfunction "-IN_2") (pintype "input"))
      (node (ref "R35") (pin "2") (pinfunction "2_2") (pintype "passive"))
      (node (ref "R37") (pin "1") (pinfunction "1_1") (pintype "passive"))
    )
    (net (code "92") (name "Net-(IC9-OUT)") (class "Default")
      (node (ref "C54") (pin "2") (pinfunction "2_2") (pintype "passive"))
      (node (ref "IC9") (pin "6") (pinfunction "OUT_6") (pintype "output"))
      (node (ref "R33") (pin "2") (pinfunction "2_2") (pintype "passive"))
      (node (ref "R38") (pin "1") (pinfunction "1_1") (pintype "passive"))
    )
    (net (code "93") (name "Net-(IC10-+IN)") (class "Default")
      (node (ref "C63") (pin "1") (pinfunction "1_1") (pintype "passive"))
      (node (ref "IC10") (pin "3") (pinfunction "+IN_3") (pintype "input"))
      (node (ref "R40") (pin "1") (pinfunction "1_1") (pintype "passive"))
    )
    (net (code "94") (name "Net-(IC10-OUT)") (class "Default")
      (node (ref "C67") (pin "2") (pinfunction "2_2") (pintype "passive"))
      (node (ref "IC10") (pin "6") (pinfunction "OUT_6") (pintype "output"))
      (node (ref "R45") (pin "2") (pinfunction "2_2") (pintype "passive"))
      (node (ref "R47") (pin "1") (pinfunction "1_1") (pintype "passive"))
    )
    (net (code "95") (name "Net-(IC11-+IN)") (class "Default")
      (node (ref "C64") (pin "1") (pinfunction "1_1") (pintype "passive"))
      (node (ref "IC11") (pin "3") (pinfunction "+IN_3") (pintype "input"))
      (node (ref "R41") (pin "1") (pinfunction "1_1") (pintype "passive"))
    )
    (net (code "96") (name "Net-(IC11-OUT)") (class "Default")
      (node (ref "C68") (pin "2") (pinfunction "2_2") (pintype "passive"))
      (node (ref "IC11") (pin "6") (pinfunction "OUT_6") (pintype "output"))
      (node (ref "R46") (pin "2") (pinfunction "2_2") (pintype "passive"))
      (node (ref "R48") (pin "1") (pinfunction "1_1") (pintype "passive"))
    )
    (net (code "97") (name "Net-(IC12-+IN)") (class "Default")
      (node (ref "C75") (pin "1") (pinfunction "1_1") (pintype "passive"))
      (node (ref "IC12") (pin "3") (pinfunction "+IN_3") (pintype "input"))
      (node (ref "R52") (pin "2") (pinfunction "2_2") (pintype "passive"))
    )
    (net (code "98") (name "Net-(IC12--IN)") (class "Default")
      (node (ref "IC12") (pin "2") (pinfunction "-IN_2") (pintype "input"))
      (node (ref "R51") (pin "2") (pinfunction "2_2") (pintype "passive"))
      (node (ref "R53") (pin "1") (pinfunction "1_1") (pintype "passive"))
    )
    (net (code "99") (name "Net-(IC12-OUT)") (class "Default")
      (node (ref "C78") (pin "2") (pinfunction "2_2") (pintype "passive"))
      (node (ref "IC12") (pin "6") (pinfunction "OUT_6") (pintype "output"))
      (node (ref "R49") (pin "2") (pinfunction "2_2") (pintype "passive"))
      (node (ref "R54") (pin "1") (pinfunction "1_1") (pintype "passive"))
    )
    (net (code "100") (name "Net-(IC14-EN)") (class "Default")
      (node (ref "C90") (pin "2") (pinfunction "2_2") (pintype "passive"))
      (node (ref "C91") (pin "2") (pinfunction "2_2") (pintype "passive"))
      (node (ref "IC14") (pin "P$1") (pinfunction "IN_P$1") (pintype "bidirectional"))
      (node (ref "IC14") (pin "P$5") (pinfunction "EN_P$5") (pintype "bidirectional"))
      (node (ref "L9") (pin "2") (pinfunction "2_2") (pintype "passive"))
    )
    (net (code "101") (name "Net-(IC14-NR{slash}FB)") (class "Default")
      (node (ref "IC14") (pin "P$4") (pinfunction "NR/FB_P$4") (pintype "bidirectional"))
      (node (ref "R55") (pin "2") (pinfunction "2_2") (pintype "passive"))
      (node (ref "R74") (pin "1") (pinfunction "1_1") (pintype "passive"))
    )
    (net (code "102") (name "Net-(IC15-VBUS)") (class "Default")
      (node (ref "C138") (pin "1") (pinfunction "1_1") (pintype "passive"))
      (node (ref "IC15") (pin "P$5") (pinfunction "VBUS_P$5") (pintype "bidirectional"))
      (node (ref "L13") (pin "2") (pinfunction "2_2") (pintype "passive"))
      (node (ref "USB1") (pin "P$1") (pinfunction "1_P$1") (pintype "bidirectional"))
    )
    (net (code "103") (name "Net-(IC16-OSC1{slash}CLKI{slash}RC12)") (class "Default")
      (node (ref "IC16") (pin "49") (pinfunction "OSC1/CLKI/RC12_49") (pintype "bidirectional"))
      (node (ref "OSC1") (pin "P$3") (pinfunction "OUTPUT_P$3") (pintype "passive"))
    )
    (net (code "104") (name "Net-(IC16-SOSCO{slash}RPC14{slash}T1CK{slash}RC14)") (class "Default")
      (node (ref "IC16") (pin "73") (pinfunction "SOSCO/RPC14/T1CK/RC14_73") (pintype "bidirectional"))
      (node (ref "OSC3") (pin "P$3") (pinfunction "OUTPUT_P$3") (pintype "passive"))
    )
    (net (code "105") (name "Net-(IC17-VBUS)") (class "Default")
      (node (ref "C106") (pin "1") (pinfunction "1_1") (pintype "passive"))
      (node (ref "IC17") (pin "P$5") (pinfunction "VBUS_P$5") (pintype "bidirectional"))
      (node (ref "L10") (pin "2") (pinfunction "2_2") (pintype "passive"))
      (node (ref "USB2") (pin "P$1") (pinfunction "1_P$1") (pintype "bidirectional"))
    )
    (net (code "106") (name "Net-(IC19-3V3OUT)") (class "Default")
      (node (ref "C113") (pin "1") (pinfunction "1_1") (pintype "passive"))
      (node (ref "IC19") (pin "17") (pinfunction "3V3OUT_17") (pintype "output"))
    )
    (net (code "107") (name "Net-(IC25-AVCC)") (class "Default")
      (node (ref "C131") (pin "1") (pinfunction "1_1") (pintype "passive"))
      (node (ref "IC25") (pin "39") (pinfunction "AVCC_39") (pintype "power_in"))
      (node (ref "L12") (pin "2") (pinfunction "2_2") (pintype "passive"))
    )
    (net (code "108") (name "Net-(IC25-PB1{slash}ADC9)") (class "Default")
      (node (ref "C140") (pin "1") (pinfunction "1_1") (pintype "passive"))
      (node (ref "IC25") (pin "5") (pinfunction "PB1/ADC9_5") (pintype "bidirectional"))
      (node (ref "R19") (pin "2") (pinfunction "2_2") (pintype "passive"))
    )
    (net (code "109") (name "Net-(IC25-PB2{slash}ADC10{slash}DAC0)") (class "Default")
      (node (ref "C122") (pin "1") (pinfunction "1_1") (pintype "passive"))
      (node (ref "IC25") (pin "6") (pinfunction "PB2/ADC10/DAC0_6") (pintype "bidirectional"))
      (node (ref "R62") (pin "2") (pinfunction "2_2") (pintype "passive"))
    )
    (net (code "110") (name "Net-(IC25-PR1{slash}XTAL1)") (class "Default")
      (node (ref "IC25") (pin "37") (pinfunction "PR1/XTAL1_37") (pintype "bidirectional"))
      (node (ref "OSC2") (pin "P$3") (pinfunction "OUTPUT_P$3") (pintype "passive"))
    )
    (net (code "111") (name "Net-(IC26-+IN)") (class "Default")
      (node (ref "IC26") (pin "3") (pinfunction "+IN_3") (pintype "input"))
      (node (ref "R83") (pin "1") (pinfunction "1_1") (pintype "passive"))
      (node (ref "R84") (pin "2") (pinfunction "2_2") (pintype "passive"))
    )
    (net (code "112") (name "Net-(IC26--IN)") (class "Default")
      (node (ref "IC26") (pin "1") (pinfunction "OUT_1") (pintype "output"))
      (node (ref "IC26") (pin "4") (pinfunction "-IN_4") (pintype "input"))
      (node (ref "R81") (pin "1") (pinfunction "1_1") (pintype "passive"))
    )
    (net (code "113") (name "Net-(IC27-+IN)") (class "Default")
      (node (ref "IC27") (pin "3") (pinfunction "+IN_3") (pintype "input"))
      (node (ref "R85") (pin "1") (pinfunction "1_1") (pintype "passive"))
      (node (ref "R86") (pin "2") (pinfunction "2_2") (pintype "passive"))
    )
    (net (code "114") (name "Net-(IC27--IN)") (class "Default")
      (node (ref "IC27") (pin "1") (pinfunction "OUT_1") (pintype "output"))
      (node (ref "IC27") (pin "4") (pinfunction "-IN_4") (pintype "input"))
      (node (ref "R82") (pin "1") (pinfunction "1_1") (pintype "passive"))
    )
    (net (code "115") (name "Net-(LED1-PadA)") (class "Default")
      (node (ref "LED1") (pin "A") (pinfunction "A_A") (pintype "bidirectional"))
      (node (ref "R75") (pin "1") (pinfunction "1_1") (pintype "passive"))
    )
    (net (code "116") (name "Net-(LED2-PadA)") (class "Default")
      (node (ref "LED2") (pin "A") (pinfunction "A_A") (pintype "bidirectional"))
      (node (ref "R76") (pin "1") (pinfunction "1_1") (pintype "passive"))
    )
    (net (code "117") (name "Net-(LED3-PadA)") (class "Default")
      (node (ref "LED3") (pin "A") (pinfunction "A_A") (pintype "bidirectional"))
      (node (ref "R77") (pin "1") (pinfunction "1_1") (pintype "passive"))
    )
    (net (code "118") (name "Net-(R66-Pad1)") (class "Default")
      (node (ref "R66") (pin "1") (pinfunction "1_1") (pintype "passive"))
      (node (ref "STATE") (pin "A") (pinfunction "A_A") (pintype "bidirectional"))
    )
    (net (code "119") (name "Net-(USB1-2)") (class "Default")
      (node (ref "IC15") (pin "P$1") (pinfunction "IO1_P$1") (pintype "bidirectional"))
      (node (ref "USB1") (pin "P$2") (pinfunction "2_P$2") (pintype "bidirectional"))
    )
    (net (code "120") (name "Net-(USB1-3)") (class "Default")
      (node (ref "IC15") (pin "P$3") (pinfunction "IO2_P$3") (pintype "bidirectional"))
      (node (ref "USB1") (pin "P$3") (pinfunction "3_P$3") (pintype "bidirectional"))
    )
    (net (code "121") (name "Net-(USB1-P$1)") (class "Default")
      (node (ref "RUSB1") (pin "1") (pinfunction "1_1") (pintype "passive"))
      (node (ref "USB1") (pin "SHIELD_3") (pinfunction "P$1_SHIELD_3") (pintype "bidirectional"))
    )
    (net (code "122") (name "Net-(USB1-P$4)") (class "Default")
      (node (ref "CUSB1") (pin "1") (pinfunction "1_1") (pintype "passive"))
      (node (ref "USB1") (pin "SHIELD_4") (pinfunction "P$4_SHIELD_4") (pintype "bidirectional"))
    )
    (net (code "123") (name "Net-(USB2-2)") (class "Default")
      (node (ref "IC17") (pin "P$1") (pinfunction "IO1_P$1") (pintype "bidirectional"))
      (node (ref "USB2") (pin "P$2") (pinfunction "2_P$2") (pintype "bidirectional"))
    )
    (net (code "124") (name "Net-(USB2-3)") (class "Default")
      (node (ref "IC17") (pin "P$3") (pinfunction "IO2_P$3") (pintype "bidirectional"))
      (node (ref "USB2") (pin "P$3") (pinfunction "3_P$3") (pintype "bidirectional"))
    )
    (net (code "125") (name "Net-(USB2-P$1)") (class "Default")
      (node (ref "RUSB2") (pin "1") (pinfunction "1_1") (pintype "passive"))
      (node (ref "USB2") (pin "SHIELD_1") (pinfunction "P$1_SHIELD_1") (pintype "bidirectional"))
    )
    (net (code "126") (name "Net-(USB2-P$4)") (class "Default")
      (node (ref "CUSB2") (pin "1") (pinfunction "1_1") (pintype "passive"))
      (node (ref "USB2") (pin "SHIELD_4") (pinfunction "P$4_SHIELD_4") (pintype "bidirectional"))
    )
    (net (code "127") (name "OUT0") (class "Default")
      (node (ref "IC23") (pin "4") (pinfunction "P$4_4") (pintype "bidirectional"))
      (node (ref "X1") (pin "P7") (pinfunction "7_P7") (pintype "passive"))
    )
    (net (code "128") (name "OUT00") (class "Default")
      (node (ref "IC16") (pin "22") (pinfunction "AN3/C2INA/RPB3/RB3_22") (pintype "bidirectional"))
      (node (ref "IC23") (pin "2") (pinfunction "P$2_2") (pintype "bidirectional"))
      (node (ref "IC25") (pin "21") (pinfunction "~OC0BXCK0PD1_21") (pintype "bidirectional"))
    )
    (net (code "129") (name "OUT1") (class "Default")
      (node (ref "IC28") (pin "4") (pinfunction "P$4_4") (pintype "bidirectional"))
      (node (ref "X1") (pin "P6") (pinfunction "6_P6") (pintype "passive"))
    )
    (net (code "130") (name "OUT01") (class "Default")
      (node (ref "IC25") (pin "13") (pinfunction "PC3/OC0D/TXD0_13") (pintype "bidirectional"))
      (node (ref "IC28") (pin "2") (pinfunction "P$2_2") (pintype "bidirectional"))
    )
    (net (code "131") (name "OUT2") (class "Default")
      (node (ref "IC29") (pin "4") (pinfunction "P$4_4") (pintype "bidirectional"))
      (node (ref "X1") (pin "P5") (pinfunction "5_P5") (pintype "passive"))
    )
    (net (code "132") (name "OUT02") (class "Default")
      (node (ref "IC25") (pin "14") (pinfunction "PC4/OC1A/#SS_14") (pintype "bidirectional"))
      (node (ref "IC29") (pin "2") (pinfunction "P$2_2") (pintype "bidirectional"))
    )
    (net (code "133") (name "OUTL") (class "Default")
      (node (ref "C57") (pin "1") (pinfunction "1_1") (pintype "passive"))
      (node (ref "J3") (pin "P2") (pinfunction "2_P2") (pintype "passive"))
      (node (ref "R38") (pin "2") (pinfunction "2_2") (pintype "passive"))
    )
    (net (code "134") (name "OUTR") (class "Default")
      (node (ref "C81") (pin "1") (pinfunction "1_1") (pintype "passive"))
      (node (ref "J4") (pin "P2") (pinfunction "2_P2") (pintype "passive"))
      (node (ref "R54") (pin "2") (pinfunction "2_2") (pintype "passive"))
    )
    (net (code "135") (name "PAR0") (class "Default")
      (node (ref "IC16") (pin "17") (pinfunction "TMS/EBIA16/AN24/RA0_17") (pintype "bidirectional"))
      (node (ref "IC25") (pin "40") (pinfunction "PA0/ADC0/AREF_40") (pintype "bidirectional"))
    )
    (net (code "136") (name "PAR1") (class "Default")
      (node (ref "IC16") (pin "38") (pinfunction "TCK/EBIA19/AN29/RA1_38") (pintype "bidirectional"))
      (node (ref "IC25") (pin "41") (pinfunction "PA1/ADC1_41") (pintype "bidirectional"))
    )
    (net (code "137") (name "PAR2") (class "Default")
      (node (ref "IC16") (pin "59") (pinfunction "~{EBICS0}/SCL2/RA2_59") (pintype "bidirectional"))
      (node (ref "IC25") (pin "42") (pinfunction "PA2/ADC2_42") (pintype "bidirectional"))
    )
    (net (code "138") (name "PAR3") (class "Default")
      (node (ref "IC16") (pin "60") (pinfunction "EBIRDY1/SDA2/RA3_60") (pintype "bidirectional"))
      (node (ref "IC25") (pin "43") (pinfunction "PA3/ADC3_43") (pintype "bidirectional"))
    )
    (net (code "139") (name "PAR4") (class "Default")
      (node (ref "IC16") (pin "61") (pinfunction "EBIA14/PMCS1/PMA14/RA4_61") (pintype "bidirectional"))
      (node (ref "IC25") (pin "44") (pinfunction "PA4/ADC4_44") (pintype "bidirectional"))
    )
    (net (code "140") (name "PAR5") (class "Default")
      (node (ref "IC16") (pin "2") (pinfunction "EBIA5/AN34/PMA5/RA5_2") (pintype "bidirectional"))
      (node (ref "IC25") (pin "1") (pinfunction "PA5/ADC5_1") (pintype "bidirectional"))
    )
    (net (code "141") (name "PAR6") (class "Default")
      (node (ref "IC16") (pin "89") (pinfunction "TRCLK/SQICLK/RA6_89") (pintype "bidirectional"))
      (node (ref "IC25") (pin "2") (pinfunction "PA6/ADC6_2") (pintype "bidirectional"))
    )
    (net (code "142") (name "PAR7") (class "Default")
      (node (ref "IC16") (pin "90") (pinfunction "TRD3/SQID3/RA7_90") (pintype "bidirectional"))
      (node (ref "IC25") (pin "3") (pinfunction "PA7/ADC7/AC0-OUT_3") (pintype "bidirectional"))
    )
    (net (code "143") (name "PDI-CLK") (class "Default")
      (node (ref "IC25") (pin "35") (pinfunction "RESET/PDI-CLK_35") (pintype "input"))
      (node (ref "PDI") (pin "5") (pinfunction "5_5") (pintype "passive"))
    )
    (net (code "144") (name "PDI-DATA") (class "Default")
      (node (ref "IC25") (pin "34") (pinfunction "PDI-DATA_34") (pintype "bidirectional"))
      (node (ref "PDI") (pin "1") (pinfunction "1_1") (pintype "passive"))
    )
    (net (code "145") (name "PGEC2") (class "Default")
      (node (ref "IC16") (pin "26") (pinfunction "PGEC2/AN46/RPB6/RB6_26") (pintype "bidirectional"))
      (node (ref "JP1") (pin "5") (pinfunction "5_5") (pintype "passive"))
    )
    (net (code "146") (name "PGED2") (class "Default")
      (node (ref "IC16") (pin "27") (pinfunction "PGED2/AN47/RPB7/RB7_27") (pintype "bidirectional"))
      (node (ref "JP1") (pin "4") (pinfunction "4_4") (pintype "passive"))
    )
    (net (code "147") (name "PMD0") (class "Default")
      (node (ref "IC13") (pin "P29") (pinfunction "I/O0_P29") (pintype "bidirectional"))
      (node (ref "IC16") (pin "91") (pinfunction "EBID0/PMD0/RE0_91") (pintype "bidirectional"))
    )
    (net (code "148") (name "PMD1") (class "Default")
      (node (ref "IC13") (pin "P30") (pinfunction "I/O1_P30") (pintype "bidirectional"))
      (node (ref "IC16") (pin "94") (pinfunction "EBID1/PMD1/RE1_94") (pintype "bidirectional"))
    )
    (net (code "149") (name "PMD2") (class "Default")
      (node (ref "IC13") (pin "P31") (pinfunction "I/O2_P31") (pintype "bidirectional"))
      (node (ref "IC16") (pin "98") (pinfunction "EBID2/PMD2/RE2_98") (pintype "bidirectional"))
    )
    (net (code "150") (name "PMD3") (class "Default")
      (node (ref "IC13") (pin "P32") (pinfunction "I/O3_P32") (pintype "bidirectional"))
      (node (ref "IC16") (pin "99") (pinfunction "EBID3/RPE3/PMD3/RE3_99") (pintype "bidirectional"))
    )
    (net (code "151") (name "PMD4") (class "Default")
      (node (ref "IC13") (pin "P41") (pinfunction "I/O4_P41") (pintype "bidirectional"))
      (node (ref "IC16") (pin "100") (pinfunction "EBID4/AN18/PMD4/RE4_100") (pintype "bidirectional"))
    )
    (net (code "152") (name "PMD5") (class "Default")
      (node (ref "IC13") (pin "P42") (pinfunction "I/O5_P42") (pintype "bidirectional"))
      (node (ref "IC16") (pin "3") (pinfunction "EBID5/AN17/RPE5/PMD5/RE5_3") (pintype "bidirectional"))
    )
    (net (code "153") (name "PMD6") (class "Default")
      (node (ref "IC13") (pin "P43") (pinfunction "I/O6_P43") (pintype "bidirectional"))
      (node (ref "IC16") (pin "4") (pinfunction "EBID6/AN16/PMD6/RE6_4") (pintype "bidirectional"))
    )
    (net (code "154") (name "PMD7") (class "Default")
      (node (ref "IC13") (pin "P44") (pinfunction "I/O7_P44") (pintype "bidirectional"))
      (node (ref "IC16") (pin "5") (pinfunction "EBID7/AN15/PMD7/RE7_5") (pintype "bidirectional"))
    )
    (net (code "155") (name "PMD8") (class "Default")
      (node (ref "IC13") (pin "P26") (pinfunction "I/O8_P26") (pintype "bidirectional"))
    )
    (net (code "156") (name "PMD9") (class "Default")
      (node (ref "IC13") (pin "P27") (pinfunction "I/O9_P27") (pintype "bidirectional"))
    )
    (net (code "157") (name "PMD10") (class "Default")
      (node (ref "IC13") (pin "P28") (pinfunction "I/O10_P28") (pintype "bidirectional"))
    )
    (net (code "158") (name "PMD11") (class "Default")
      (node (ref "IC13") (pin "P33") (pinfunction "I/O11_P33") (pintype "bidirectional"))
    )
    (net (code "159") (name "PMD12") (class "Default")
      (node (ref "IC13") (pin "P40") (pinfunction "I/O12_P40") (pintype "bidirectional"))
    )
    (net (code "160") (name "PMD13") (class "Default")
      (node (ref "IC13") (pin "P45") (pinfunction "I/O13_P45") (pintype "bidirectional"))
    )
    (net (code "161") (name "PMD14") (class "Default")
      (node (ref "IC13") (pin "P46") (pinfunction "I/O14_P46") (pintype "bidirectional"))
    )
    (net (code "162") (name "PMD15") (class "Default")
      (node (ref "IC13") (pin "P47") (pinfunction "I/O15_P47") (pintype "bidirectional"))
    )
    (net (code "163") (name "RE") (class "Default")
      (node (ref "IC13") (pin "P8") (pinfunction "RE#_P8") (pintype "bidirectional"))
      (node (ref "IC16") (pin "9") (pinfunction "~{EBIOE}/AN19/RPC4/PMRD/RC4_9") (pintype "bidirectional"))
    )
    (net (code "164") (name "REFCLK{slash}MCLK") (class "Default")
      (node (ref "IC16") (pin "72") (pinfunction "SOSCI/RPC13/RC13_72") (pintype "bidirectional"))
      (node (ref "IC6") (pin "P27") (pinfunction "MCLK_P27") (pintype "bidirectional"))
    )
    (net (code "165") (name "RTS") (class "Default")
      (node (ref "IC21") (pin "13") (pinfunction "B2_13") (pintype "bidirectional"))
      (node (ref "IC25") (pin "28") (pinfunction "~{OC0ASDAPE0}_28") (pintype "bidirectional"))
    )
    (net (code "166") (name "RXD") (class "Default")
      (node (ref "IC21") (pin "12") (pinfunction "B3_12") (pintype "bidirectional"))
      (node (ref "IC32") (pin "4") (pinfunction "OUT_4") (pintype "bidirectional"))
      (node (ref "IC35") (pin "4") (pinfunction "OUT_4") (pintype "bidirectional"))
    )
    (net (code "167") (name "RXD_") (class "Default")
      (node (ref "IC25") (pin "33") (pinfunction "~TXD0OC0DPE3_33") (pintype "bidirectional"))
      (node (ref "IC35") (pin "2") (pinfunction "IN_2") (pintype "bidirectional"))
    )
    (net (code "168") (name "SCK1") (class "Default")
      (node (ref "IC16") (pin "34") (pinfunction "EBIA13/CVREFOUT/AN5/RPB10/PMA13/RB10_34") (pintype "bidirectional"))
      (node (ref "IC6") (pin "P26") (pinfunction "CCLK_P26") (pintype "bidirectional"))
    )
    (net (code "169") (name "SCK{slash}BIT_CLK") (class "Default")
      (node (ref "IC16") (pin "69") (pinfunction "RPD10/SCK4/RD10_69") (pintype "bidirectional"))
      (node (ref "IC6") (pin "P3") (pinfunction "BCLK/EF_BCLK_P3") (pintype "bidirectional"))
    )
    (net (code "170") (name "SDO1") (class "Default")
      (node (ref "IC16") (pin "33") (pinfunction "EBIA7/AN49/RPB9/PMA7/RB9_33") (pintype "bidirectional"))
      (node (ref "IC6") (pin "P24") (pinfunction "CDATA_P24") (pintype "bidirectional"))
    )
    (net (code "171") (name "SDO{slash}SD") (class "Default")
      (node (ref "IC16") (pin "70") (pinfunction "EMDC/AEMDC/RPD11/RD11_70") (pintype "bidirectional"))
      (node (ref "IC6") (pin "P4") (pinfunction "SDATA/EF_LDATA_P4") (pintype "bidirectional"))
    )
    (net (code "172") (name "SS{slash}WORD_CLK") (class "Default")
      (node (ref "IC16") (pin "68") (pinfunction "EBIA15/RPD9/PMCS2/PMA15/RD9_68") (pintype "bidirectional"))
      (node (ref "IC6") (pin "P2") (pinfunction "LRCLK/EF-WCLK_P2") (pintype "bidirectional"))
    )
    (net (code "173") (name "STATE") (class "Default")
      (node (ref "IC25") (pin "36") (pinfunction "PR0/XTAL2_36") (pintype "bidirectional"))
      (node (ref "R66") (pin "2") (pinfunction "2_2") (pintype "passive"))
    )
    (net (code "174") (name "TP0") (class "Default")
      (node (ref "IC16") (pin "96") (pinfunction "TRD1/SQID1/RG12_96") (pintype "bidirectional"))
      (node (ref "TP0") (pin "TP") (pinfunction "TP_TP") (pintype "input"))
    )
    (net (code "175") (name "TP1") (class "Default")
      (node (ref "IC16") (pin "97") (pinfunction "TRD0/SQID0/RG13_97") (pintype "bidirectional"))
      (node (ref "TP1") (pin "TP") (pinfunction "TP_TP") (pintype "input"))
    )
    (net (code "176") (name "TXD") (class "Default")
      (node (ref "IC21") (pin "14") (pinfunction "B1_14") (pintype "bidirectional"))
      (node (ref "IC25") (pin "32") (pinfunction "~RXD0OC0CPE2_32") (pintype "bidirectional"))
      (node (ref "IC33") (pin "2") (pinfunction "IN_2") (pintype "bidirectional"))
    )
    (net (code "177") (name "UART1_RX") (class "Default")
      (node (ref "IC25") (pin "23") (pinfunction "~OC0DTXD0PD3_23") (pintype "bidirectional"))
    )
    (net (code "178") (name "UART1_TX") (class "Default")
      (node (ref "IC25") (pin "22") (pinfunction "~OC0CRXD0PD2_22") (pintype "bidirectional"))
    )
    (net (code "179") (name "UART2_RX") (class "Default")
      (node (ref "IC16") (pin "7") (pinfunction "EBIA12/AN21/RPC2/PMA12/RC2_7") (pintype "bidirectional"))
      (node (ref "IC25") (pin "26") (pinfunction "~RXD1MISOPD6_26") (pintype "bidirectional"))
      (node (ref "IC33") (pin "4") (pinfunction "OUT_4") (pintype "bidirectional"))
    )
    (net (code "180") (name "UART2_TX") (class "Default")
      (node (ref "IC16") (pin "25") (pinfunction "PGED1/AN0/RPB0/RB0_25") (pintype "bidirectional"))
      (node (ref "IC25") (pin "27") (pinfunction "~~{TXD1SCKCLKOPD7}_27") (pintype "bidirectional"))
      (node (ref "IC32") (pin "2") (pinfunction "IN_2") (pintype "bidirectional"))
    )
    (net (code "181") (name "UC_IO0") (class "Default")
      (node (ref "IC16") (pin "20") (pinfunction "AN45/C1INA/RPB5/RB5_20") (pintype "bidirectional"))
      (node (ref "IC25") (pin "11") (pinfunction "PC1/OC0B/XCK0/SCL_11") (pintype "bidirectional"))
    )
    (net (code "182") (name "UC_IO1") (class "Default")
      (node (ref "IC16") (pin "21") (pinfunction "AN4/C1INB/RB4_21") (pintype "bidirectional"))
      (node (ref "IC25") (pin "15") (pinfunction "PC5/OC1B/MOSI/XCK1_15") (pintype "bidirectional"))
    )
    (net (code "183") (name "UC_IO2") (class "Default")
      (node (ref "IC16") (pin "10") (pinfunction "AN14/C1IND/ECOL/RPG6/SCK2/RG6_10") (pintype "bidirectional"))
      (node (ref "IC25") (pin "16") (pinfunction "PC6/MISO/RXD1_16") (pintype "bidirectional"))
    )
    (net (code "184") (name "UC_IO3") (class "Default")
      (node (ref "IC16") (pin "24") (pinfunction "PGEC1/AN1/RPB1/RB1_24") (pintype "bidirectional"))
      (node (ref "IC25") (pin "17") (pinfunction "PC7/SCK/TXD1/CLKO/EVO_17") (pintype "bidirectional"))
      (node (ref "IC32") (pin "1") (pinfunction "OE_1") (pintype "bidirectional"))
      (node (ref "IC33") (pin "1") (pinfunction "OE_1") (pintype "bidirectional"))
      (node (ref "IC35") (pin "1") (pinfunction "~{OE}_1") (pintype "bidirectional"))
      (node (ref "R89") (pin "1") (pinfunction "1_1") (pintype "passive"))
    )
    (net (code "185") (name "UC_IO4") (class "Default")
      (node (ref "IC16") (pin "23") (pinfunction "AN2/C2INB/RPB2/RB2_23") (pintype "bidirectional"))
      (node (ref "IC25") (pin "25") (pinfunction "~XCK1MOSIPD5_25") (pintype "bidirectional"))
    )
    (net (code "186") (name "USB") (class "Default")
      (node (ref "IC16") (pin "85") (pinfunction "EBID11/ETXD1/RPF0/PMD11/RF0_85") (pintype "bidirectional"))
      (node (ref "R77") (pin "2") (pinfunction "2_2") (pintype "passive"))
    )
    (net (code "187") (name "USB5V") (class "Default")
      (node (ref "C111") (pin "1") (pinfunction "1_1") (pintype "passive"))
      (node (ref "C112") (pin "+") (pinfunction "+_+") (pintype "passive"))
      (node (ref "C114") (pin "1") (pinfunction "1_1") (pintype "passive"))
      (node (ref "C117") (pin "1") (pinfunction "1_1") (pintype "passive"))
      (node (ref "IC19") (pin "20") (pinfunction "VCC_20") (pintype "power_in"))
      (node (ref "IC19") (pin "4") (pinfunction "VCCIO_4") (pintype "power_in"))
      (node (ref "IC21") (pin "1") (pinfunction "VDD1_1") (pintype "bidirectional"))
      (node (ref "IC21") (pin "7") (pinfunction "NC/EN_7") (pintype "bidirectional"))
      (node (ref "L10") (pin "1") (pinfunction "1_1") (pintype "passive"))
    )
    (net (code "188") (name "USBDM") (class "Default")
      (node (ref "C108") (pin "1") (pinfunction "1_1") (pintype "passive"))
      (node (ref "IC17") (pin "P$6") (pinfunction "IO1_P$6") (pintype "bidirectional"))
      (node (ref "IC19") (pin "16") (pinfunction "USBDM_16") (pintype "bidirectional"))
    )
    (net (code "189") (name "USBDP") (class "Default")
      (node (ref "C107") (pin "1") (pinfunction "1_1") (pintype "passive"))
      (node (ref "IC17") (pin "P$4") (pinfunction "IO2_P$4") (pintype "bidirectional"))
      (node (ref "IC19") (pin "15") (pinfunction "USBDP_15") (pintype "bidirectional"))
    )
    (net (code "190") (name "V+") (class "Default")
      (node (ref "C11") (pin "1") (pinfunction "1_1") (pintype "passive"))
      (node (ref "C2") (pin "+") (pinfunction "+_+") (pintype "passive"))
      (node (ref "IC2") (pin "17") (pinfunction "PVIN1_17") (pintype "bidirectional"))
      (node (ref "IC2") (pin "18") (pinfunction "PVINSYS_18") (pintype "bidirectional"))
      (node (ref "IC2") (pin "19") (pinfunction "PVIN2_19") (pintype "bidirectional"))
      (node (ref "JACK") (pin "P1") (pinfunction "1_P1") (pintype "passive"))
      (node (ref "L5") (pin "1") (pinfunction "1_1") (pintype "passive"))
      (node (ref "L6") (pin "1") (pinfunction "1_1") (pintype "passive"))
      (node (ref "L9") (pin "1") (pinfunction "1_1") (pintype "passive"))
    )
    (net (code "191") (name "VBUS") (class "Default")
      (node (ref "IC16") (pin "51") (pinfunction "VBUS_51") (pintype "bidirectional"))
      (node (ref "L13") (pin "1") (pinfunction "1_1") (pintype "passive"))
    )
    (net (code "192") (name "VCC") (class "Default")
      (node (ref "C100") (pin "1") (pinfunction "1_1") (pintype "passive"))
      (node (ref "C102") (pin "1") (pinfunction "1_1") (pintype "passive"))
      (node (ref "C139") (pin "1") (pinfunction "1_1") (pintype "passive"))
      (node (ref "C84") (pin "1") (pinfunction "1_1") (pintype "passive"))
      (node (ref "C86") (pin "1") (pinfunction "1_1") (pintype "passive"))
      (node (ref "C88") (pin "1") (pinfunction "1_1") (pintype "passive"))
      (node (ref "C89") (pin "1") (pinfunction "1_1") (pintype "passive"))
      (node (ref "C92") (pin "1") (pinfunction "1_1") (pintype "passive"))
      (node (ref "C93") (pin "1") (pinfunction "1_1") (pintype "passive"))
      (node (ref "C94") (pin "1") (pinfunction "1_1") (pintype "passive"))
      (node (ref "C95") (pin "1") (pinfunction "1_1") (pintype "passive"))
      (node (ref "C96") (pin "1") (pinfunction "1_1") (pintype "passive"))
      (node (ref "C97") (pin "1") (pinfunction "1_1") (pintype "passive"))
      (node (ref "C98") (pin "1") (pinfunction "1_1") (pintype "passive"))
      (node (ref "C99") (pin "1") (pinfunction "1_1") (pintype "passive"))
      (node (ref "IC13") (pin "P12") (pinfunction "VCC_P12") (pintype "bidirectional"))
      (node (ref "IC13") (pin "P37") (pinfunction "VCC_P37") (pintype "bidirectional"))
      (node (ref "IC13") (pin "P39") (pinfunction "VCC_P39") (pintype "bidirectional"))
      (node (ref "IC16") (pin "14") (pinfunction "VDD_14") (pintype "bidirectional"))
      (node (ref "IC16") (pin "30") (pinfunction "AVDD_30") (pintype "bidirectional"))
      (node (ref "IC16") (pin "37") (pinfunction "VDD_37") (pintype "bidirectional"))
      (node (ref "IC16") (pin "46") (pinfunction "VDD_46") (pintype "bidirectional"))
      (node (ref "IC16") (pin "52") (pinfunction "VUSB3V3_52") (pintype "bidirectional"))
      (node (ref "IC16") (pin "62") (pinfunction "VDD_62") (pintype "bidirectional"))
      (node (ref "IC16") (pin "74") (pinfunction "VDD_74") (pintype "bidirectional"))
      (node (ref "IC16") (pin "83") (pinfunction "VDD_83") (pintype "bidirectional"))
      (node (ref "IC16") (pin "93") (pinfunction "VDD_93") (pintype "bidirectional"))
      (node (ref "IC18") (pin "5") (pinfunction "OUT_5") (pintype "bidirectional"))
      (node (ref "JP1") (pin "2") (pinfunction "2_2") (pintype "passive"))
      (node (ref "OSC1") (pin "P$4") (pinfunction "VDD_P$4") (pintype "passive"))
      (node (ref "OSC3") (pin "P$1") (pinfunction "STANDBY#_P$1") (pintype "passive"))
      (node (ref "OSC3") (pin "P$4") (pinfunction "VDD_P$4") (pintype "passive"))
      (node (ref "R56") (pin "2") (pinfunction "2_2") (pintype "passive"))
      (node (ref "R80") (pin "2") (pinfunction "2_2") (pintype "passive"))
    )
    (net (code "193") (name "VCCINT") (class "Default")
      (node (ref "C120") (pin "1") (pinfunction "1_1") (pintype "passive"))
      (node (ref "C133") (pin "1") (pinfunction "1_1") (pintype "passive"))
      (node (ref "C134") (pin "1") (pinfunction "1_1") (pintype "passive"))
      (node (ref "IC23") (pin "5") (pinfunction "P$5_5") (pintype "bidirectional"))
      (node (ref "IC28") (pin "5") (pinfunction "P$5_5") (pintype "bidirectional"))
      (node (ref "IC29") (pin "5") (pinfunction "P$5_5") (pintype "bidirectional"))
      (node (ref "JP2") (pin "2") (pinfunction "2_2") (pintype "passive"))
    )
    (net (code "194") (name "VCCIO") (class "Default")
      (node (ref "C104") (pin "1") (pinfunction "1_1") (pintype "passive"))
      (node (ref "C105") (pin "1") (pinfunction "1_1") (pintype "passive"))
      (node (ref "C116") (pin "1") (pinfunction "1_1") (pintype "passive"))
      (node (ref "C118") (pin "1") (pinfunction "1_1") (pintype "passive"))
      (node (ref "C119") (pin "1") (pinfunction "1_1") (pintype "passive"))
      (node (ref "C121") (pin "1") (pinfunction "1_1") (pintype "passive"))
      (node (ref "C123") (pin "1") (pinfunction "1_1") (pintype "passive"))
      (node (ref "C126") (pin "1") (pinfunction "1_1") (pintype "passive"))
      (node (ref "C127") (pin "1") (pinfunction "1_1") (pintype "passive"))
      (node (ref "C128") (pin "1") (pinfunction "1_1") (pintype "passive"))
      (node (ref "C130") (pin "1") (pinfunction "1_1") (pintype "passive"))
      (node (ref "C132") (pin "1") (pinfunction "1_1") (pintype "passive"))
      (node (ref "C135") (pin "1") (pinfunction "1_1") (pintype "passive"))
      (node (ref "C136") (pin "1") (pinfunction "1_1") (pintype "passive"))
      (node (ref "C143") (pin "1") (pinfunction "1_1") (pintype "passive"))
      (node (ref "C146") (pin "1") (pinfunction "1_1") (pintype "passive"))
      (node (ref "C147") (pin "1") (pinfunction "1_1") (pintype "passive"))
      (node (ref "CLKIN") (pin "1") (pinfunction "1_1") (pintype "passive"))
      (node (ref "IC20") (pin "5") (pinfunction "OUT_5") (pintype "bidirectional"))
      (node (ref "IC21") (pin "10") (pinfunction "NC/EN_10") (pintype "bidirectional"))
      (node (ref "IC21") (pin "16") (pinfunction "VDD2_16") (pintype "bidirectional"))
      (node (ref "IC22") (pin "5") (pinfunction "P$5_5") (pintype "bidirectional"))
      (node (ref "IC24") (pin "5") (pinfunction "P$5_5") (pintype "bidirectional"))
      (node (ref "IC25") (pin "19") (pinfunction "VCC_19") (pintype "power_in"))
      (node (ref "IC25") (pin "31") (pinfunction "VCC_31") (pintype "power_in"))
      (node (ref "IC25") (pin "9") (pinfunction "VCC_9") (pintype "power_in"))
      (node (ref "IC26") (pin "5") (pinfunction "V+_5") (pintype "power_in"))
      (node (ref "IC27") (pin "5") (pinfunction "V+_5") (pintype "power_in"))
      (node (ref "IC30") (pin "5") (pinfunction "P$5_5") (pintype "bidirectional"))
      (node (ref "IC31") (pin "5") (pinfunction "P$5_5") (pintype "bidirectional"))
      (node (ref "IC32") (pin "5") (pinfunction "VCC_5") (pintype "bidirectional"))
      (node (ref "IC33") (pin "5") (pinfunction "VCC_5") (pintype "bidirectional"))
      (node (ref "IC35") (pin "5") (pinfunction "VCC_5") (pintype "bidirectional"))
      (node (ref "JP2") (pin "3") (pinfunction "3_3") (pintype "passive"))
      (node (ref "L12") (pin "1") (pinfunction "1_1") (pintype "passive"))
      (node (ref "OSC2") (pin "P$4") (pinfunction "VDD_P$4") (pintype "passive"))
      (node (ref "PDI") (pin "2") (pinfunction "2_2") (pintype "passive"))
      (node (ref "R9") (pin "2") (pinfunction "2_2") (pintype "passive"))
    )
    (net (code "195") (name "VREF") (class "Default")
      (node (ref "C34") (pin "1") (pinfunction "1_1") (pintype "passive"))
      (node (ref "C35") (pin "+") (pinfunction "+_+") (pintype "passive"))
      (node (ref "R21") (pin "1") (pinfunction "1_1") (pintype "passive"))
      (node (ref "R22") (pin "2") (pinfunction "2_2") (pintype "passive"))
      (node (ref "R24") (pin "2") (pinfunction "2_2") (pintype "passive"))
      (node (ref "R25") (pin "2") (pinfunction "2_2") (pintype "passive"))
      (node (ref "R40") (pin "2") (pinfunction "2_2") (pintype "passive"))
      (node (ref "R41") (pin "2") (pinfunction "2_2") (pintype "passive"))
    )
    (net (code "196") (name "WE") (class "Default")
      (node (ref "IC13") (pin "P18") (pinfunction "WE#_P18") (pintype "bidirectional"))
      (node (ref "IC16") (pin "8") (pinfunction "~{EBIWE}/AN20/RPC3/PMWR/RC3_8") (pintype "bidirectional"))
    )
    (net (code "197") (name "WP") (class "Default")
      (node (ref "IC13") (pin "P19") (pinfunction "WP#_P19") (pintype "bidirectional"))
      (node (ref "IC16") (pin "12") (pinfunction "EBIA3/AN12/C2IND/ERXDV/ECRSDV..._12") (pintype "bidirectional"))
    )
    (net (code "198") (name "ZEROL") (class "Default")
      (node (ref "IC16") (pin "56") (pinfunction "RPF3/USBID/RF3_56") (pintype "bidirectional"))
      (node (ref "IC6") (pin "P21") (pinfunction "ZEROL_P21") (pintype "bidirectional"))
    )
    (net (code "199") (name "ZEROR") (class "Default")
      (node (ref "IC16") (pin "58") (pinfunction "EBIRDY2/RPF8/SCL3/RF8_58") (pintype "bidirectional"))
      (node (ref "IC6") (pin "P20") (pinfunction "ZEROR_P20") (pintype "bidirectional"))
    )
    (net (code "200") (name "unconnected-(IC2-SEQ-Pad5)") (class "Default")
      (node (ref "IC2") (pin "5") (pinfunction "SEQ_5") (pintype "bidirectional"))
    )
    (net (code "201") (name "unconnected-(IC2-SS-Pad10)") (class "Default")
      (node (ref "IC2") (pin "10") (pinfunction "SS_10") (pintype "bidirectional"))
    )
    (net (code "202") (name "unconnected-(IC6-DSD_LDATA-PadP7)") (class "Default")
      (node (ref "IC6") (pin "P7") (pinfunction "DSD_LDATA_P7") (pintype "bidirectional"))
    )
    (net (code "203") (name "unconnected-(IC6-DSD_RDATA-PadP8)") (class "Default")
      (node (ref "IC6") (pin "P8") (pinfunction "DSD_RDATA_P8") (pintype "bidirectional"))
    )
    (net (code "204") (name "unconnected-(IC6-DSD_SCLK-PadP6)") (class "Default")
      (node (ref "IC6") (pin "P6") (pinfunction "DSD_SCLK_P6") (pintype "bidirectional"))
    )
    (net (code "205") (name "unconnected-(IC6-EF_RDATA-PadP5)") (class "Default")
      (node (ref "IC6") (pin "P5") (pinfunction "EF_RDATA_P5") (pintype "bidirectional"))
    )
    (net (code "206") (name "unconnected-(IC7-COMP-Pad8)") (class "Default")
      (node (ref "IC7") (pin "8") (pinfunction "COMP_8") (pintype "bidirectional"))
    )
    (net (code "207") (name "unconnected-(IC7-NL+-Pad1)") (class "Default")
      (node (ref "IC7") (pin "1") (pinfunction "NL+_1") (pintype "bidirectional"))
    )
    (net (code "208") (name "unconnected-(IC7-NL--Pad5)") (class "Default")
      (node (ref "IC7") (pin "5") (pinfunction "NL-_5") (pintype "bidirectional"))
    )
    (net (code "209") (name "unconnected-(IC8-COMP-Pad8)") (class "Default")
      (node (ref "IC8") (pin "8") (pinfunction "COMP_8") (pintype "bidirectional"))
    )
    (net (code "210") (name "unconnected-(IC8-NL+-Pad1)") (class "Default")
      (node (ref "IC8") (pin "1") (pinfunction "NL+_1") (pintype "bidirectional"))
    )
    (net (code "211") (name "unconnected-(IC8-NL--Pad5)") (class "Default")
      (node (ref "IC8") (pin "5") (pinfunction "NL-_5") (pintype "bidirectional"))
    )
    (net (code "212") (name "unconnected-(IC9-COMP-Pad8)") (class "Default")
      (node (ref "IC9") (pin "8") (pinfunction "COMP_8") (pintype "bidirectional"))
    )
    (net (code "213") (name "unconnected-(IC9-NL+-Pad1)") (class "Default")
      (node (ref "IC9") (pin "1") (pinfunction "NL+_1") (pintype "bidirectional"))
    )
    (net (code "214") (name "unconnected-(IC9-NL--Pad5)") (class "Default")
      (node (ref "IC9") (pin "5") (pinfunction "NL-_5") (pintype "bidirectional"))
    )
    (net (code "215") (name "unconnected-(IC10-COMP-Pad8)") (class "Default")
      (node (ref "IC10") (pin "8") (pinfunction "COMP_8") (pintype "bidirectional"))
    )
    (net (code "216") (name "unconnected-(IC10-NL+-Pad1)") (class "Default")
      (node (ref "IC10") (pin "1") (pinfunction "NL+_1") (pintype "bidirectional"))
    )
    (net (code "217") (name "unconnected-(IC10-NL--Pad5)") (class "Default")
      (node (ref "IC10") (pin "5") (pinfunction "NL-_5") (pintype "bidirectional"))
    )
    (net (code "218") (name "unconnected-(IC11-COMP-Pad8)") (class "Default")
      (node (ref "IC11") (pin "8") (pinfunction "COMP_8") (pintype "bidirectional"))
    )
    (net (code "219") (name "unconnected-(IC11-NL+-Pad1)") (class "Default")
      (node (ref "IC11") (pin "1") (pinfunction "NL+_1") (pintype "bidirectional"))
    )
    (net (code "220") (name "unconnected-(IC11-NL--Pad5)") (class "Default")
      (node (ref "IC11") (pin "5") (pinfunction "NL-_5") (pintype "bidirectional"))
    )
    (net (code "221") (name "unconnected-(IC12-COMP-Pad8)") (class "Default")
      (node (ref "IC12") (pin "8") (pinfunction "COMP_8") (pintype "bidirectional"))
    )
    (net (code "222") (name "unconnected-(IC12-NL+-Pad1)") (class "Default")
      (node (ref "IC12") (pin "1") (pinfunction "NL+_1") (pintype "bidirectional"))
    )
    (net (code "223") (name "unconnected-(IC12-NL--Pad5)") (class "Default")
      (node (ref "IC12") (pin "5") (pinfunction "NL-_5") (pintype "bidirectional"))
    )
    (net (code "224") (name "unconnected-(IC13-NC-PadP1)") (class "Default")
      (node (ref "IC13") (pin "P1") (pinfunction "NC_P1") (pintype "bidirectional"))
    )
    (net (code "225") (name "unconnected-(IC13-NC-PadP2)") (class "Default")
      (node (ref "IC13") (pin "P2") (pinfunction "NC_P2") (pintype "bidirectional"))
    )
    (net (code "226") (name "unconnected-(IC13-NC-PadP3)") (class "Default")
      (node (ref "IC13") (pin "P3") (pinfunction "NC_P3") (pintype "bidirectional"))
    )
    (net (code "227") (name "unconnected-(IC13-NC-PadP4)") (class "Default")
      (node (ref "IC13") (pin "P4") (pinfunction "NC_P4") (pintype "bidirectional"))
    )
    (net (code "228") (name "unconnected-(IC13-NC-PadP5)") (class "Default")
      (node (ref "IC13") (pin "P5") (pinfunction "NC_P5") (pintype "bidirectional"))
    )
    (net (code "229") (name "unconnected-(IC13-NC-PadP6)") (class "Default")
      (node (ref "IC13") (pin "P6") (pinfunction "NC_P6") (pintype "bidirectional"))
    )
    (net (code "230") (name "unconnected-(IC13-NC-PadP10)") (class "Default")
      (node (ref "IC13") (pin "P10") (pinfunction "NC_P10") (pintype "bidirectional"))
    )
    (net (code "231") (name "unconnected-(IC13-NC-PadP11)") (class "Default")
      (node (ref "IC13") (pin "P11") (pinfunction "NC_P11") (pintype "bidirectional"))
    )
    (net (code "232") (name "unconnected-(IC13-NC-PadP14)") (class "Default")
      (node (ref "IC13") (pin "P14") (pinfunction "NC_P14") (pintype "bidirectional"))
    )
    (net (code "233") (name "unconnected-(IC13-NC-PadP15)") (class "Default")
      (node (ref "IC13") (pin "P15") (pinfunction "NC_P15") (pintype "bidirectional"))
    )
    (net (code "234") (name "unconnected-(IC13-NC-PadP20)") (class "Default")
      (node (ref "IC13") (pin "P20") (pinfunction "NC_P20") (pintype "bidirectional"))
    )
    (net (code "235") (name "unconnected-(IC13-NC-PadP21)") (class "Default")
      (node (ref "IC13") (pin "P21") (pinfunction "NC_P21") (pintype "bidirectional"))
    )
    (net (code "236") (name "unconnected-(IC13-NC-PadP22)") (class "Default")
      (node (ref "IC13") (pin "P22") (pinfunction "NC_P22") (pintype "bidirectional"))
    )
    (net (code "237") (name "unconnected-(IC13-NC-PadP23)") (class "Default")
      (node (ref "IC13") (pin "P23") (pinfunction "NC_P23") (pintype "bidirectional"))
    )
    (net (code "238") (name "unconnected-(IC13-NC-PadP24)") (class "Default")
      (node (ref "IC13") (pin "P24") (pinfunction "NC_P24") (pintype "bidirectional"))
    )
    (net (code "239") (name "unconnected-(IC13-NC-PadP35)") (class "Default")
      (node (ref "IC13") (pin "P35") (pinfunction "NC_P35") (pintype "bidirectional"))
    )
    (net (code "240") (name "unconnected-(IC13-NC-PadP38)") (class "Default")
      (node (ref "IC13") (pin "P38") (pinfunction "NC_P38") (pintype "bidirectional"))
    )
    (net (code "241") (name "unconnected-(IC13-VCC-PadP34)") (class "Default")
      (node (ref "IC13") (pin "P34") (pinfunction "VCC_P34") (pintype "bidirectional"))
    )
    (net (code "242") (name "unconnected-(IC16-AETXCLK{slash}RPA14{slash}SCL1{slash}RA14-Pad66)") (class "Default")
      (node (ref "IC16") (pin "66") (pinfunction "AETXCLK/RPA14/SCL1/RA14_66") (pintype "bidirectional"))
    )
    (net (code "243") (name "unconnected-(IC16-AETXEN{slash}RPA15{slash}SDA1{slash}RA15-Pad67)") (class "Default")
      (node (ref "IC16") (pin "67") (pinfunction "AETXEN/RPA15/SDA1/RA15_67") (pintype "bidirectional"))
    )
    (net (code "244") (name "unconnected-(IC16-AN6{slash}ERXERR{slash}AETXERR{slash}RB11-Pad35)") (class "Default")
      (node (ref "IC16") (pin "35") (pinfunction "AN6/ERXERR/AETXERR/RB11_35") (pintype "input"))
    )
    (net (code "245") (name "unconnected-(IC16-AN23{slash}AERXERR{slash}RG15-Pad1)") (class "Default")
      (node (ref "IC16") (pin "1") (pinfunction "AN23/AERXERR/RG15_1") (pintype "bidirectional"))
    )
    (net (code "246") (name "unconnected-(IC16-AN25{slash}AERXD0{slash}RPE8{slash}RE8-Pad18)") (class "Default")
      (node (ref "IC16") (pin "18") (pinfunction "AN25/AERXD0/RPE8/RE8_18") (pintype "bidirectional"))
    )
    (net (code "247") (name "unconnected-(IC16-AN26{slash}AERXD1{slash}RPE9{slash}RE9-Pad19)") (class "Default")
      (node (ref "IC16") (pin "19") (pinfunction "AN26/AERXD1/RPE9/RE9_19") (pintype "bidirectional"))
    )
    (net (code "248") (name "unconnected-(IC16-AN32{slash}AETXD0{slash}RPD14{slash}RD14-Pad47)") (class "Default")
      (node (ref "IC16") (pin "47") (pinfunction "AN32/AETXD0/RPD14/RD14_47") (pintype "bidirectional"))
    )
    (net (code "249") (name "unconnected-(IC16-AN33{slash}AETXD1{slash}RPD15{slash}SCK6{slash}RD15-Pad48)") (class "Default")
      (node (ref "IC16") (pin "48") (pinfunction "AN33/AETXD1/RPD15/SCK6/RD15_48") (pintype "bidirectional"))
    )
    (net (code "250") (name "unconnected-(IC16-EBIA0{slash}AN10{slash}ERXD3{slash}AETXD2{slash}RPB15{slash}OCFB{slash}PMA0{slash}RB15-Pad44)") (class "Default")
      (node (ref "IC16") (pin "44") (pinfunction "EBIA0/AN10/ERXD3/AETXD2/RPB15/OCFB/PMA0/RB15_44") (pintype "bidirectional"))
    )
    (net (code "251") (name "unconnected-(IC16-EBIA1{slash}AN9{slash}ERXD2{slash}AETXD3{slash}RPB14{slash}SCK3{slash}PMA1{slash}RB14-Pad43)") (class "Default")
      (node (ref "IC16") (pin "43") (pinfunction "EBIA1/AN9/ERXD2/AETXD3/RPB14/SCK3/PMA1/RB14_43") (pintype "bidirectional"))
    )
    (net (code "252") (name "unconnected-(IC16-EBIA6{slash}AN22{slash}RPC1{slash}PMA6{slash}RC1-Pad6)") (class "Default")
      (node (ref "IC16") (pin "6") (pinfunction "EBIA6/AN22/RPC1/PMA6/RC1_6") (pintype "bidirectional"))
    )
    (net (code "253") (name "unconnected-(IC16-EBIA9{slash}RPF4{slash}SDA5{slash}PMA9{slash}RF4-Pad64)") (class "Default")
      (node (ref "IC16") (pin "64") (pinfunction "EBIA9/RPF4/SDA5/PMA9/RF4_64") (pintype "bidirectional"))
    )
    (net (code "254") (name "unconnected-(IC16-EBID8{slash}RPG0{slash}PMD8{slash}RG0-Pad88)") (class "Default")
      (node (ref "IC16") (pin "88") (pinfunction "EBID8/RPG0/PMD8/RG0_88") (pintype "input"))
    )
    (net (code "255") (name "unconnected-(IC16-EBID9{slash}ETXERR{slash}RPG1{slash}PMD9{slash}RG1-Pad87)") (class "Default")
      (node (ref "IC16") (pin "87") (pinfunction "EBID9/ETXERR/RPG1/PMD9/RG1_87") (pintype "bidirectional"))
    )
    (net (code "256") (name "unconnected-(IC16-EBID15{slash}ETXCLK{slash}RPD3...-Pad78)") (class "Default")
      (node (ref "IC16") (pin "78") (pinfunction "EBID15/ETXCLK/RPD3..._78") (pintype "bidirectional"))
    )
    (net (code "257") (name "unconnected-(IC16-OSC2{slash}CLKO{slash}RC15-Pad50)") (class "Default")
      (node (ref "IC16") (pin "50") (pinfunction "OSC2/CLKO/RC15_50") (pintype "bidirectional"))
    )
    (net (code "258") (name "unconnected-(IC16-TDI{slash}EBIA18{slash}AN30{slash}RPF13{slash}SCK5{slash}RF13-Pad39)") (class "Default")
      (node (ref "IC16") (pin "39") (pinfunction "TDI/EBIA18/AN30/RPF13/SCK5/RF13_39") (pintype "bidirectional"))
    )
    (net (code "259") (name "unconnected-(IC16-TDO{slash}EBIA17{slash}AN31{slash}RPF12{slash}RF12-Pad40)") (class "Default")
      (node (ref "IC16") (pin "40") (pinfunction "TDO/EBIA17/AN31/RPF12/RF12_40") (pintype "bidirectional"))
    )
    (net (code "260") (name "unconnected-(IC16-VREF+{slash}CVREF+{slash}AN28{slash}AERXD3{slash}RA10-Pad29)") (class "Default")
      (node (ref "IC16") (pin "29") (pinfunction "VREF+/CVREF+/AN28/AERXD3/RA10_29") (pintype "bidirectional"))
    )
    (net (code "261") (name "unconnected-(IC16-VREF-{slash}CVREF-{slash}AN27{slash}AERXD2{slash}RA9-Pad28)") (class "Default")
      (node (ref "IC16") (pin "28") (pinfunction "VREF-/CVREF-/AN27/AERXD2/RA9_28") (pintype "bidirectional"))
    )
    (net (code "262") (name "unconnected-(IC16-~{SQICS1}{slash}RPD5{slash}RD5-Pad82)") (class "Default")
      (node (ref "IC16") (pin "82") (pinfunction "~{SQICS1}/RPD5/RD5_82") (pintype "bidirectional"))
    )
    (net (code "263") (name "unconnected-(IC18-N{slash}C-Pad4)") (class "Default")
      (node (ref "IC18") (pin "4") (pinfunction "N/C_4") (pintype "bidirectional"))
    )
    (net (code "264") (name "unconnected-(IC19-CBUS0-Pad23)") (class "Default")
      (node (ref "IC19") (pin "23") (pinfunction "CBUS0_23") (pintype "bidirectional"))
    )
    (net (code "265") (name "unconnected-(IC19-CBUS1-Pad22)") (class "Default")
      (node (ref "IC19") (pin "22") (pinfunction "CBUS1_22") (pintype "bidirectional"))
    )
    (net (code "266") (name "unconnected-(IC19-CBUS2-Pad13)") (class "Default")
      (node (ref "IC19") (pin "13") (pinfunction "CBUS2_13") (pintype "bidirectional"))
    )
    (net (code "267") (name "unconnected-(IC19-CBUS3-Pad14)") (class "Default")
      (node (ref "IC19") (pin "14") (pinfunction "CBUS3_14") (pintype "bidirectional"))
    )
    (net (code "268") (name "unconnected-(IC19-CBUS4-Pad12)") (class "Default")
      (node (ref "IC19") (pin "12") (pinfunction "CBUS4_12") (pintype "bidirectional"))
    )
    (net (code "269") (name "unconnected-(IC19-OSCI-Pad27)") (class "Default")
      (node (ref "IC19") (pin "27") (pinfunction "OSCI_27") (pintype "input"))
    )
    (net (code "270") (name "unconnected-(IC19-OSCO-Pad28)") (class "Default")
      (node (ref "IC19") (pin "28") (pinfunction "OSCO_28") (pintype "output"))
    )
    (net (code "271") (name "unconnected-(IC19-~{DCD}-Pad10)") (class "Default")
      (node (ref "IC19") (pin "10") (pinfunction "~{DCD}_10") (pintype "input"))
    )
    (net (code "272") (name "unconnected-(IC19-~{DSR}-Pad9)") (class "Default")
      (node (ref "IC19") (pin "9") (pinfunction "~{DSR}_9") (pintype "input"))
    )
    (net (code "273") (name "unconnected-(IC19-~{DTR}-Pad2)") (class "Default")
      (node (ref "IC19") (pin "2") (pinfunction "~{DTR}_2") (pintype "output"))
    )
    (net (code "274") (name "unconnected-(IC19-~{RESET}-Pad19)") (class "Default")
      (node (ref "IC19") (pin "19") (pinfunction "~{RESET}_19") (pintype "input"))
    )
    (net (code "275") (name "unconnected-(IC19-~{RI}-Pad6)") (class "Default")
      (node (ref "IC19") (pin "6") (pinfunction "~{RI}_6") (pintype "input"))
    )
    (net (code "276") (name "unconnected-(IC20-N{slash}C-Pad4)") (class "Default")
      (node (ref "IC20") (pin "4") (pinfunction "N/C_4") (pintype "bidirectional"))
    )
    (net (code "277") (name "unconnected-(J3-3-PadP3)") (class "Default")
      (node (ref "J3") (pin "P3") (pinfunction "3_P3") (pintype "passive"))
    )
    (net (code "278") (name "unconnected-(J4-3-PadP3)") (class "Default")
      (node (ref "J4") (pin "P3") (pinfunction "3_P3") (pintype "passive"))
    )
    (net (code "279") (name "unconnected-(JP1-Pad6)") (class "Default")
      (node (ref "JP1") (pin "6") (pinfunction "6_6") (pintype "passive"))
    )
    (net (code "280") (name "unconnected-(OSC1-STANDBY#-PadP$1)") (class "Default")
      (node (ref "OSC1") (pin "P$1") (pinfunction "STANDBY#_P$1") (pintype "passive"))
    )
    (net (code "281") (name "unconnected-(OSC2-STANDBY#-PadP$1)") (class "Default")
      (node (ref "OSC2") (pin "P$1") (pinfunction "STANDBY#_P$1") (pintype "passive"))
    )
    (net (code "282") (name "unconnected-(PDI-Pad3)") (class "Default")
      (node (ref "PDI") (pin "3") (pinfunction "3_3") (pintype "passive"))
    )
    (net (code "283") (name "unconnected-(PDI-Pad4)") (class "Default")
      (node (ref "PDI") (pin "4") (pinfunction "4_4") (pintype "passive"))
    )
    (net (code "284") (name "unconnected-(USB1-4-PadP$4)") (class "Default")
      (node (ref "USB1") (pin "P$4") (pinfunction "4_P$4") (pintype "bidirectional"))
    )
    (net (code "285") (name "unconnected-(USB1-P$2-PadSHIELD_1)") (class "Default")
      (node (ref "USB1") (pin "SHIELD_1") (pinfunction "P$2_SHIELD_1") (pintype "bidirectional"))
    )
    (net (code "286") (name "unconnected-(USB1-P$3-PadSHIELD_2)") (class "Default")
      (node (ref "USB1") (pin "SHIELD_2") (pinfunction "P$3_SHIELD_2") (pintype "bidirectional"))
    )
    (net (code "287") (name "unconnected-(USB1-P$5-PadP$6)") (class "Default")
      (node (ref "USB1") (pin "P$6") (pinfunction "P$5_P$6") (pintype "bidirectional"))
    )
    (net (code "288") (name "unconnected-(USB1-P$6-PadP$7)") (class "Default")
      (node (ref "USB1") (pin "P$7") (pinfunction "P$6_P$7") (pintype "bidirectional"))
    )
    (net (code "289") (name "unconnected-(USB2-4-PadP$4)") (class "Default")
      (node (ref "USB2") (pin "P$4") (pinfunction "4_P$4") (pintype "bidirectional"))
    )
    (net (code "290") (name "unconnected-(USB2-P$2-PadSHIELD_2)") (class "Default")
      (node (ref "USB2") (pin "SHIELD_2") (pinfunction "P$2_SHIELD_2") (pintype "bidirectional"))
    )
    (net (code "291") (name "unconnected-(USB2-P$3-PadSHIELD_3)") (class "Default")
      (node (ref "USB2") (pin "SHIELD_3") (pinfunction "P$3_SHIELD_3") (pintype "bidirectional"))
    )
    (net (code "292") (name "~{MCLR}") (class "Default")
      (node (ref "IC16") (pin "15") (pinfunction "~{MCLR}_15") (pintype "bidirectional"))
      (node (ref "JP1") (pin "1") (pinfunction "1_1") (pintype "passive"))
      (node (ref "R57") (pin "1") (pinfunction "1_1") (pintype "passive"))
      (node (ref "SW1") (pin "O") (pinfunction "O_O") (pintype "passive"))
    )
    (net (code "293") (name "~{SS1}") (class "Default")
      (node (ref "IC16") (pin "32") (pinfunction "EBIA10/AN48/RPB8/PMA10/RB8_32") (pintype "bidirectional"))
      (node (ref "IC6") (pin "P25") (pinfunction "~{CLATCH}_P25") (pintype "bidirectional"))
    )
  )
)
